# tc08ss.net
KiCad netlist of a schematic drawn in EAGLE
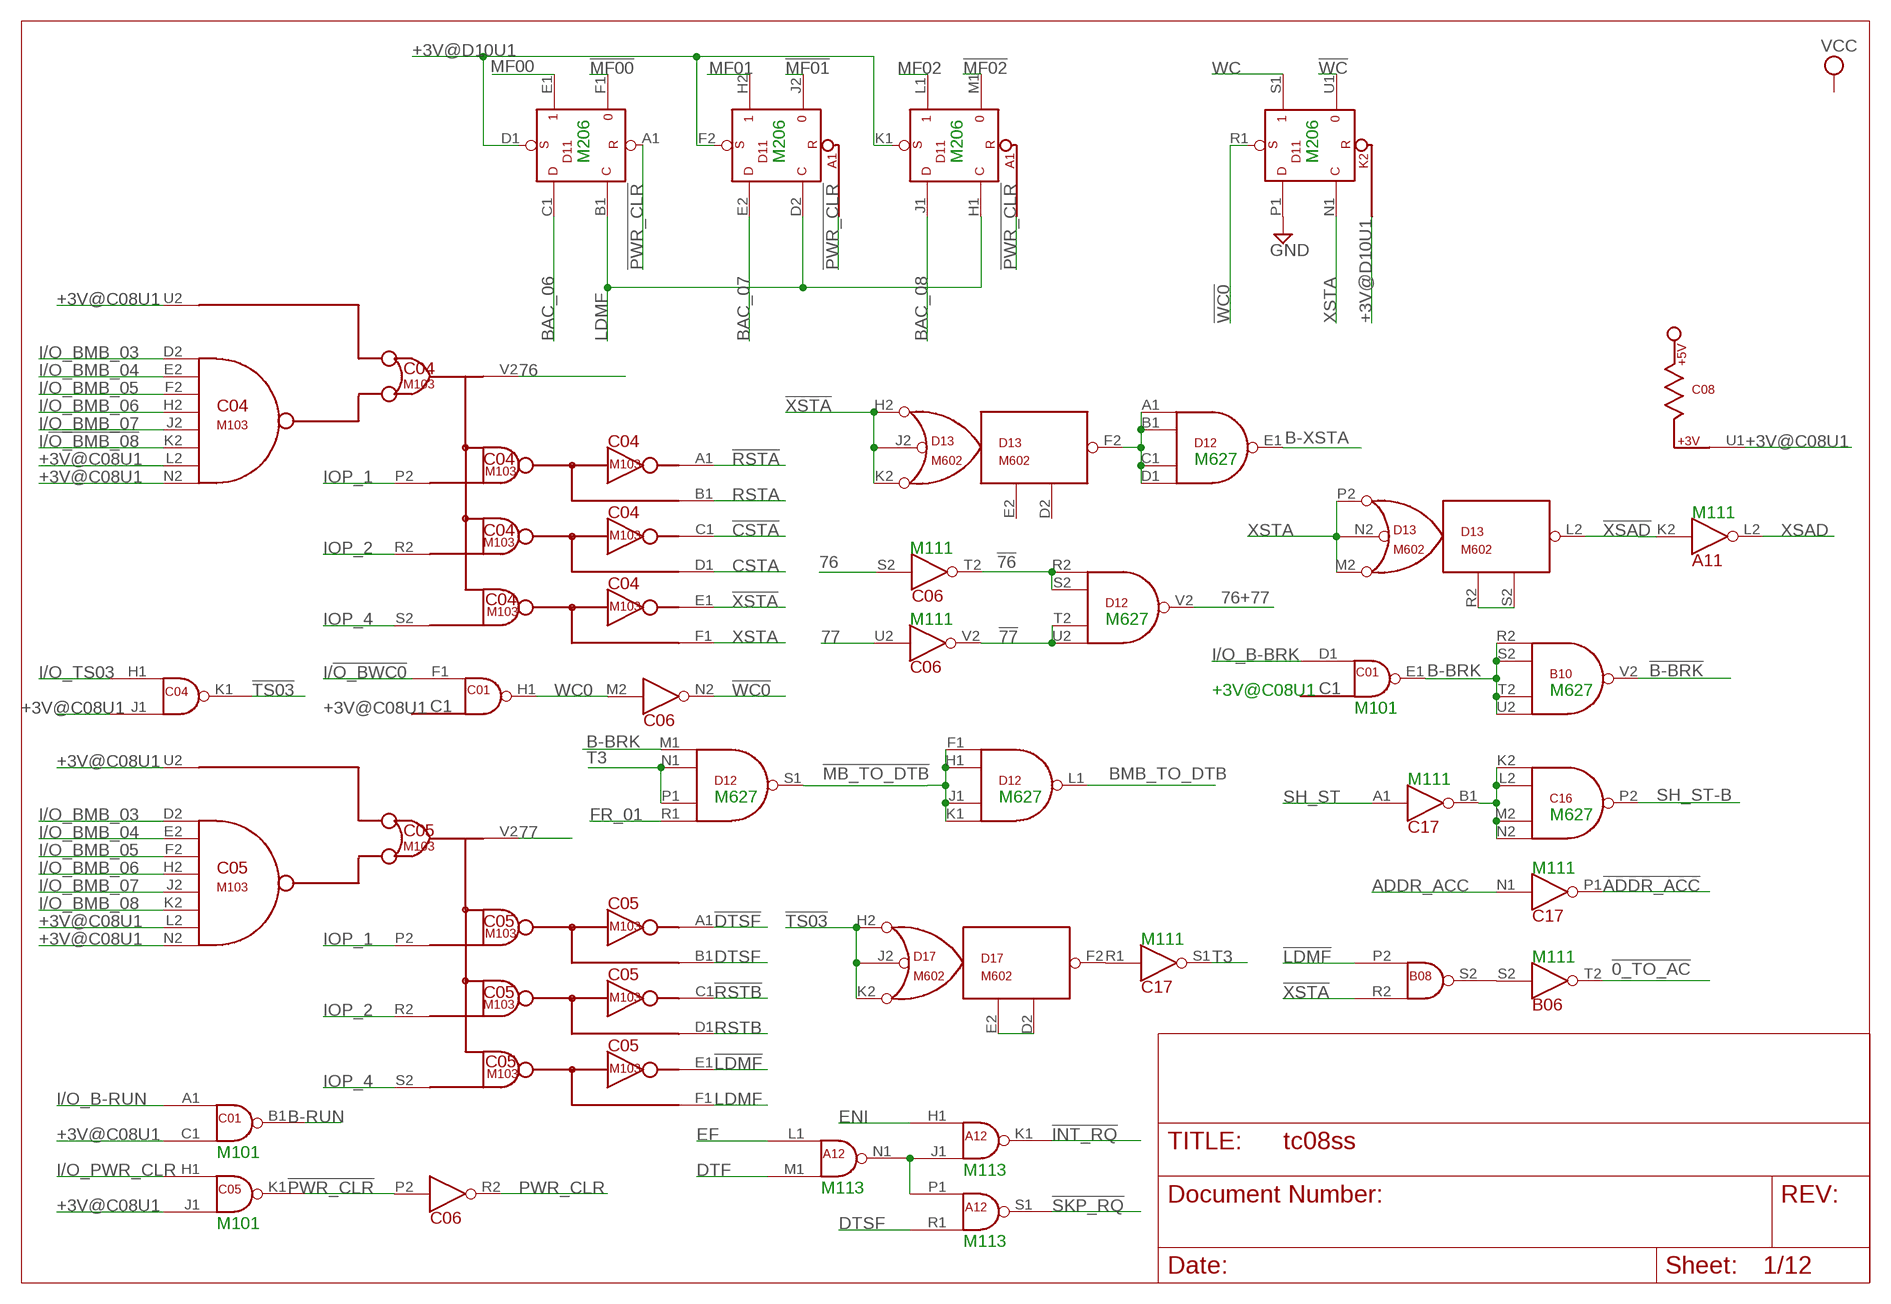
[diagram p0: schematic, sheet 1]
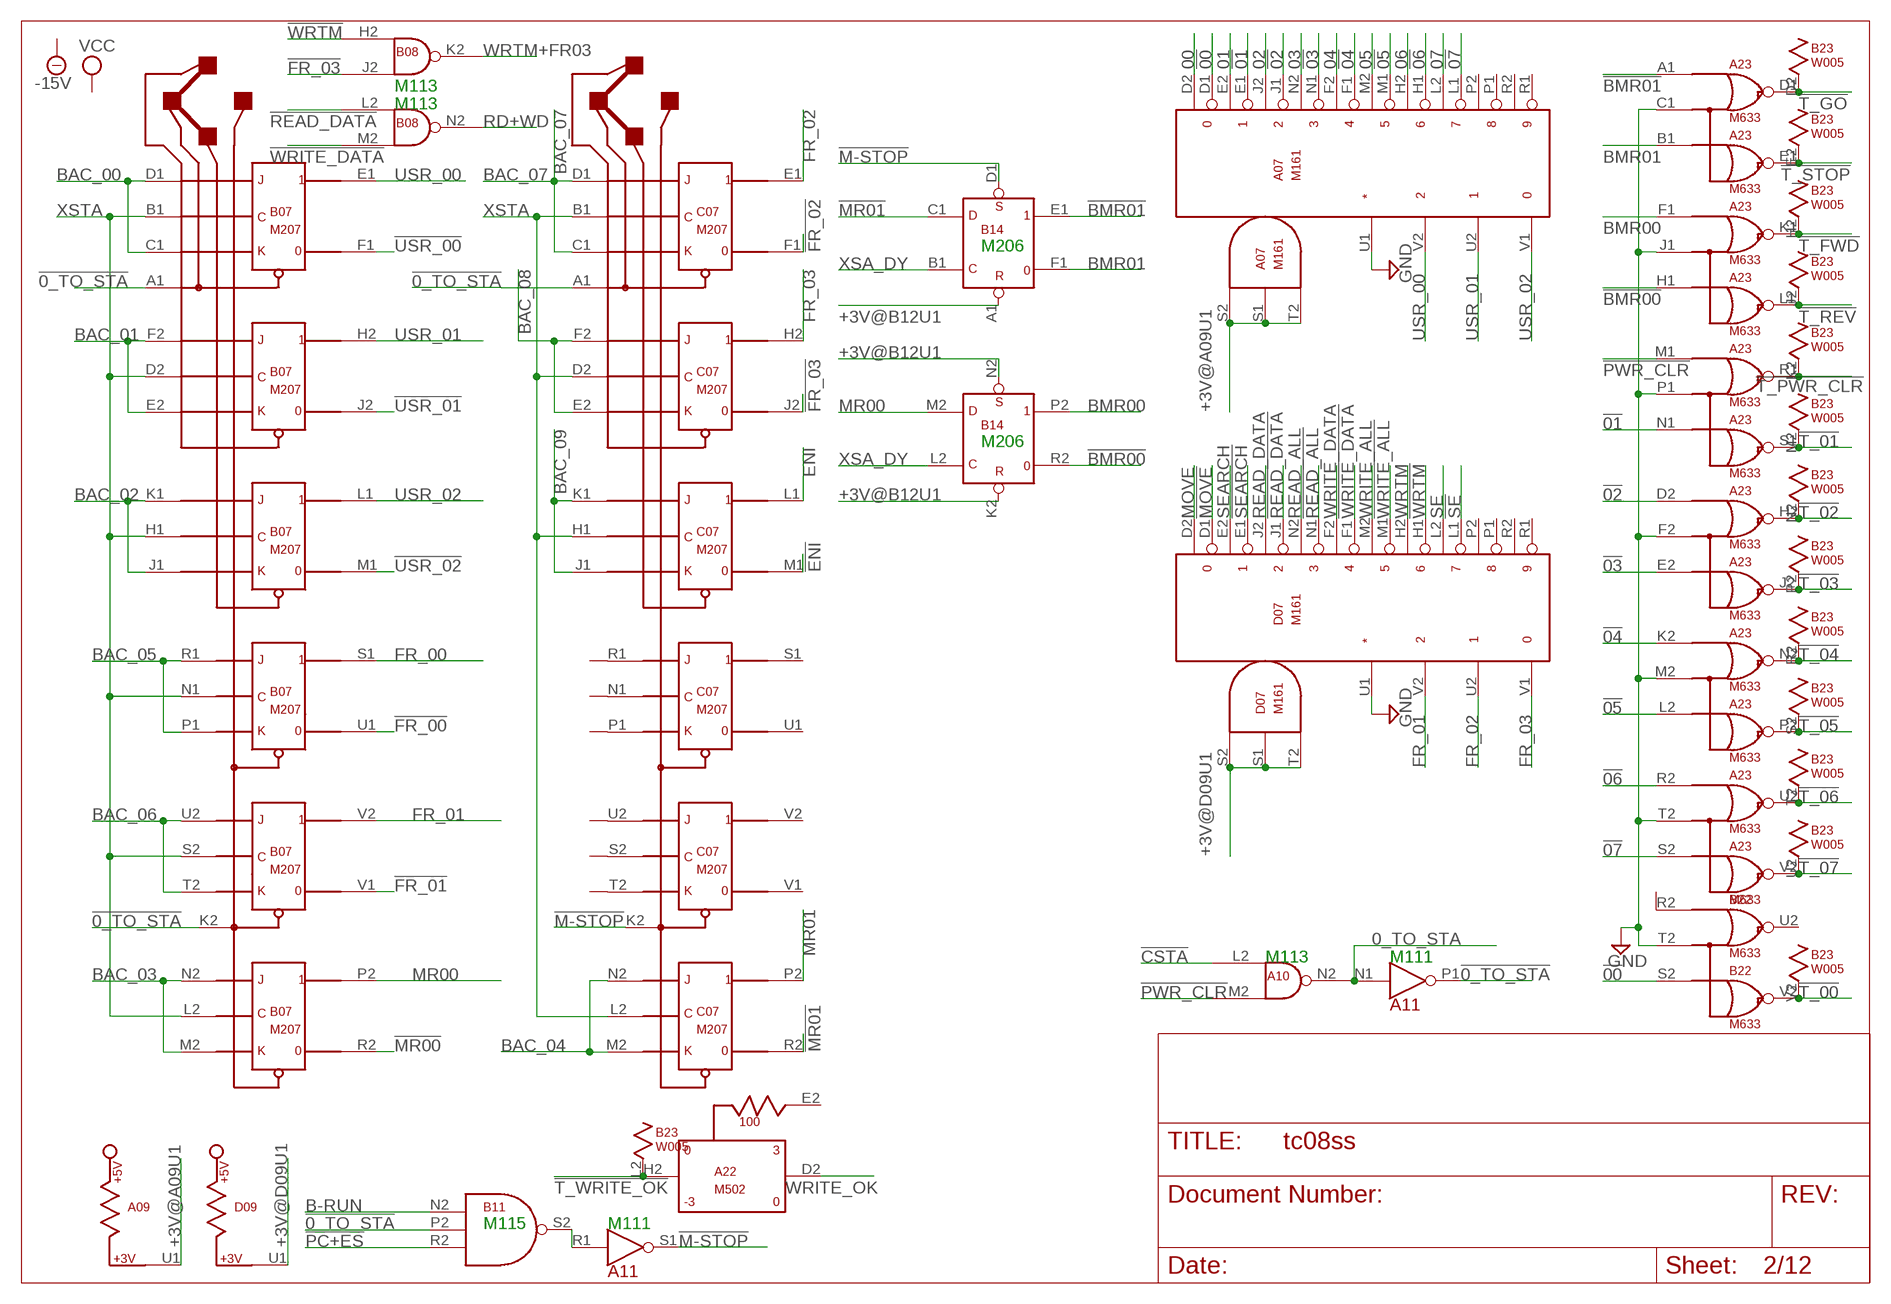
[diagram p1: schematic, sheet 2]
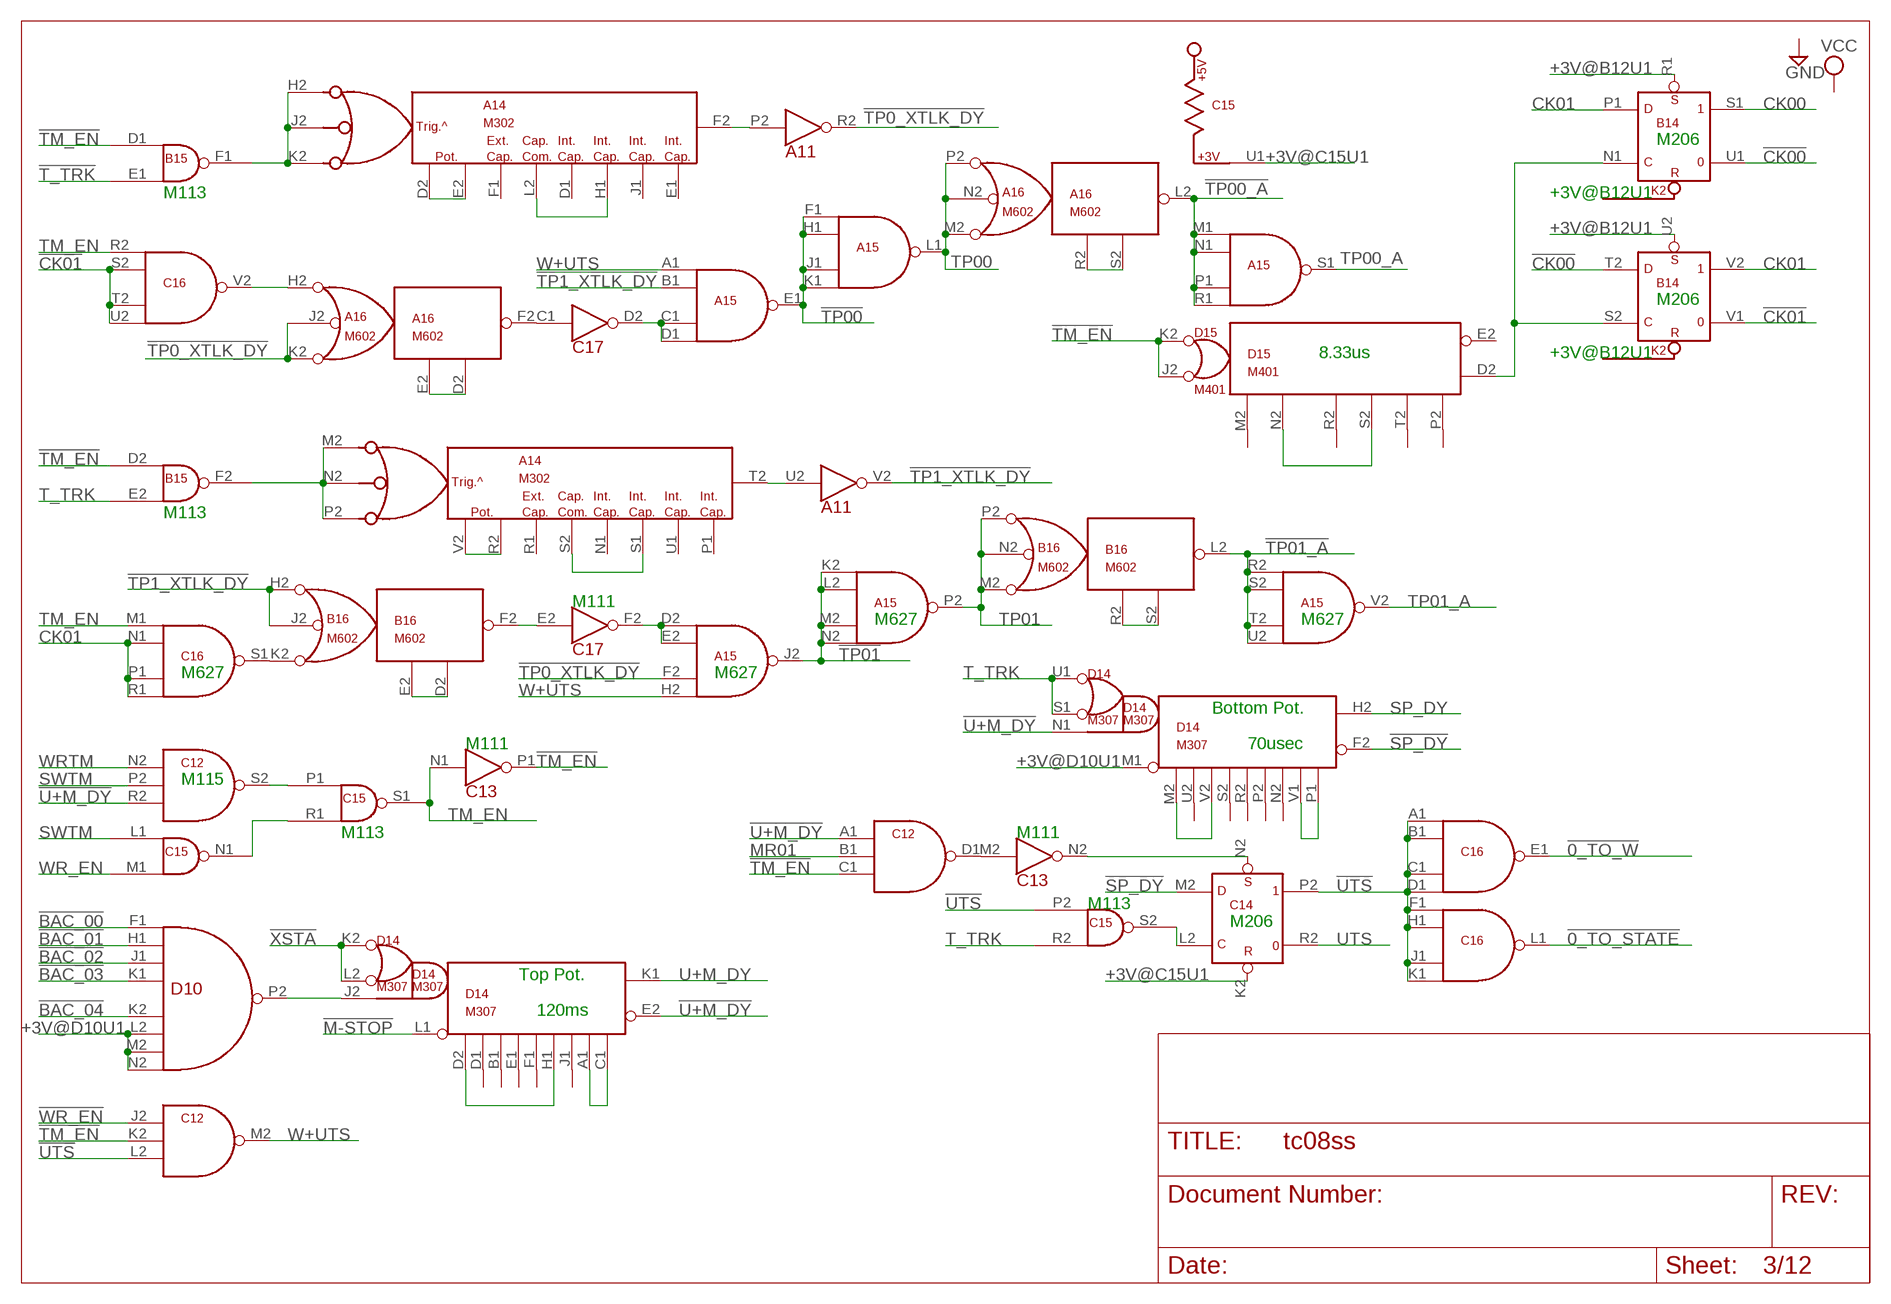
[diagram p2: schematic, sheet 3]
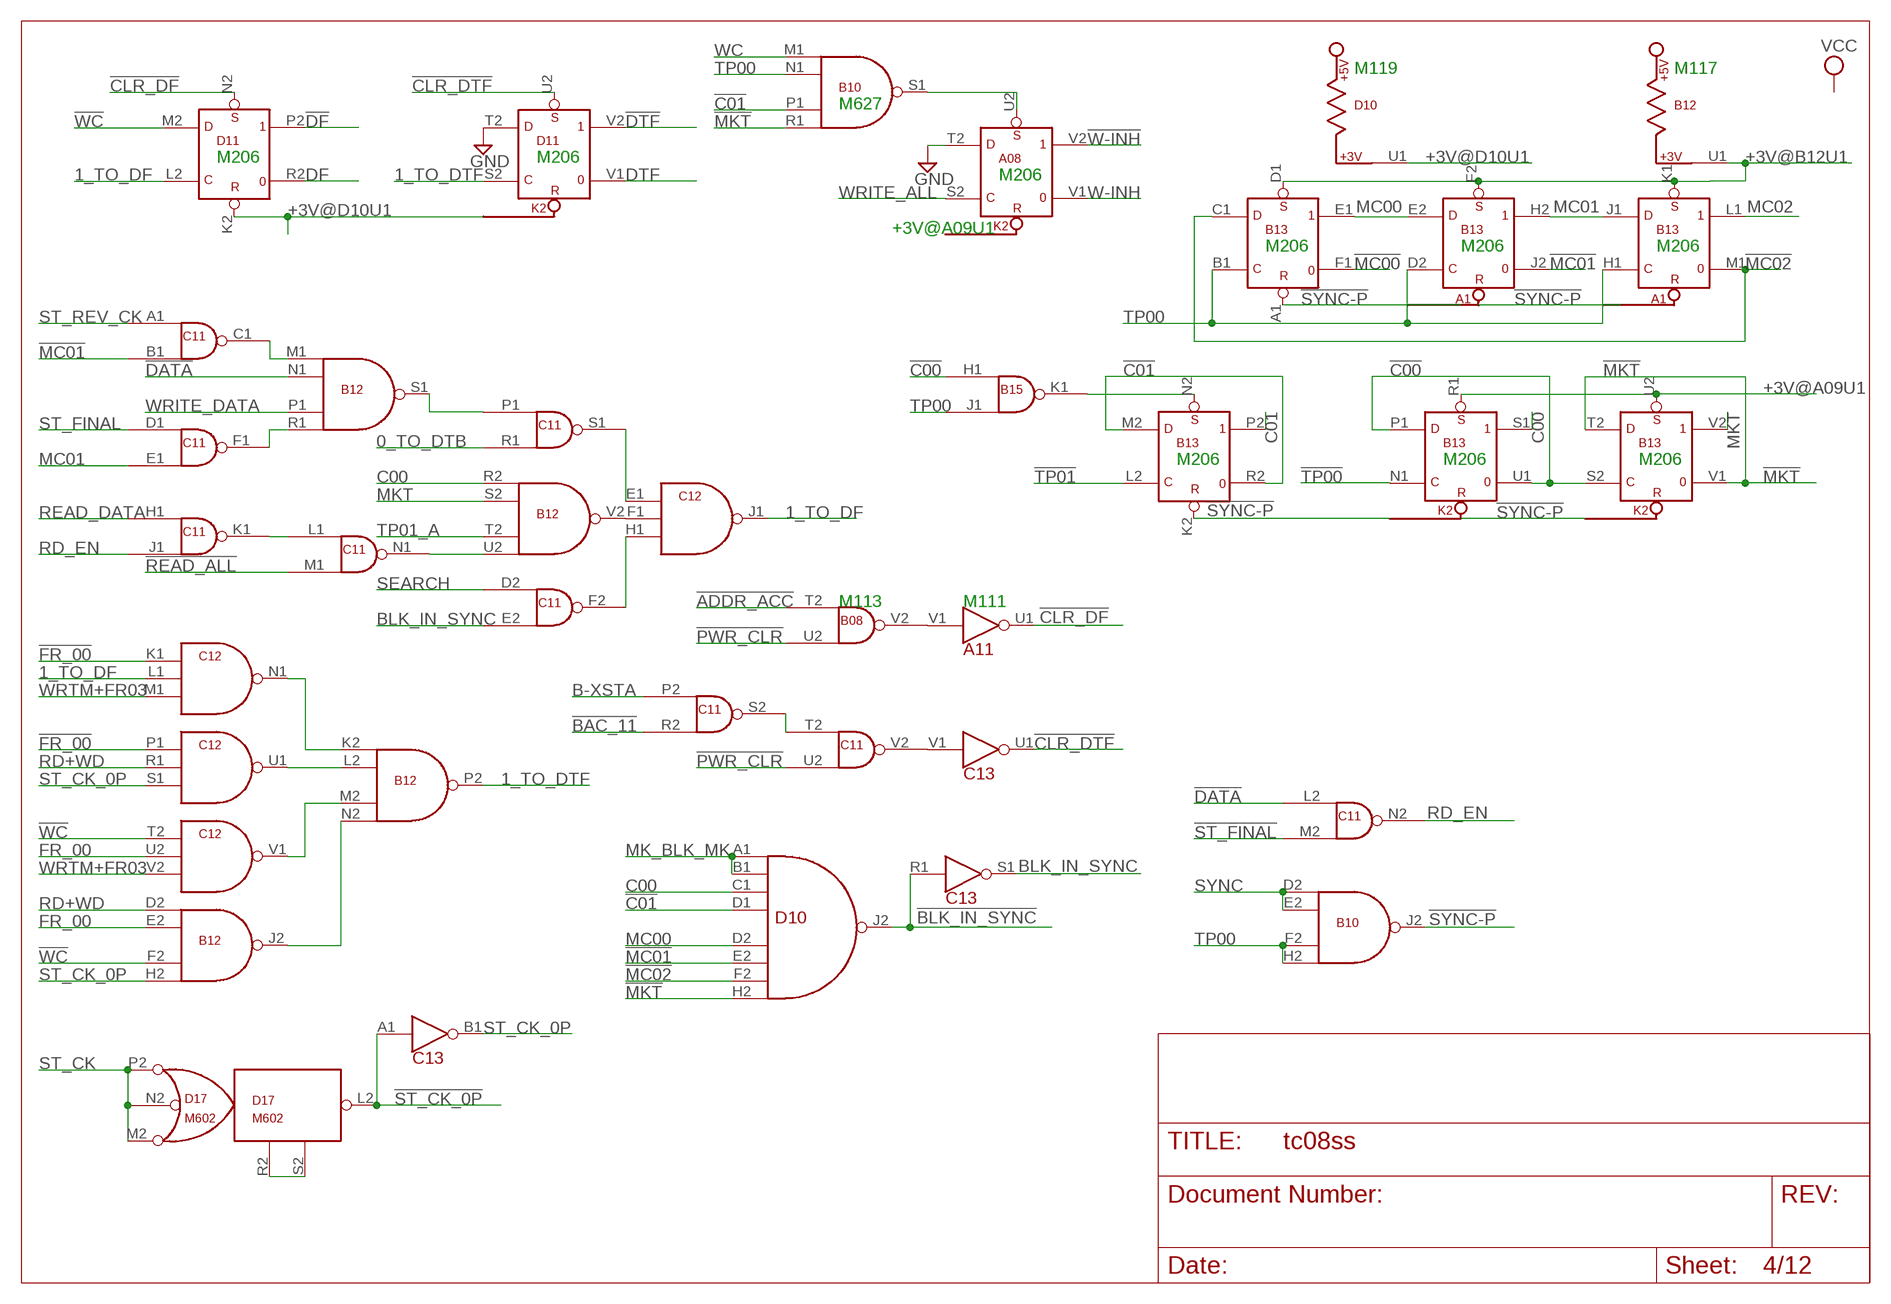
[diagram p3: schematic, sheet 4]
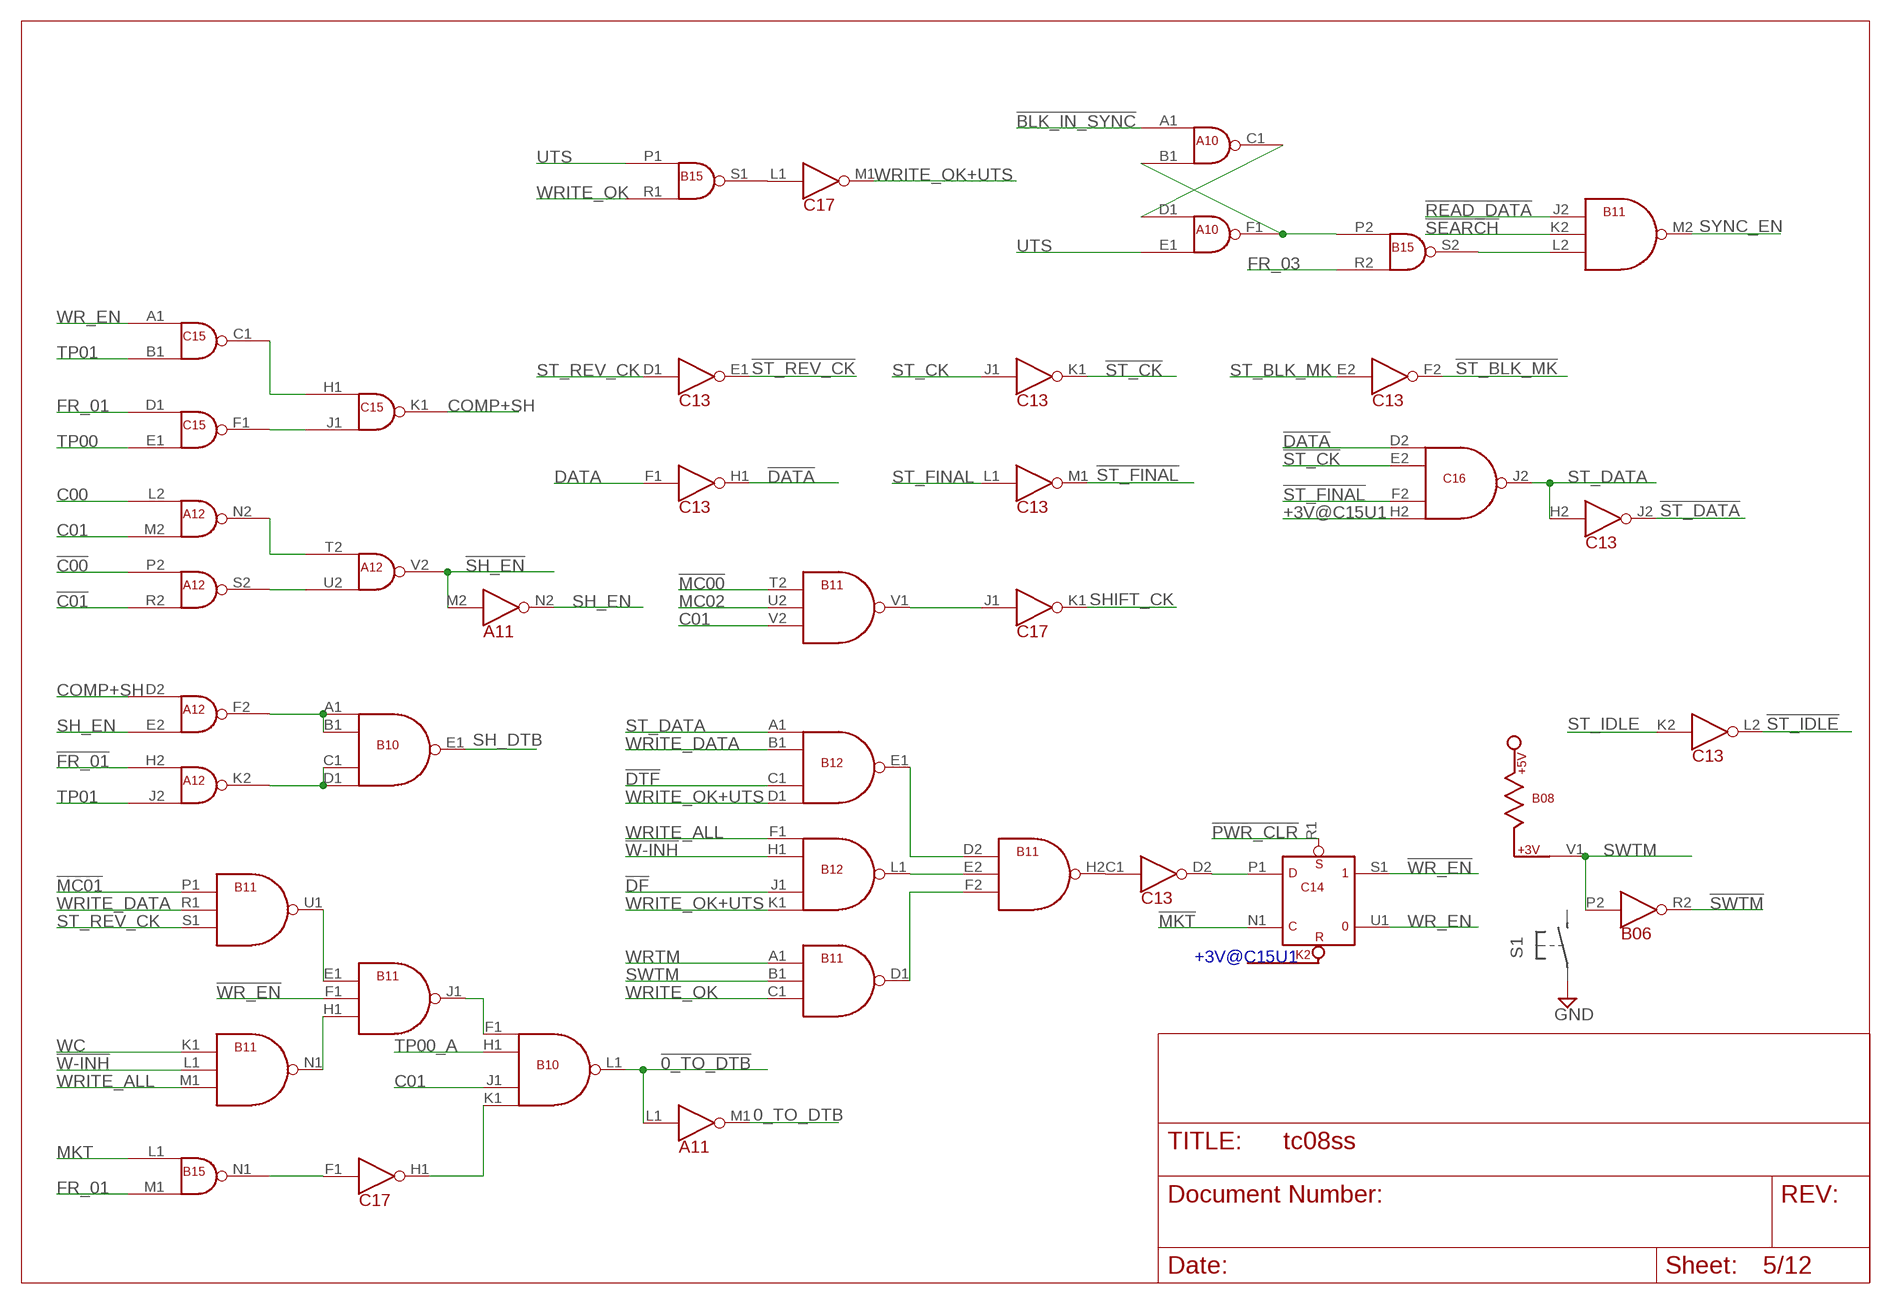
[diagram p4: schematic, sheet 5]
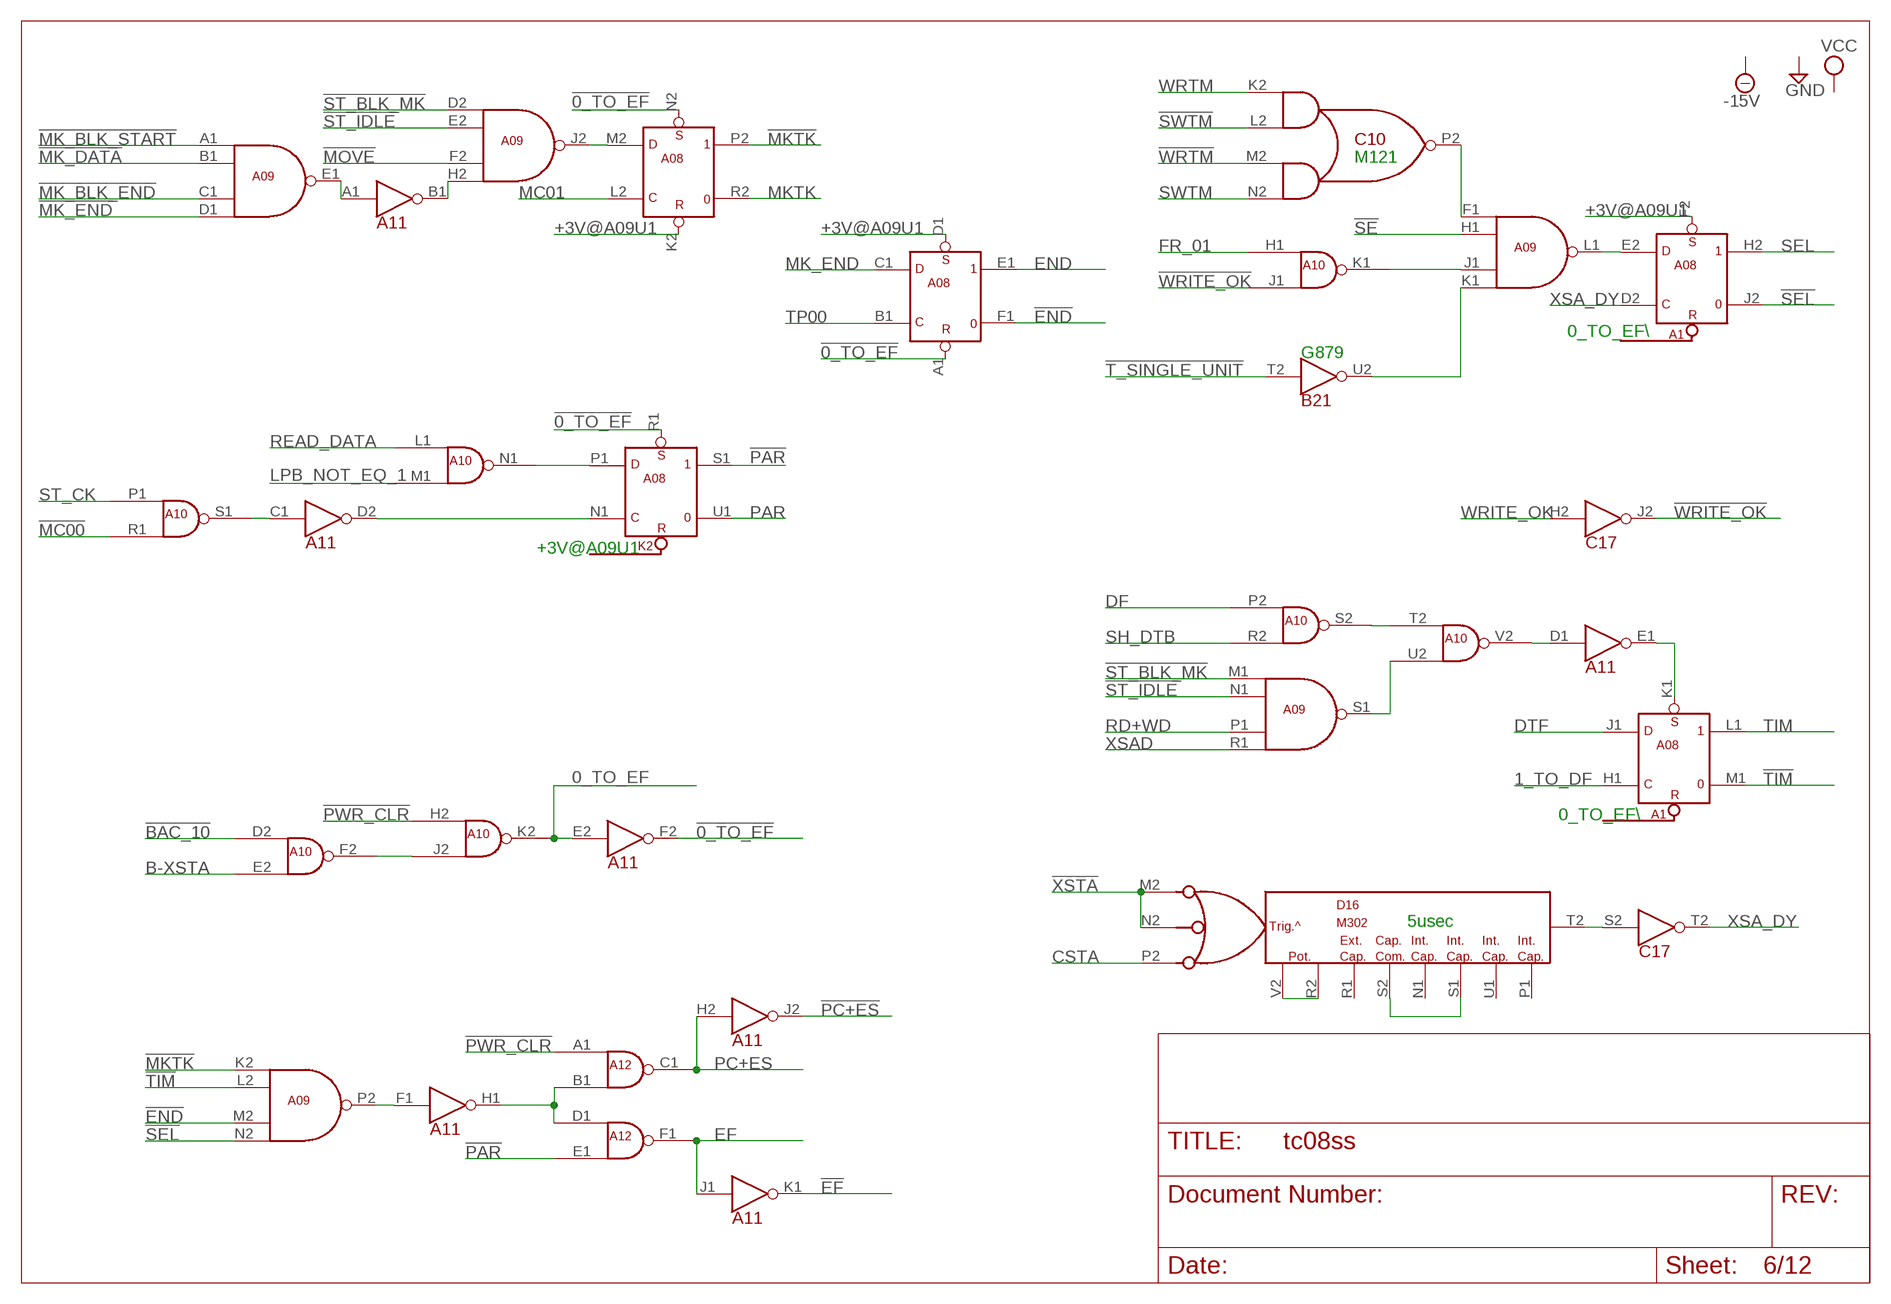
[diagram p5: schematic, sheet 6]
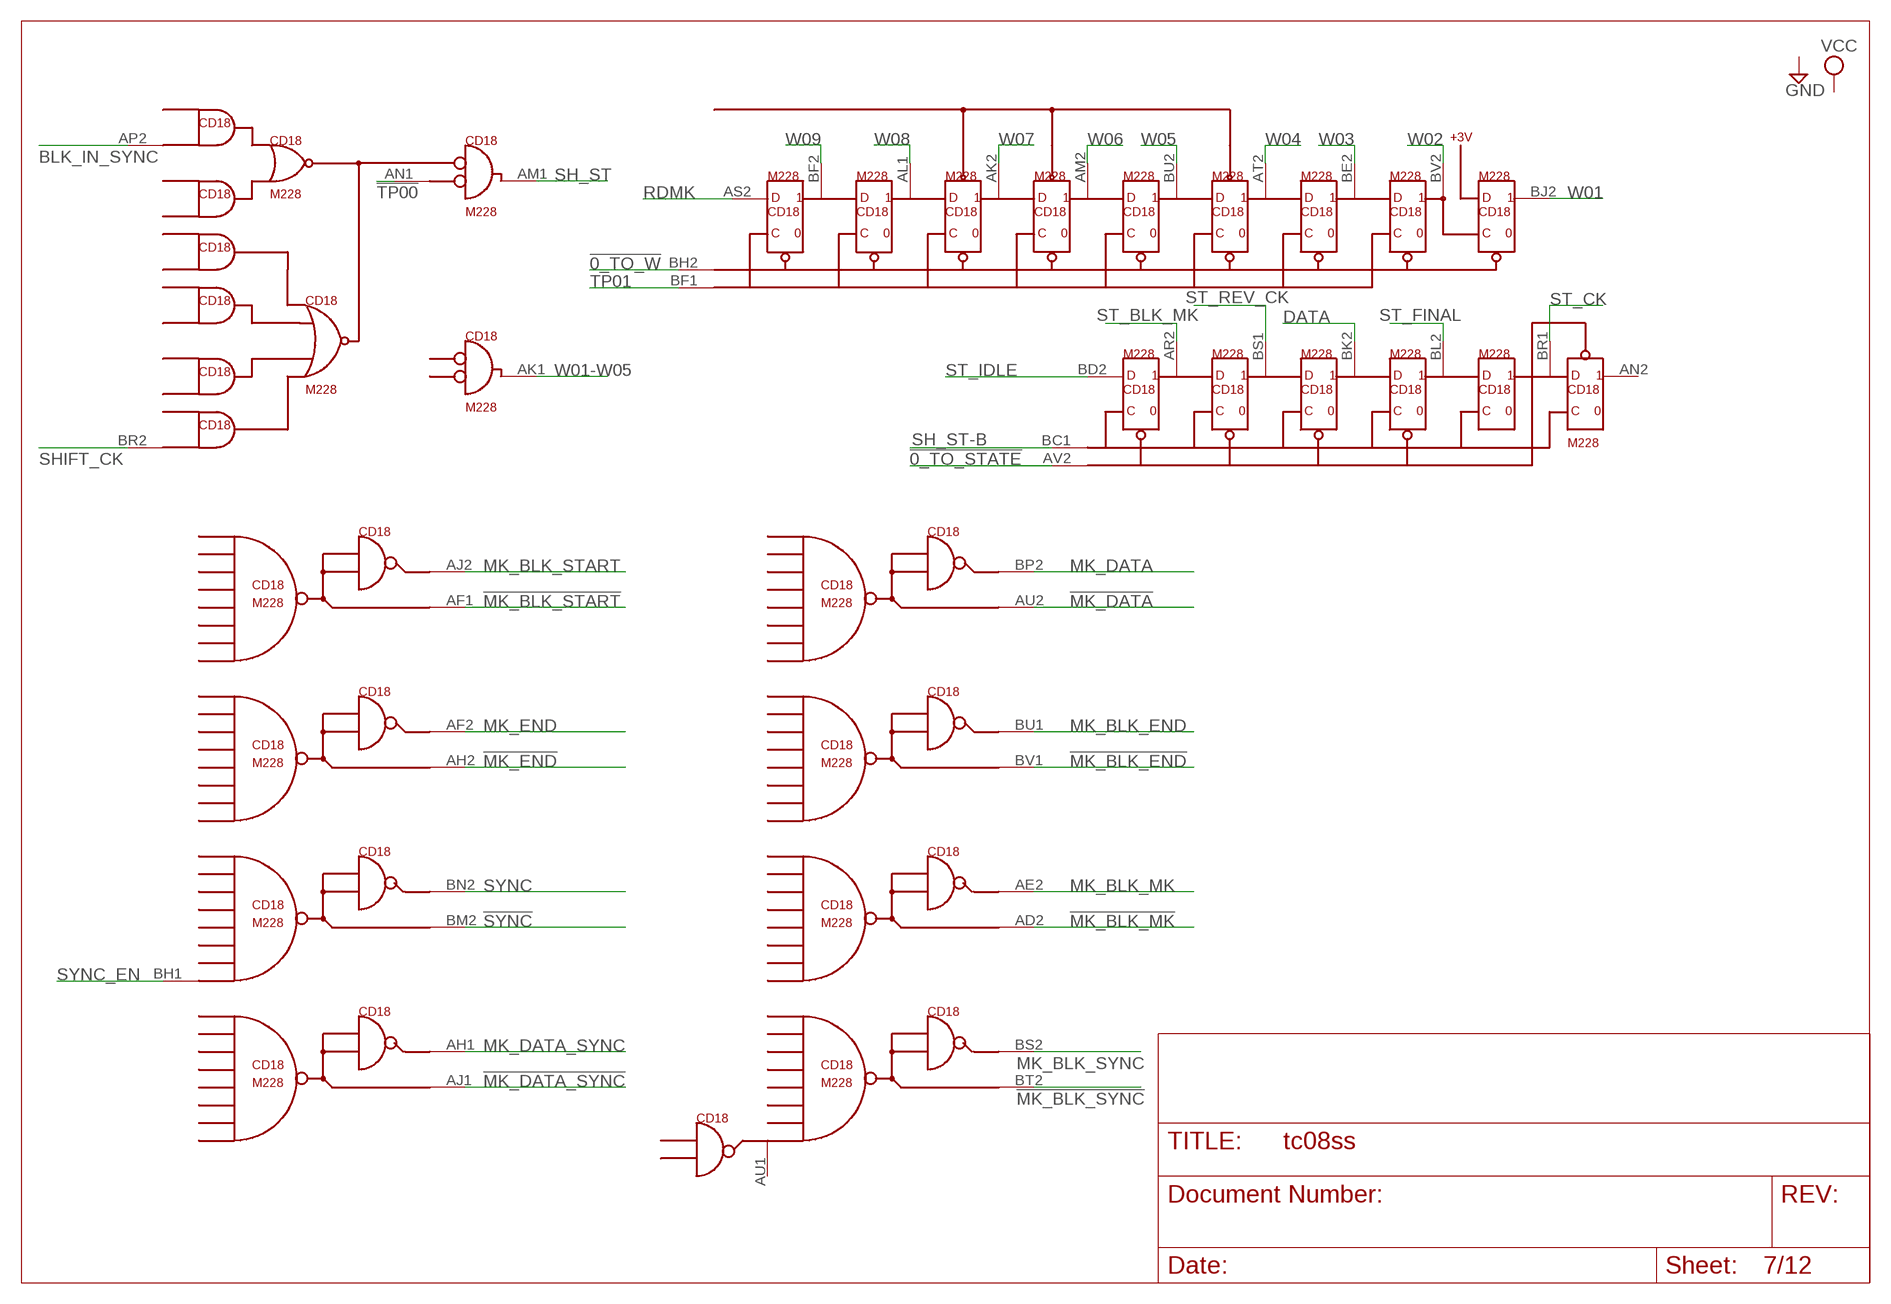
[diagram p6: schematic, sheet 7]
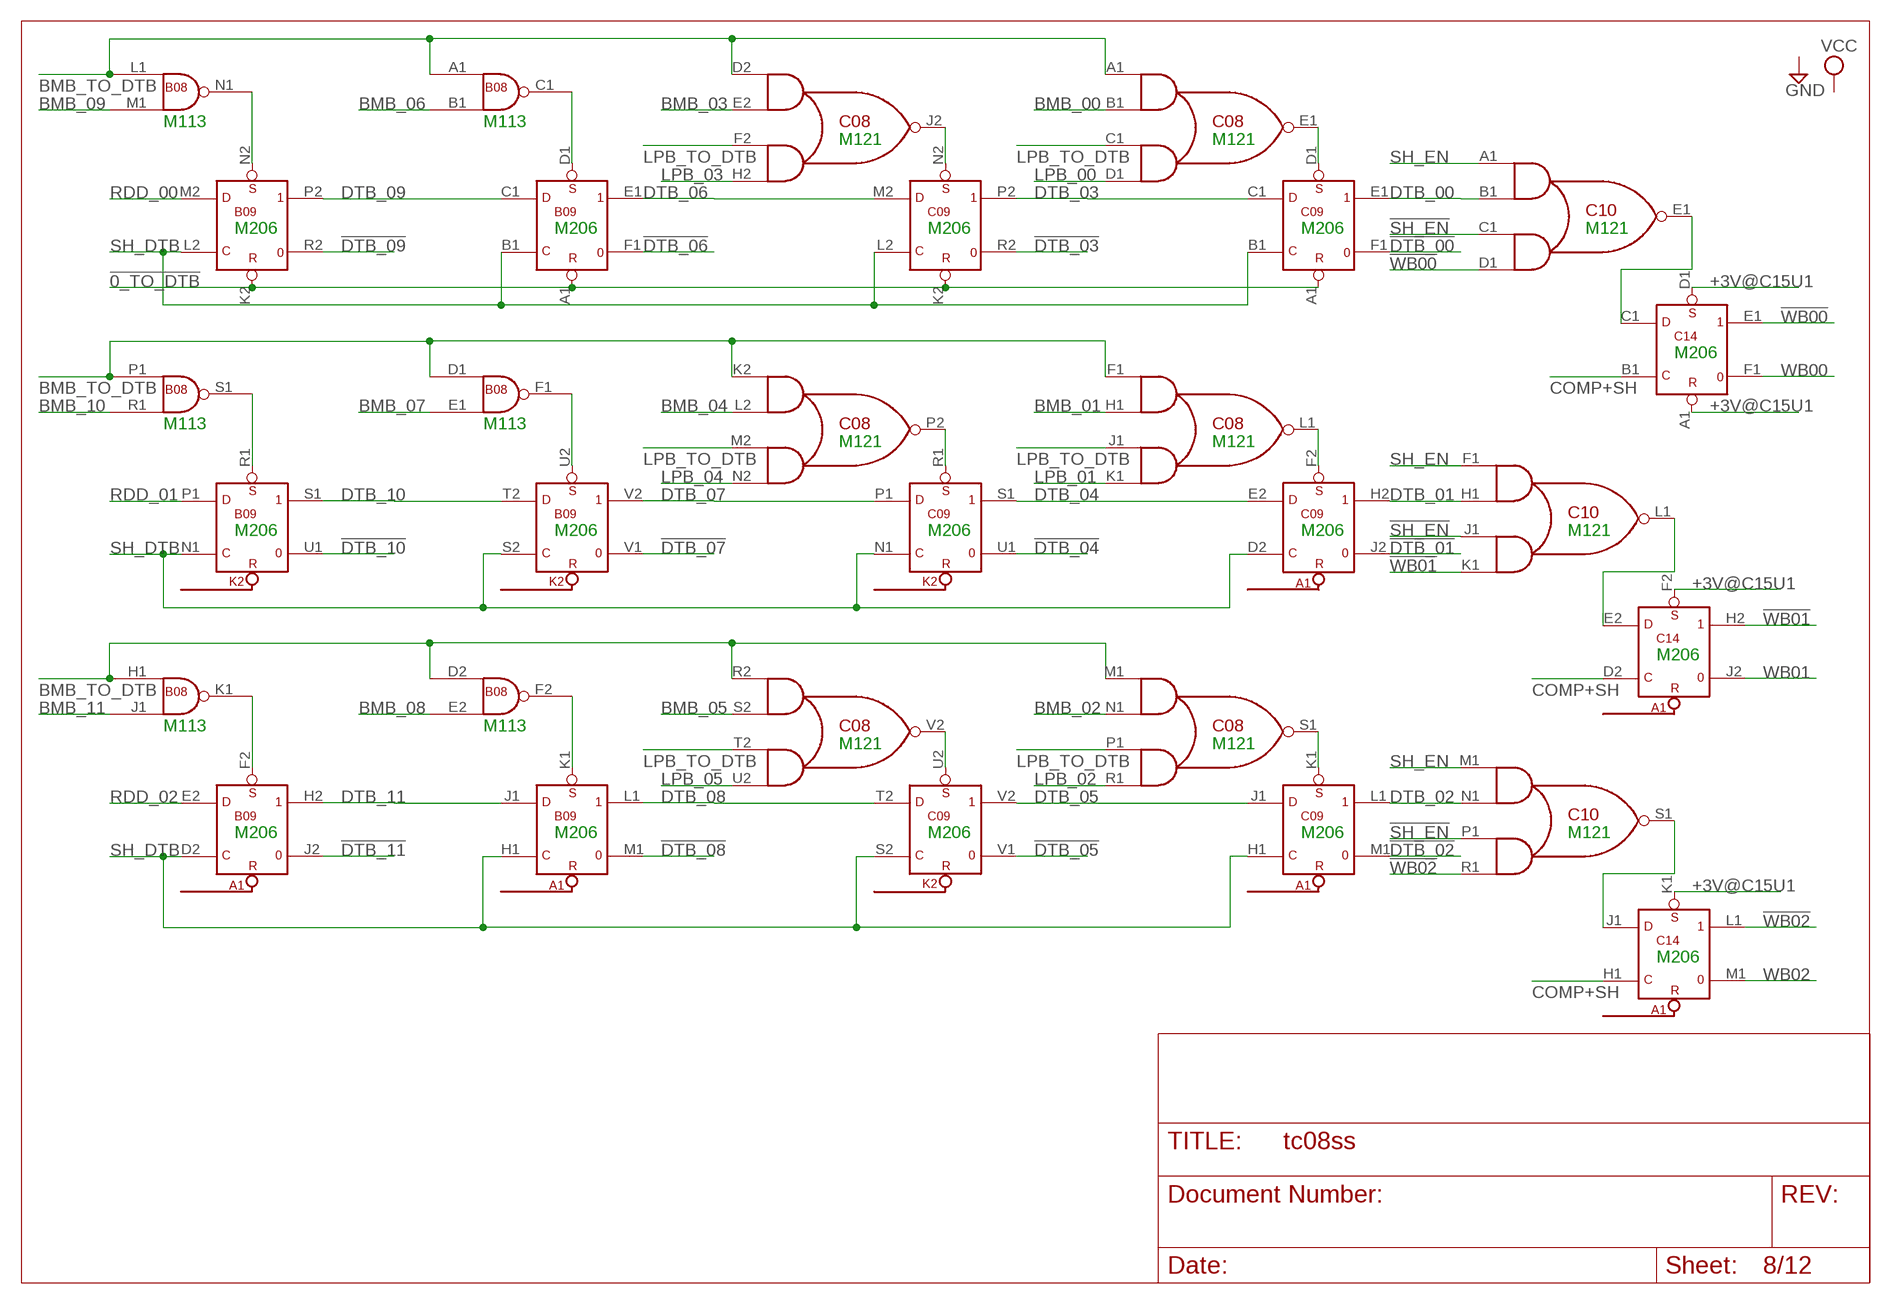
[diagram p7: schematic, sheet 8]
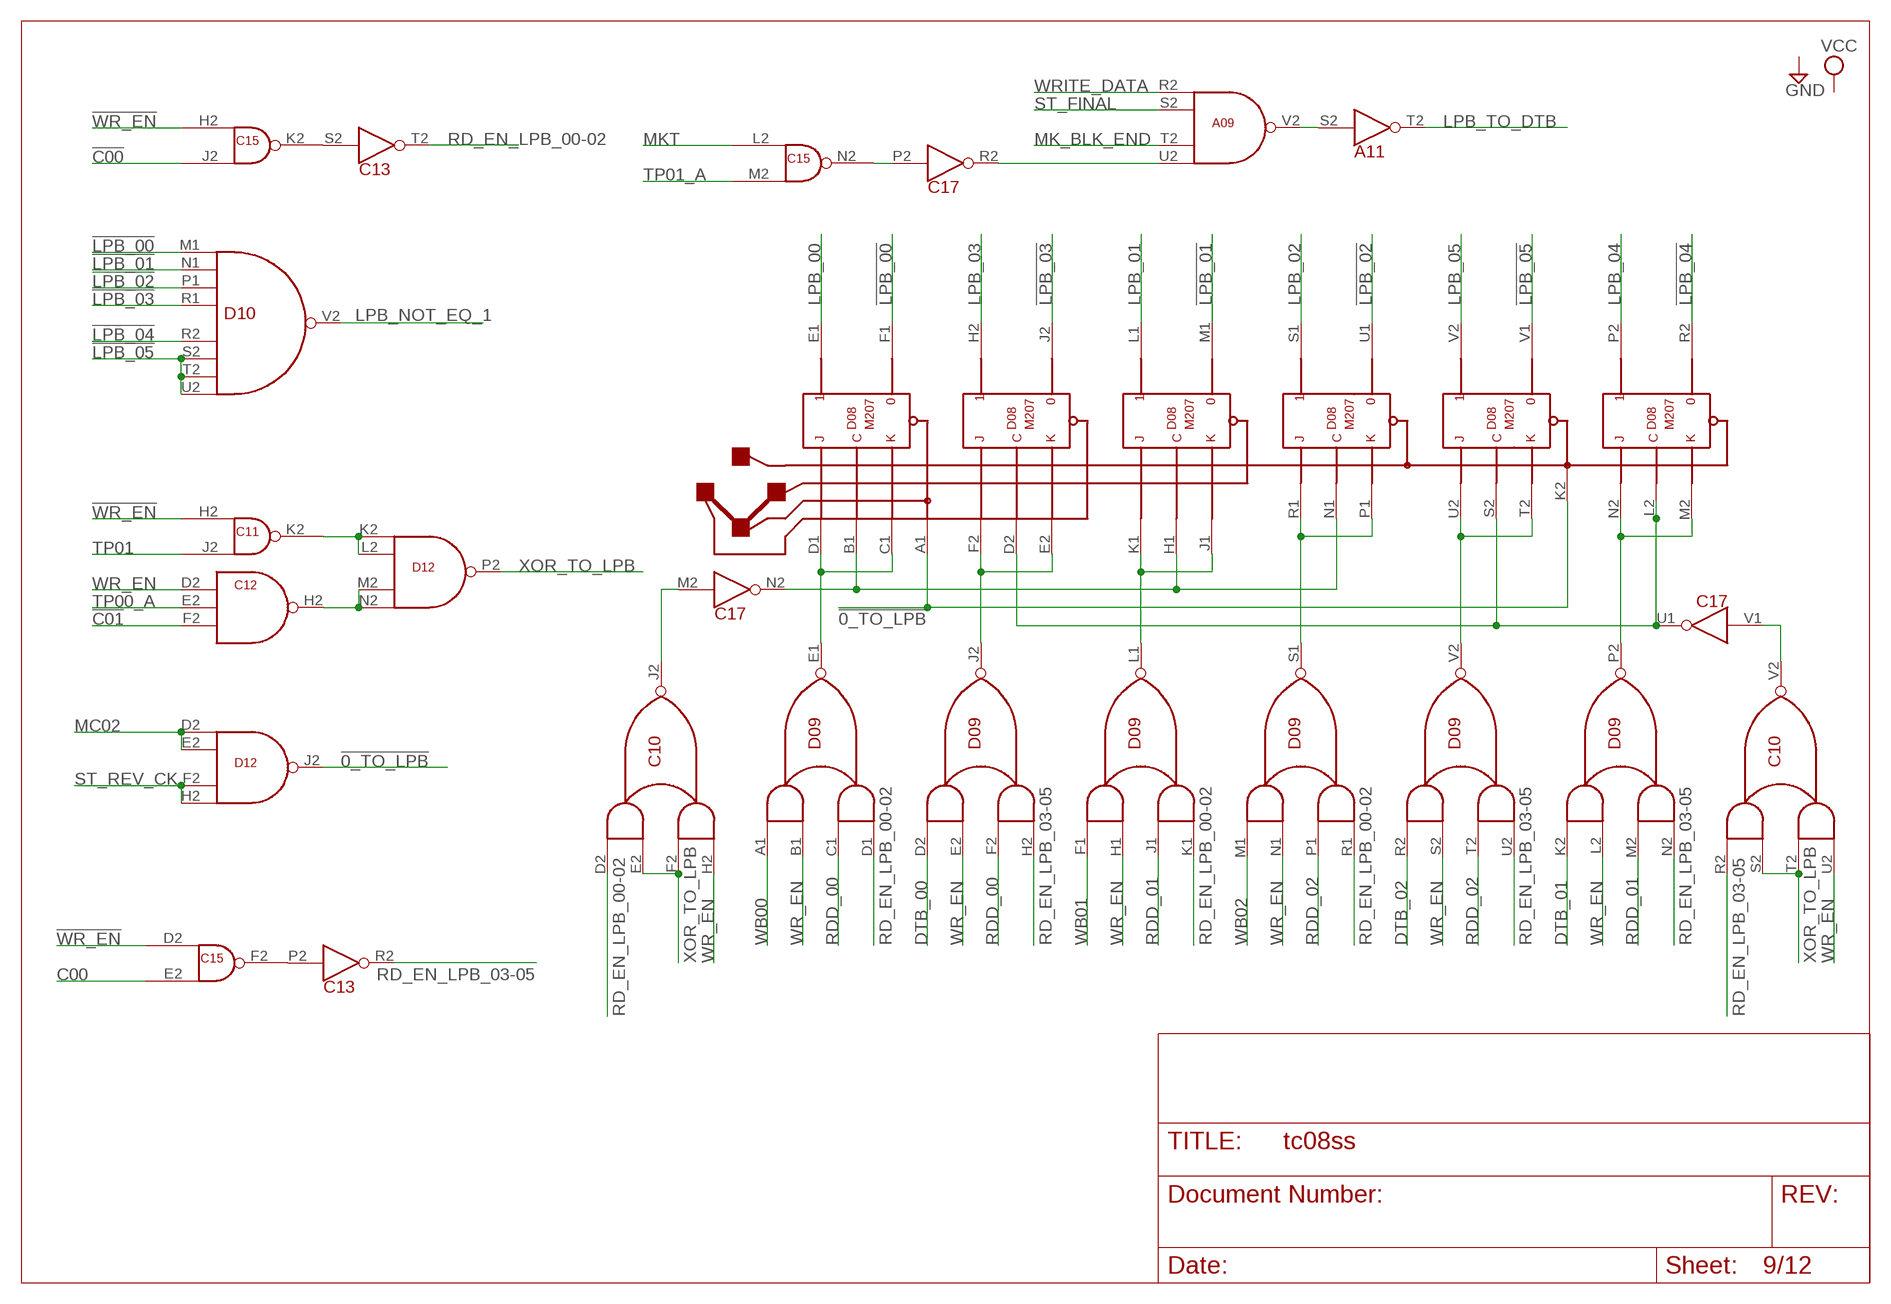
[diagram p8: schematic, sheet 9]
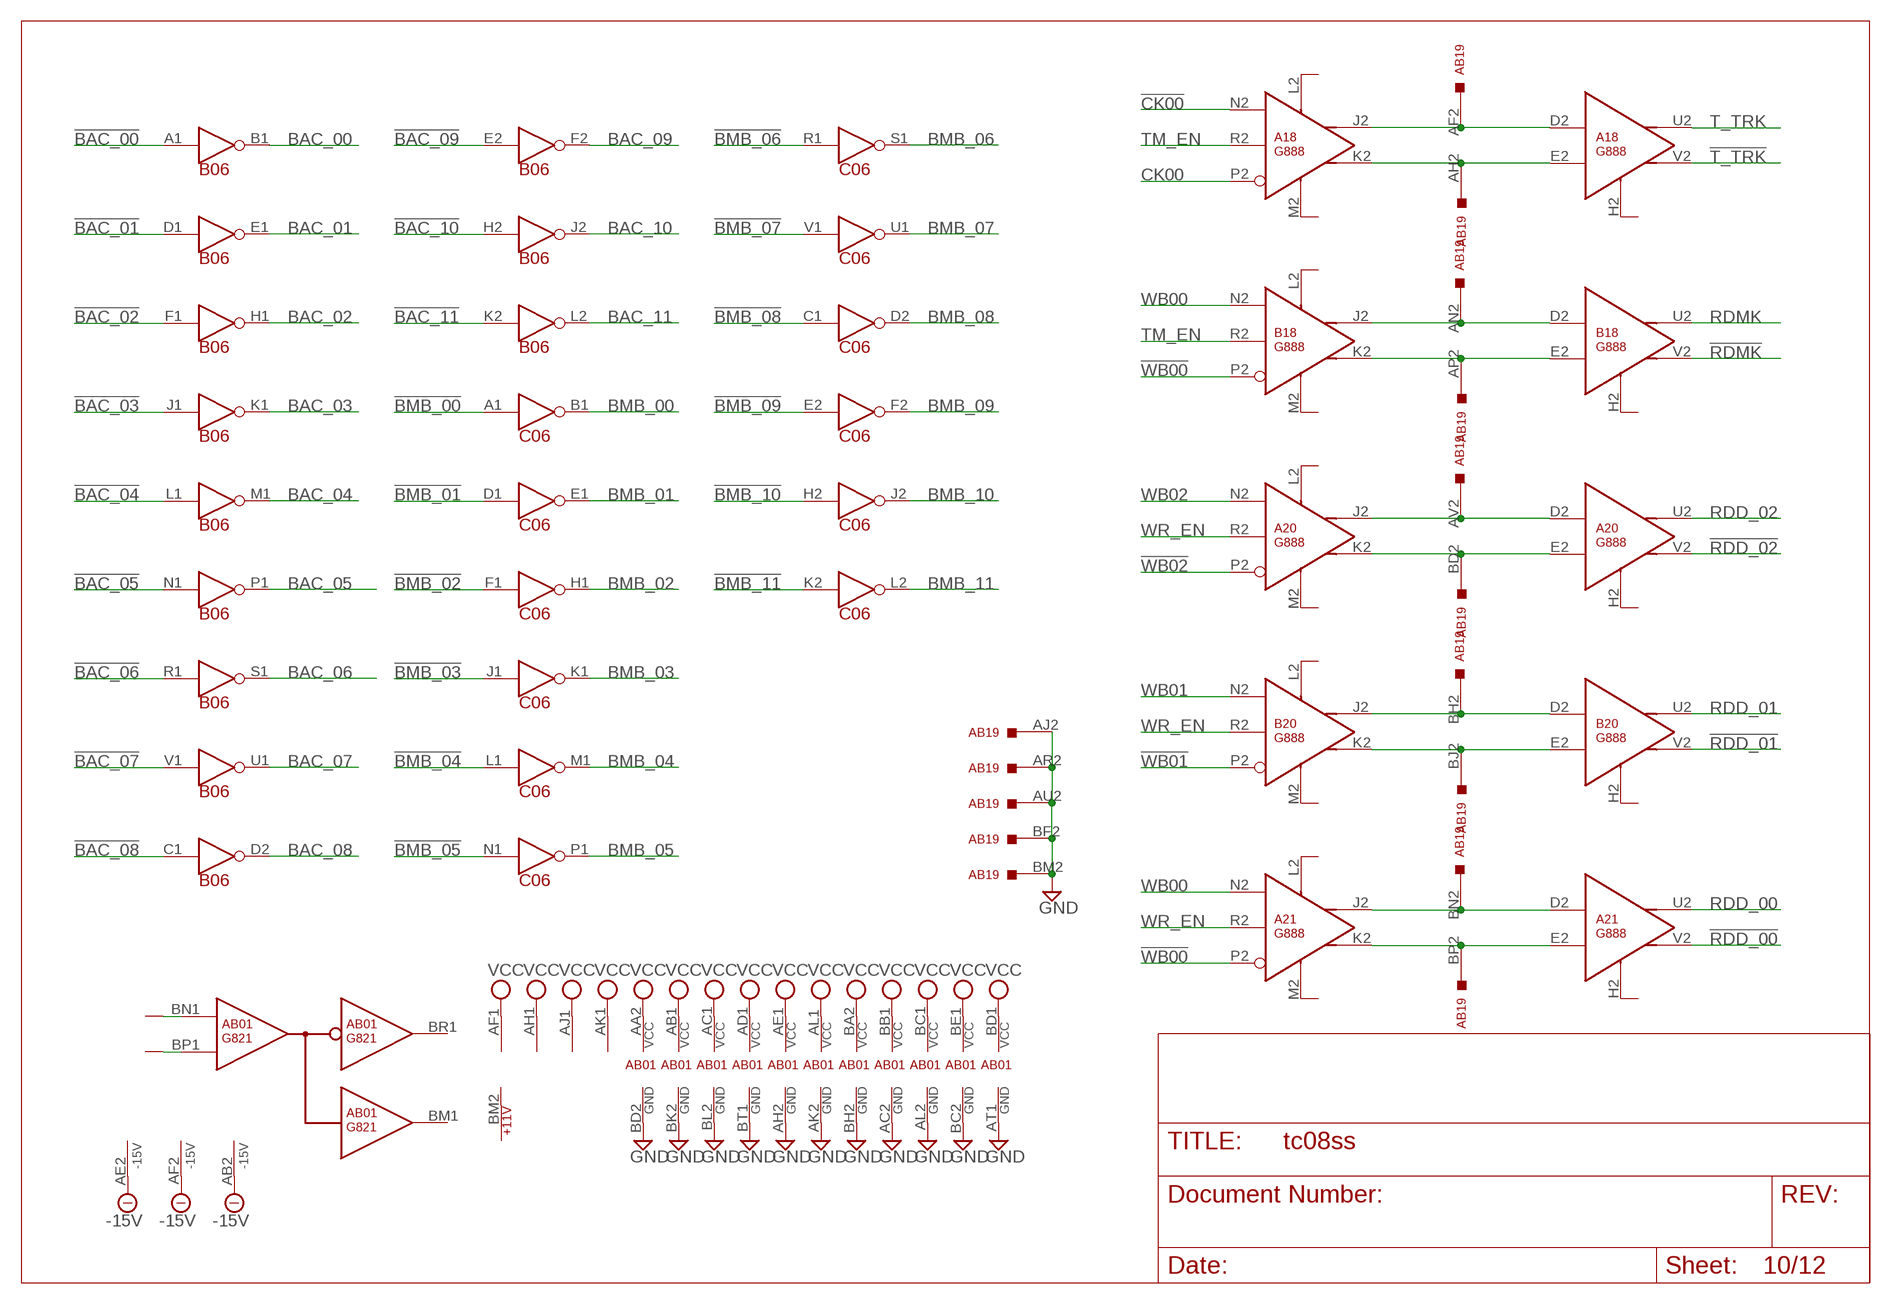
[diagram p9: schematic, sheet 10]
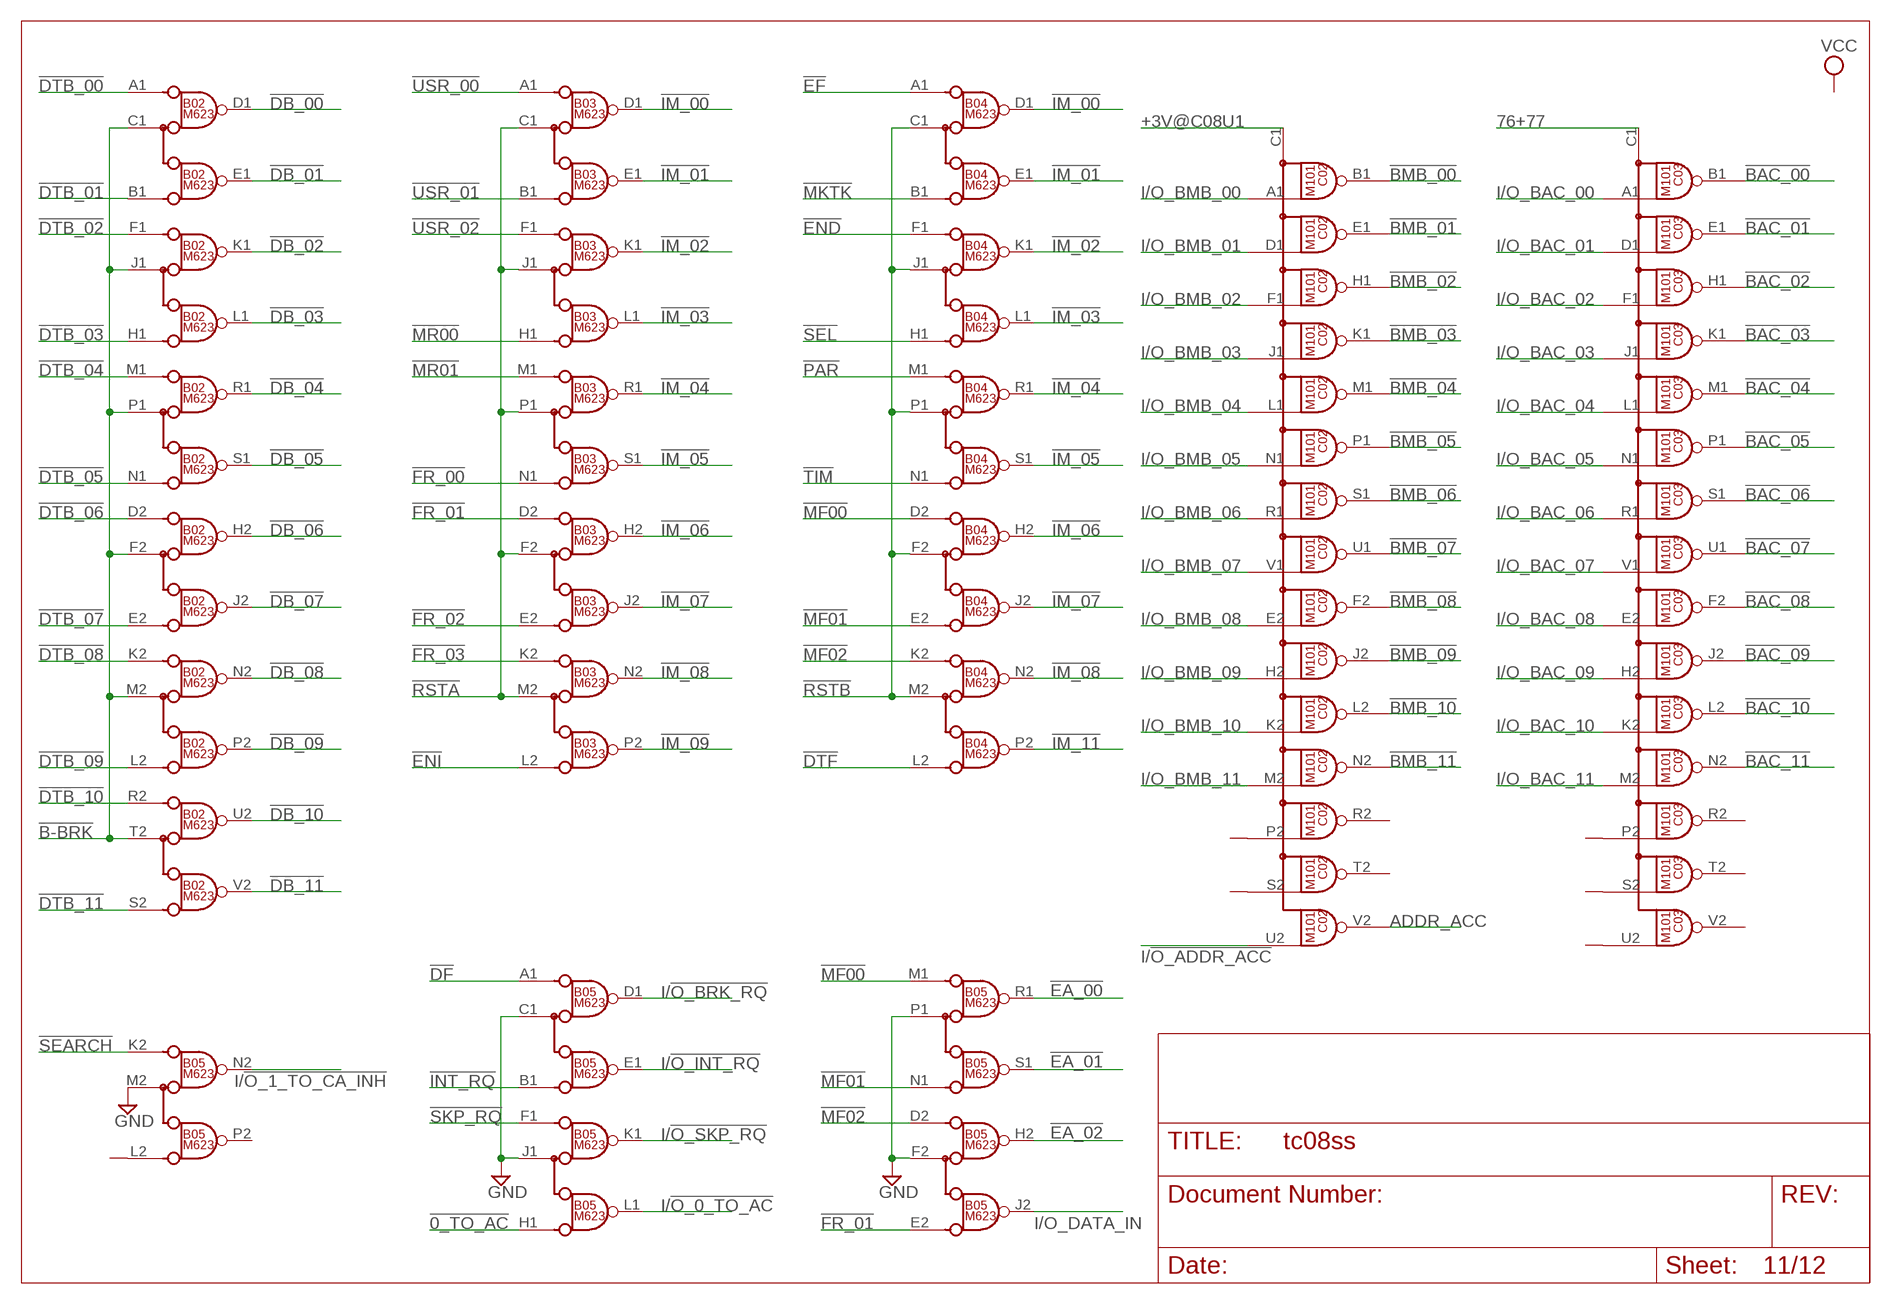
[diagram p10: schematic, sheet 11]
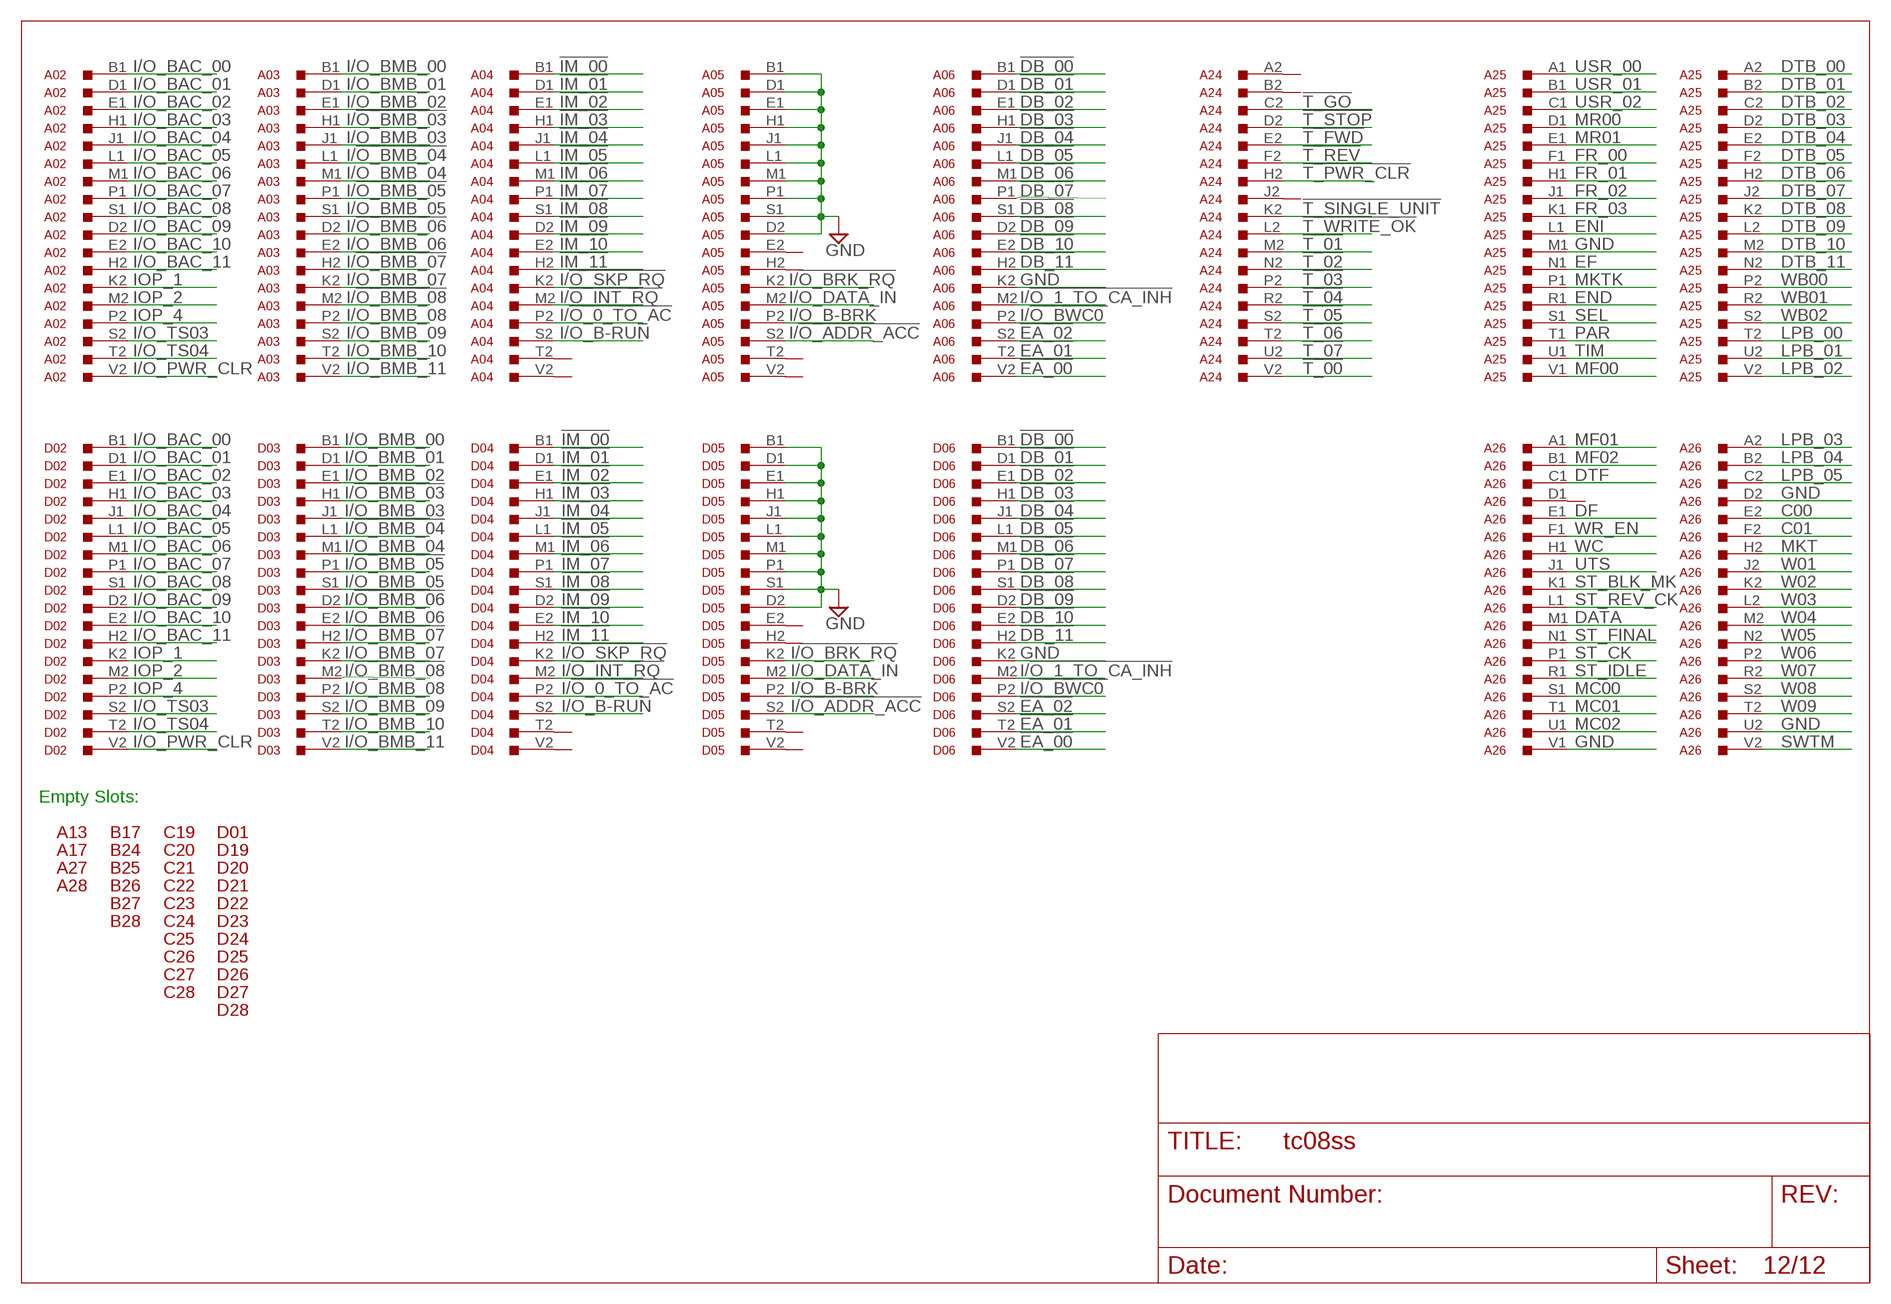
[diagram p11: schematic, sheet 12]

(export (version "E")
  (design (tool "Eeschema 10.0.6"))
  (components
    (comp (ref "B08")
      (value "B08")
      (footprint "eagle-import:H807")
      (libsource (lib "eagle-import") (part "M113"))
    )
    (comp (ref "B09")
      (value "M206X")
      (footprint "eagle-import:H807")
      (libsource (lib "eagle-import") (part "M206X"))
    )
    (comp (ref "C08")
      (value "C08")
      (footprint "eagle-import:H807")
      (libsource (lib "eagle-import") (part "M121"))
    )
    (comp (ref "C09")
      (value "M206X")
      (footprint "eagle-import:H807")
      (libsource (lib "eagle-import") (part "M206X"))
    )
    (comp (ref "C10")
      (value "M121")
      (footprint "eagle-import:H807")
      (libsource (lib "eagle-import") (part "M121"))
    )
    (comp (ref "C14")
      (value "M206X")
      (footprint "eagle-import:H807")
      (libsource (lib "eagle-import") (part "M206X"))
    )
    (comp (ref "A07")
      (value "A07")
      (footprint "eagle-import:H807")
      (libsource (lib "eagle-import") (part "M161"))
    )
    (comp (ref "A09")
      (value "M117")
      (footprint "eagle-import:H807")
      (libsource (lib "eagle-import") (part "M117"))
    )
    (comp (ref "A10")
      (value "M113")
      (footprint "eagle-import:H807")
      (libsource (lib "eagle-import") (part "M113"))
    )
    (comp (ref "A11")
      (value "A11")
      (footprint "eagle-import:H807")
      (libsource (lib "eagle-import") (part "M111"))
    )
    (comp (ref "A22")
      (value "M502")
      (footprint "eagle-import:H807")
      (libsource (lib "eagle-import") (part "M502"))
    )
    (comp (ref "A23")
      (value "M633")
      (footprint "eagle-import:H807")
      (libsource (lib "eagle-import") (part "M633"))
    )
    (comp (ref "B07")
      (value "B07")
      (footprint "eagle-import:H807")
      (libsource (lib "eagle-import") (part "M207"))
    )
    (comp (ref "B11")
      (value "M115")
      (footprint "eagle-import:H807")
      (libsource (lib "eagle-import") (part "M115"))
    )
    (comp (ref "B14")
      (value "M206X")
      (footprint "eagle-import:H807")
      (libsource (lib "eagle-import") (part "M206X"))
    )
    (comp (ref "B22")
      (value "M633")
      (footprint "eagle-import:H807")
      (libsource (lib "eagle-import") (part "M633"))
    )
    (comp (ref "B23")
      (value "W005")
      (footprint "eagle-import:H807")
      (libsource (lib "eagle-import") (part "W005"))
    )
    (comp (ref "C07")
      (value "B07")
      (footprint "eagle-import:H807")
      (libsource (lib "eagle-import") (part "M207"))
    )
    (comp (ref "D07")
      (value "D07")
      (footprint "eagle-import:H807")
      (libsource (lib "eagle-import") (part "M161"))
    )
    (comp (ref "D09")
      (value "M121")
      (footprint "eagle-import:H807")
      (libsource (lib "eagle-import") (part "M121"))
    )
    (comp (ref "A14")
      (value "M302")
      (footprint "eagle-import:H807")
      (libsource (lib "eagle-import") (part "M302"))
    )
    (comp (ref "A15")
      (value "M627")
      (footprint "eagle-import:H807")
      (libsource (lib "eagle-import") (part "M627"))
    )
    (comp (ref "A16")
      (value "M602")
      (footprint "eagle-import:H807")
      (libsource (lib "eagle-import") (part "M602"))
    )
    (comp (ref "B15")
      (value "M113")
      (footprint "eagle-import:H807")
      (libsource (lib "eagle-import") (part "M113"))
    )
    (comp (ref "B16")
      (value "M602")
      (footprint "eagle-import:H807")
      (libsource (lib "eagle-import") (part "M602"))
    )
    (comp (ref "C12")
      (value "M115")
      (footprint "eagle-import:H807")
      (libsource (lib "eagle-import") (part "M115"))
    )
    (comp (ref "C13")
      (value "M111")
      (footprint "eagle-import:H807")
      (libsource (lib "eagle-import") (part "M111"))
    )
    (comp (ref "C15")
      (value "M113")
      (footprint "eagle-import:H807")
      (libsource (lib "eagle-import") (part "M113"))
    )
    (comp (ref "C16")
      (value "C16")
      (footprint "eagle-import:H807")
      (libsource (lib "eagle-import") (part "M627"))
    )
    (comp (ref "C17")
      (value "C17")
      (footprint "eagle-import:H807")
      (libsource (lib "eagle-import") (part "M111"))
    )
    (comp (ref "D10")
      (value "M119")
      (footprint "eagle-import:H807")
      (libsource (lib "eagle-import") (part "M119"))
    )
    (comp (ref "D14")
      (value "M307")
      (footprint "eagle-import:H807")
      (libsource (lib "eagle-import") (part "M307"))
    )
    (comp (ref "D15")
      (value "M401")
      (footprint "eagle-import:H807")
      (libsource (lib "eagle-import") (part "M401"))
    )
    (comp (ref "A12")
      (value "A12")
      (footprint "eagle-import:H807")
      (libsource (lib "eagle-import") (part "M113"))
    )
    (comp (ref "B06")
      (value "B06")
      (footprint "eagle-import:H807")
      (libsource (lib "eagle-import") (part "M111"))
    )
    (comp (ref "B10")
      (value "B10")
      (footprint "eagle-import:H807")
      (libsource (lib "eagle-import") (part "M627"))
    )
    (comp (ref "C01")
      (value "C01")
      (footprint "eagle-import:H807")
      (libsource (lib "eagle-import") (part "M101"))
    )
    (comp (ref "C04")
      (value "C04")
      (footprint "eagle-import:H807")
      (libsource (lib "eagle-import") (part "M103"))
    )
    (comp (ref "C05")
      (value "C05")
      (footprint "eagle-import:H807")
      (libsource (lib "eagle-import") (part "M103"))
    )
    (comp (ref "C06")
      (value "C06")
      (footprint "eagle-import:H807")
      (libsource (lib "eagle-import") (part "M111"))
    )
    (comp (ref "D11")
      (value "M206X")
      (footprint "eagle-import:H807")
      (libsource (lib "eagle-import") (part "M206X"))
    )
    (comp (ref "D12")
      (value "D12")
      (footprint "eagle-import:H807")
      (libsource (lib "eagle-import") (part "M627"))
    )
    (comp (ref "D13")
      (value "D13")
      (footprint "eagle-import:H807")
      (libsource (lib "eagle-import") (part "M602"))
    )
    (comp (ref "D17")
      (value "D17")
      (footprint "eagle-import:H807")
      (libsource (lib "eagle-import") (part "M602"))
    )
    (comp (ref "CD18")
      (value "M228")
      (footprint "eagle-import:H807-2")
      (libsource (lib "eagle-import") (part "M228"))
    )
    (comp (ref "B12")
      (value "M117")
      (footprint "eagle-import:H807")
      (libsource (lib "eagle-import") (part "M117"))
    )
    (comp (ref "A18")
      (value "G888")
      (footprint "eagle-import:H807")
      (libsource (lib "eagle-import") (part "G888"))
    )
    (comp (ref "A20")
      (value "G888")
      (footprint "eagle-import:H807")
      (libsource (lib "eagle-import") (part "G888"))
    )
    (comp (ref "A21")
      (value "G888")
      (footprint "eagle-import:H807")
      (libsource (lib "eagle-import") (part "G888"))
    )
    (comp (ref "AB01")
      (value "G821")
      (footprint "eagle-import:H807-2")
      (libsource (lib "eagle-import") (part "G821"))
    )
    (comp (ref "AB19")
      (value "W032")
      (footprint "eagle-import:H807-2")
      (libsource (lib "eagle-import") (part "W032"))
    )
    (comp (ref "B18")
      (value "G888")
      (footprint "eagle-import:H807")
      (libsource (lib "eagle-import") (part "G888"))
    )
    (comp (ref "B20")
      (value "G888")
      (footprint "eagle-import:H807")
      (libsource (lib "eagle-import") (part "G888"))
    )
    (comp (ref "A02")
      (value "M903")
      (footprint "eagle-import:H807")
      (libsource (lib "eagle-import") (part "M903"))
    )
    (comp (ref "A03")
      (value "M903")
      (footprint "eagle-import:H807")
      (libsource (lib "eagle-import") (part "M903"))
    )
    (comp (ref "A04")
      (value "M903")
      (footprint "eagle-import:H807")
      (libsource (lib "eagle-import") (part "M903"))
    )
    (comp (ref "A05")
      (value "M903")
      (footprint "eagle-import:H807")
      (libsource (lib "eagle-import") (part "M903"))
    )
    (comp (ref "A06")
      (value "M903")
      (footprint "eagle-import:H807")
      (libsource (lib "eagle-import") (part "M903"))
    )
    (comp (ref "A13")
      (value "H807")
      (footprint "eagle-import:H807")
      (libsource (lib "eagle-import") (part "H807"))
    )
    (comp (ref "A17")
      (value "H807")
      (footprint "eagle-import:H807")
      (libsource (lib "eagle-import") (part "H807"))
    )
    (comp (ref "A24")
      (value "W023")
      (footprint "eagle-import:H807")
      (libsource (lib "eagle-import") (part "W023"))
    )
    (comp (ref "A25")
      (value "M916")
      (footprint "eagle-import:H807")
      (libsource (lib "eagle-import") (part "M916"))
    )
    (comp (ref "A26")
      (value "M916")
      (footprint "eagle-import:H807")
      (libsource (lib "eagle-import") (part "M916"))
    )
    (comp (ref "A27")
      (value "H807")
      (footprint "eagle-import:H807")
      (libsource (lib "eagle-import") (part "H807"))
    )
    (comp (ref "A28")
      (value "H807")
      (footprint "eagle-import:H807")
      (libsource (lib "eagle-import") (part "H807"))
    )
    (comp (ref "B17")
      (value "H807")
      (footprint "eagle-import:H807")
      (libsource (lib "eagle-import") (part "H807"))
    )
    (comp (ref "B24")
      (value "H807")
      (footprint "eagle-import:H807")
      (libsource (lib "eagle-import") (part "H807"))
    )
    (comp (ref "B25")
      (value "H807")
      (footprint "eagle-import:H807")
      (libsource (lib "eagle-import") (part "H807"))
    )
    (comp (ref "B26")
      (value "H807")
      (footprint "eagle-import:H807")
      (libsource (lib "eagle-import") (part "H807"))
    )
    (comp (ref "B27")
      (value "H807")
      (footprint "eagle-import:H807")
      (libsource (lib "eagle-import") (part "H807"))
    )
    (comp (ref "B28")
      (value "H807")
      (footprint "eagle-import:H807")
      (libsource (lib "eagle-import") (part "H807"))
    )
    (comp (ref "C19")
      (value "H807")
      (footprint "eagle-import:H807")
      (libsource (lib "eagle-import") (part "H807"))
    )
    (comp (ref "C20")
      (value "H807")
      (footprint "eagle-import:H807")
      (libsource (lib "eagle-import") (part "H807"))
    )
    (comp (ref "C21")
      (value "H807")
      (footprint "eagle-import:H807")
      (libsource (lib "eagle-import") (part "H807"))
    )
    (comp (ref "C22")
      (value "H807")
      (footprint "eagle-import:H807")
      (libsource (lib "eagle-import") (part "H807"))
    )
    (comp (ref "C23")
      (value "H807")
      (footprint "eagle-import:H807")
      (libsource (lib "eagle-import") (part "H807"))
    )
    (comp (ref "C24")
      (value "H807")
      (footprint "eagle-import:H807")
      (libsource (lib "eagle-import") (part "H807"))
    )
    (comp (ref "C25")
      (value "H807")
      (footprint "eagle-import:H807")
      (libsource (lib "eagle-import") (part "H807"))
    )
    (comp (ref "C26")
      (value "H807")
      (footprint "eagle-import:H807")
      (libsource (lib "eagle-import") (part "H807"))
    )
    (comp (ref "C27")
      (value "H807")
      (footprint "eagle-import:H807")
      (libsource (lib "eagle-import") (part "H807"))
    )
    (comp (ref "C28")
      (value "H807")
      (footprint "eagle-import:H807")
      (libsource (lib "eagle-import") (part "H807"))
    )
    (comp (ref "D01")
      (value "H807")
      (footprint "eagle-import:H807")
      (libsource (lib "eagle-import") (part "H807"))
    )
    (comp (ref "D02")
      (value "M903")
      (footprint "eagle-import:H807")
      (libsource (lib "eagle-import") (part "M903"))
    )
    (comp (ref "D03")
      (value "M903")
      (footprint "eagle-import:H807")
      (libsource (lib "eagle-import") (part "M903"))
    )
    (comp (ref "D04")
      (value "M903")
      (footprint "eagle-import:H807")
      (libsource (lib "eagle-import") (part "M903"))
    )
    (comp (ref "D05")
      (value "M903")
      (footprint "eagle-import:H807")
      (libsource (lib "eagle-import") (part "M903"))
    )
    (comp (ref "D06")
      (value "M903")
      (footprint "eagle-import:H807")
      (libsource (lib "eagle-import") (part "M903"))
    )
    (comp (ref "D19")
      (value "H807")
      (footprint "eagle-import:H807")
      (libsource (lib "eagle-import") (part "H807"))
    )
    (comp (ref "D20")
      (value "H807")
      (footprint "eagle-import:H807")
      (libsource (lib "eagle-import") (part "H807"))
    )
    (comp (ref "D21")
      (value "H807")
      (footprint "eagle-import:H807")
      (libsource (lib "eagle-import") (part "H807"))
    )
    (comp (ref "D22")
      (value "H807")
      (footprint "eagle-import:H807")
      (libsource (lib "eagle-import") (part "H807"))
    )
    (comp (ref "D23")
      (value "H807")
      (footprint "eagle-import:H807")
      (libsource (lib "eagle-import") (part "H807"))
    )
    (comp (ref "D24")
      (value "H807")
      (footprint "eagle-import:H807")
      (libsource (lib "eagle-import") (part "H807"))
    )
    (comp (ref "D25")
      (value "H807")
      (footprint "eagle-import:H807")
      (libsource (lib "eagle-import") (part "H807"))
    )
    (comp (ref "D26")
      (value "H807")
      (footprint "eagle-import:H807")
      (libsource (lib "eagle-import") (part "H807"))
    )
    (comp (ref "D27")
      (value "H807")
      (footprint "eagle-import:H807")
      (libsource (lib "eagle-import") (part "H807"))
    )
    (comp (ref "D28")
      (value "H807")
      (footprint "eagle-import:H807")
      (libsource (lib "eagle-import") (part "H807"))
    )
    (comp (ref "B02")
      (value "M623")
      (footprint "eagle-import:H807")
      (libsource (lib "eagle-import") (part "M623"))
    )
    (comp (ref "B03")
      (value "M623")
      (footprint "eagle-import:H807")
      (libsource (lib "eagle-import") (part "M623"))
    )
    (comp (ref "B04")
      (value "M623")
      (footprint "eagle-import:H807")
      (libsource (lib "eagle-import") (part "M623"))
    )
    (comp (ref "B05")
      (value "M623")
      (footprint "eagle-import:H807")
      (libsource (lib "eagle-import") (part "M623"))
    )
    (comp (ref "C02")
      (value "M101-ARRAY")
      (footprint "eagle-import:H807")
      (libsource (lib "eagle-import") (part "M101-ARRAY"))
    )
    (comp (ref "C03")
      (value "M101-ARRAY")
      (footprint "eagle-import:H807")
      (libsource (lib "eagle-import") (part "M101-ARRAY"))
    )
    (comp (ref "C11")
      (value "M113")
      (footprint "eagle-import:H807")
      (libsource (lib "eagle-import") (part "M113"))
    )
    (comp (ref "D08")
      (value "M207")
      (footprint "eagle-import:H807")
      (libsource (lib "eagle-import") (part "M207"))
    )
    (comp (ref "A08")
      (value "M206X")
      (footprint "eagle-import:H807")
      (libsource (lib "eagle-import") (part "M206X"))
    )
    (comp (ref "B21")
      (value "G879")
      (footprint "eagle-import:H807")
      (libsource (lib "eagle-import") (part "G879"))
    )
    (comp (ref "D16")
      (value "M302")
      (footprint "eagle-import:H807")
      (libsource (lib "eagle-import") (part "M302"))
    )
    (comp (ref "B13")
      (value "M206X")
      (footprint "eagle-import:H807")
      (libsource (lib "eagle-import") (part "M206X"))
    )
  )
  (nets
    (net (code "1") (name "+3V@A09U1") (class "Default")
      (node (ref "A07") (pin "S1") (pinfunction "EN2_S1") (pintype "input"))
      (node (ref "A07") (pin "S2") (pinfunction "EN1_S2") (pintype "input"))
      (node (ref "A07") (pin "T2") (pinfunction "EN3_T2") (pintype "input"))
      (node (ref "A08") (pin "D1") (pinfunction "S_D1") (pintype "input"))
      (node (ref "A08") (pin "F2") (pinfunction "S_F2") (pintype "input"))
      (node (ref "A08") (pin "K2") (pinfunction "R_K2") (pintype "input"))
      (node (ref "A09") (pin "U1") (pinfunction "P$1_U1") (pintype "output"))
      (node (ref "B13") (pin "R1") (pinfunction "S_R1") (pintype "input"))
      (node (ref "B13") (pin "U2") (pinfunction "S_U2") (pintype "input"))
    )
    (net (code "2") (name "+3V@B12U1") (class "Default")
      (node (ref "B12") (pin "U1") (pinfunction "P$1_U1") (pintype "output"))
      (node (ref "B13") (pin "D1") (pinfunction "S_D1") (pintype "input"))
      (node (ref "B13") (pin "F2") (pinfunction "S_F2") (pintype "input"))
      (node (ref "B13") (pin "K1") (pinfunction "S_K1") (pintype "input"))
      (node (ref "B14") (pin "A1") (pinfunction "R_A1") (pintype "input"))
      (node (ref "B14") (pin "K2") (pinfunction "R_K2") (pintype "input"))
      (node (ref "B14") (pin "N2") (pinfunction "S_N2") (pintype "input"))
      (node (ref "B14") (pin "R1") (pinfunction "S_R1") (pintype "input"))
      (node (ref "B14") (pin "U2") (pinfunction "S_U2") (pintype "input"))
    )
    (net (code "3") (name "+3V@C08U1") (class "Default")
      (node (ref "C01") (pin "C1") (pinfunction "IN2_C1") (pintype "input"))
      (node (ref "C02") (pin "C1") (pinfunction "ENABLE_C1") (pintype "input"))
      (node (ref "C04") (pin "J1") (pinfunction "IN2_J1") (pintype "input"))
      (node (ref "C04") (pin "L2") (pinfunction "L2_L2") (pintype "input"))
      (node (ref "C04") (pin "N2") (pinfunction "N2_N2") (pintype "input"))
      (node (ref "C04") (pin "U2") (pinfunction "U2_U2") (pintype "input"))
      (node (ref "C05") (pin "J1") (pinfunction "IN2_J1") (pintype "input"))
      (node (ref "C05") (pin "L2") (pinfunction "L2_L2") (pintype "input"))
      (node (ref "C05") (pin "N2") (pinfunction "N2_N2") (pintype "input"))
      (node (ref "C05") (pin "U2") (pinfunction "U2_U2") (pintype "input"))
      (node (ref "C08") (pin "U1") (pinfunction "P$1_U1") (pintype "output"))
    )
    (net (code "4") (name "+3V@C15U1") (class "Default")
      (node (ref "C14") (pin "A1") (pinfunction "R_A1") (pintype "input"))
      (node (ref "C14") (pin "D1") (pinfunction "S_D1") (pintype "input"))
      (node (ref "C14") (pin "F2") (pinfunction "S_F2") (pintype "input"))
      (node (ref "C14") (pin "K1") (pinfunction "S_K1") (pintype "input"))
      (node (ref "C14") (pin "K2") (pinfunction "R_K2") (pintype "input"))
      (node (ref "C15") (pin "U1") (pinfunction "P$1_U1") (pintype "output"))
      (node (ref "C16") (pin "H2") (pinfunction "IN4_H2") (pintype "input"))
    )
    (net (code "5") (name "+3V@D09U1") (class "Default")
      (node (ref "D07") (pin "S1") (pinfunction "EN2_S1") (pintype "input"))
      (node (ref "D07") (pin "S2") (pinfunction "EN1_S2") (pintype "input"))
      (node (ref "D07") (pin "T2") (pinfunction "EN3_T2") (pintype "input"))
      (node (ref "D09") (pin "U1") (pinfunction "P$1_U1") (pintype "output"))
    )
    (net (code "6") (name "+3V@D10U1") (class "Default")
      (node (ref "D10") (pin "L2") (pinfunction "IN6_L2") (pintype "input"))
      (node (ref "D10") (pin "M2") (pinfunction "IN7_M2") (pintype "input"))
      (node (ref "D10") (pin "N2") (pinfunction "IN8_N2") (pintype "input"))
      (node (ref "D10") (pin "U1") (pinfunction "P$1_U1") (pintype "output"))
      (node (ref "D11") (pin "D1") (pinfunction "S_D1") (pintype "input"))
      (node (ref "D11") (pin "F2") (pinfunction "S_F2") (pintype "input"))
      (node (ref "D11") (pin "K1") (pinfunction "S_K1") (pintype "input"))
      (node (ref "D11") (pin "K2") (pinfunction "R_K2") (pintype "input"))
      (node (ref "D14") (pin "M1") (pinfunction "M1_M1") (pintype "input"))
    )
    (net (code "7") (name "+11V") (class "Default")
      (node (ref "AB01") (pin "BM2") (pinfunction "+11V_BM2") (pintype "power_in"))
    )
    (net (code "8") (name "-15V") (class "Default")
      (node (ref "AB01") (pin "AB2") (pinfunction "-15V_AB2") (pintype "power_in"))
      (node (ref "AB01") (pin "AE2") (pinfunction "-15V_AE2") (pintype "power_in"))
      (node (ref "AB01") (pin "AF2") (pinfunction "-15V_AF2") (pintype "power_in"))
    )
    (net (code "9") (name "00") (class "Default")
      (node (ref "A07") (pin "D2") (pinfunction "O0_D2") (pintype "output"))
    )
    (net (code "10") (name "0_TO_DTB") (class "Default")
      (node (ref "A11") (pin "M1") (pinfunction "OUT_M1") (pintype "output"))
      (node (ref "C11") (pin "R1") (pinfunction "IN2_R1") (pintype "input"))
    )
    (net (code "11") (name "0_TO_EF") (class "Default")
      (node (ref "A10") (pin "K2") (pinfunction "OUT_K2") (pintype "output"))
      (node (ref "A11") (pin "E2") (pinfunction "IN_E2") (pintype "input"))
    )
    (net (code "12") (name "0_TO_STA") (class "Default")
      (node (ref "A10") (pin "N2") (pinfunction "OUT_N2") (pintype "output"))
      (node (ref "A11") (pin "N1") (pinfunction "IN_N1") (pintype "input"))
    )
    (net (code "13") (name "01") (class "Default")
      (node (ref "A07") (pin "E2") (pinfunction "O1_E2") (pintype "output"))
    )
    (net (code "14") (name "1_TO_DF") (class "Default")
      (node (ref "A08") (pin "H1") (pinfunction "C_H1") (pintype "input"))
      (node (ref "C12") (pin "J1") (pinfunction "OUT_J1") (pintype "output"))
      (node (ref "C12") (pin "L1") (pinfunction "IN2_L1") (pintype "input"))
      (node (ref "D11") (pin "L2") (pinfunction "C_L2") (pintype "input"))
    )
    (net (code "15") (name "1_TO_DTF") (class "Default")
      (node (ref "B12") (pin "P2") (pinfunction "OUT_P2") (pintype "output"))
      (node (ref "D11") (pin "S2") (pinfunction "C_S2") (pintype "input"))
    )
    (net (code "16") (name "02") (class "Default")
      (node (ref "A07") (pin "J2") (pinfunction "O2_J2") (pintype "output"))
    )
    (net (code "17") (name "03") (class "Default")
      (node (ref "A07") (pin "N2") (pinfunction "O3_N2") (pintype "output"))
    )
    (net (code "18") (name "04") (class "Default")
      (node (ref "A07") (pin "F2") (pinfunction "O4_F2") (pintype "output"))
    )
    (net (code "19") (name "05") (class "Default")
      (node (ref "A07") (pin "M2") (pinfunction "O5_M2") (pintype "output"))
    )
    (net (code "20") (name "06") (class "Default")
      (node (ref "A07") (pin "H2") (pinfunction "O6_H2") (pintype "output"))
    )
    (net (code "21") (name "07") (class "Default")
      (node (ref "A07") (pin "L2") (pinfunction "O7_L2") (pintype "output"))
    )
    (net (code "22") (name "76") (class "Default")
      (node (ref "C04") (pin "V2") (pinfunction "V2_V2") (pintype "output"))
      (node (ref "C06") (pin "S2") (pinfunction "IN_S2") (pintype "input"))
    )
    (net (code "23") (name "76+77") (class "Default")
      (node (ref "C03") (pin "C1") (pinfunction "ENABLE_C1") (pintype "input"))
      (node (ref "D12") (pin "V2") (pinfunction "OUT_V2") (pintype "output"))
    )
    (net (code "24") (name "77") (class "Default")
      (node (ref "C05") (pin "V2") (pinfunction "V2_V2") (pintype "output"))
      (node (ref "C06") (pin "U2") (pinfunction "IN_U2") (pintype "input"))
    )
    (net (code "25") (name "ADDR_ACC") (class "Default")
      (node (ref "C02") (pin "V2") (pinfunction "O15_V2") (pintype "output"))
      (node (ref "C17") (pin "N1") (pinfunction "IN_N1") (pintype "input"))
    )
    (net (code "26") (name "B-BRK") (class "Default")
      (node (ref "B10") (pin "R2") (pinfunction "IN1_R2") (pintype "input"))
      (node (ref "B10") (pin "S2") (pinfunction "IN2_S2") (pintype "input"))
      (node (ref "B10") (pin "T2") (pinfunction "IN3_T2") (pintype "input"))
      (node (ref "B10") (pin "U2") (pinfunction "IN4_U2") (pintype "input"))
      (node (ref "C01") (pin "E1") (pinfunction "OUT_E1") (pintype "output"))
      (node (ref "D12") (pin "M1") (pinfunction "IN1_M1") (pintype "input"))
    )
    (net (code "27") (name "B-RUN") (class "Default")
      (node (ref "B11") (pin "N2") (pinfunction "IN1_N2") (pintype "input"))
      (node (ref "C01") (pin "B1") (pinfunction "OUT_B1") (pintype "output"))
    )
    (net (code "28") (name "B-XSTA") (class "Default")
      (node (ref "A10") (pin "E2") (pinfunction "IN2_E2") (pintype "input"))
      (node (ref "C11") (pin "P2") (pinfunction "IN1_P2") (pintype "input"))
      (node (ref "D12") (pin "E1") (pinfunction "OUT_E1") (pintype "output"))
    )
    (net (code "29") (name "BAC_00") (class "Default")
      (node (ref "B06") (pin "B1") (pinfunction "OUT_B1") (pintype "output"))
      (node (ref "B07") (pin "C1") (pinfunction "C1_C1") (pintype "input"))
      (node (ref "B07") (pin "D1") (pinfunction "D1_D1") (pintype "input"))
    )
    (net (code "30") (name "BAC_01") (class "Default")
      (node (ref "B06") (pin "E1") (pinfunction "OUT_E1") (pintype "output"))
      (node (ref "B07") (pin "E2") (pinfunction "E2_E2") (pintype "input"))
      (node (ref "B07") (pin "F2") (pinfunction "F2_F2") (pintype "input"))
    )
    (net (code "31") (name "BAC_02") (class "Default")
      (node (ref "B06") (pin "H1") (pinfunction "OUT_H1") (pintype "output"))
      (node (ref "B07") (pin "J1") (pinfunction "J1_J1") (pintype "input"))
      (node (ref "B07") (pin "K1") (pinfunction "K1_K1") (pintype "input"))
    )
    (net (code "32") (name "BAC_03") (class "Default")
      (node (ref "B06") (pin "K1") (pinfunction "OUT_K1") (pintype "output"))
      (node (ref "B07") (pin "M2") (pinfunction "M2_M2") (pintype "input"))
      (node (ref "B07") (pin "N2") (pinfunction "N2_N2") (pintype "input"))
    )
    (net (code "33") (name "BAC_04") (class "Default")
      (node (ref "B06") (pin "M1") (pinfunction "OUT_M1") (pintype "output"))
      (node (ref "C07") (pin "M2") (pinfunction "M2_M2") (pintype "input"))
      (node (ref "C07") (pin "N2") (pinfunction "N2_N2") (pintype "input"))
    )
    (net (code "34") (name "BAC_05") (class "Default")
      (node (ref "B06") (pin "P1") (pinfunction "OUT_P1") (pintype "output"))
      (node (ref "B07") (pin "P1") (pinfunction "P1_P1") (pintype "input"))
      (node (ref "B07") (pin "R1") (pinfunction "R1_R1") (pintype "input"))
    )
    (net (code "35") (name "BAC_06") (class "Default")
      (node (ref "B06") (pin "S1") (pinfunction "OUT_S1") (pintype "output"))
      (node (ref "B07") (pin "T2") (pinfunction "T2_T2") (pintype "input"))
      (node (ref "B07") (pin "U2") (pinfunction "U2_U2") (pintype "input"))
      (node (ref "D11") (pin "C1") (pinfunction "D_C1") (pintype "input"))
    )
    (net (code "36") (name "BAC_07") (class "Default")
      (node (ref "B06") (pin "U1") (pinfunction "OUT_U1") (pintype "output"))
      (node (ref "C07") (pin "C1") (pinfunction "C1_C1") (pintype "input"))
      (node (ref "C07") (pin "D1") (pinfunction "D1_D1") (pintype "input"))
      (node (ref "D11") (pin "E2") (pinfunction "D_E2") (pintype "input"))
    )
    (net (code "37") (name "BAC_08") (class "Default")
      (node (ref "B06") (pin "D2") (pinfunction "OUT_D2") (pintype "output"))
      (node (ref "C07") (pin "E2") (pinfunction "E2_E2") (pintype "input"))
      (node (ref "C07") (pin "F2") (pinfunction "F2_F2") (pintype "input"))
      (node (ref "D11") (pin "J1") (pinfunction "D_J1") (pintype "input"))
    )
    (net (code "38") (name "BAC_09") (class "Default")
      (node (ref "B06") (pin "F2") (pinfunction "OUT_F2") (pintype "output"))
      (node (ref "C07") (pin "J1") (pinfunction "J1_J1") (pintype "input"))
      (node (ref "C07") (pin "K1") (pinfunction "K1_K1") (pintype "input"))
    )
    (net (code "39") (name "BAC_10") (class "Default")
      (node (ref "B06") (pin "J2") (pinfunction "OUT_J2") (pintype "output"))
    )
    (net (code "40") (name "BAC_11") (class "Default")
      (node (ref "B06") (pin "L2") (pinfunction "OUT_L2") (pintype "output"))
    )
    (net (code "41") (name "BLK_IN_SYNC") (class "Default")
      (node (ref "C11") (pin "E2") (pinfunction "IN2_E2") (pintype "input"))
      (node (ref "C13") (pin "S1") (pinfunction "OUT_S1") (pintype "output"))
      (node (ref "CD18") (pin "AP2") (pinfunction "AP2_AP2") (pintype "input"))
    )
    (net (code "42") (name "BMB_00") (class "Default")
      (node (ref "C06") (pin "B1") (pinfunction "OUT_B1") (pintype "output"))
      (node (ref "C08") (pin "B1") (pinfunction "IN1B_B1") (pintype "input"))
    )
    (net (code "43") (name "BMB_01") (class "Default")
      (node (ref "C06") (pin "E1") (pinfunction "OUT_E1") (pintype "output"))
      (node (ref "C08") (pin "H1") (pinfunction "IN1B_H1") (pintype "input"))
    )
    (net (code "44") (name "BMB_02") (class "Default")
      (node (ref "C06") (pin "H1") (pinfunction "OUT_H1") (pintype "output"))
      (node (ref "C08") (pin "N1") (pinfunction "IN1B_N1") (pintype "input"))
    )
    (net (code "45") (name "BMB_03") (class "Default")
      (node (ref "C06") (pin "K1") (pinfunction "OUT_K1") (pintype "output"))
      (node (ref "C08") (pin "E2") (pinfunction "IN1B_E2") (pintype "input"))
    )
    (net (code "46") (name "BMB_04") (class "Default")
      (node (ref "C06") (pin "M1") (pinfunction "OUT_M1") (pintype "output"))
      (node (ref "C08") (pin "L2") (pinfunction "IN1B_L2") (pintype "input"))
    )
    (net (code "47") (name "BMB_05") (class "Default")
      (node (ref "C06") (pin "P1") (pinfunction "OUT_P1") (pintype "output"))
      (node (ref "C08") (pin "S2") (pinfunction "IN1B_S2") (pintype "input"))
    )
    (net (code "48") (name "BMB_06") (class "Default")
      (node (ref "B08") (pin "B1") (pinfunction "IN2_B1") (pintype "input"))
      (node (ref "C06") (pin "S1") (pinfunction "OUT_S1") (pintype "output"))
    )
    (net (code "49") (name "BMB_07") (class "Default")
      (node (ref "B08") (pin "E1") (pinfunction "IN2_E1") (pintype "input"))
      (node (ref "C06") (pin "U1") (pinfunction "OUT_U1") (pintype "output"))
    )
    (net (code "50") (name "BMB_08") (class "Default")
      (node (ref "B08") (pin "E2") (pinfunction "IN2_E2") (pintype "input"))
      (node (ref "C06") (pin "D2") (pinfunction "OUT_D2") (pintype "output"))
    )
    (net (code "51") (name "BMB_09") (class "Default")
      (node (ref "B08") (pin "M1") (pinfunction "IN2_M1") (pintype "input"))
      (node (ref "C06") (pin "F2") (pinfunction "OUT_F2") (pintype "output"))
    )
    (net (code "52") (name "BMB_10") (class "Default")
      (node (ref "B08") (pin "R1") (pinfunction "IN2_R1") (pintype "input"))
      (node (ref "C06") (pin "J2") (pinfunction "OUT_J2") (pintype "output"))
    )
    (net (code "53") (name "BMB_11") (class "Default")
      (node (ref "B08") (pin "J1") (pinfunction "IN2_J1") (pintype "input"))
      (node (ref "C06") (pin "L2") (pinfunction "OUT_L2") (pintype "output"))
    )
    (net (code "54") (name "BMB_TO_DTB") (class "Default")
      (node (ref "B08") (pin "A1") (pinfunction "IN1_A1") (pintype "input"))
      (node (ref "B08") (pin "D1") (pinfunction "IN1_D1") (pintype "input"))
      (node (ref "B08") (pin "D2") (pinfunction "IN1_D2") (pintype "input"))
      (node (ref "B08") (pin "H1") (pinfunction "IN1_H1") (pintype "input"))
      (node (ref "B08") (pin "L1") (pinfunction "IN1_L1") (pintype "input"))
      (node (ref "B08") (pin "P1") (pinfunction "IN1_P1") (pintype "input"))
      (node (ref "C08") (pin "A1") (pinfunction "IN1A_A1") (pintype "input"))
      (node (ref "C08") (pin "D2") (pinfunction "IN1A_D2") (pintype "input"))
      (node (ref "C08") (pin "F1") (pinfunction "IN1A_F1") (pintype "input"))
      (node (ref "C08") (pin "K2") (pinfunction "IN1A_K2") (pintype "input"))
      (node (ref "C08") (pin "M1") (pinfunction "IN1A_M1") (pintype "input"))
      (node (ref "C08") (pin "R2") (pinfunction "IN1A_R2") (pintype "input"))
      (node (ref "D12") (pin "L1") (pinfunction "OUT_L1") (pintype "output"))
    )
    (net (code "55") (name "BMR00") (class "Default")
      (node (ref "A23") (pin "F1") (pinfunction "A_F1") (pintype "input"))
      (node (ref "B14") (pin "P2") (pinfunction "1_P2") (pintype "output"))
    )
    (net (code "56") (name "BMR01") (class "Default")
      (node (ref "A23") (pin "B1") (pinfunction "B_B1") (pintype "input"))
      (node (ref "B14") (pin "F1") (pinfunction "0_F1") (pintype "output"))
    )
    (net (code "57") (name "C00") (class "Default")
      (node (ref "A12") (pin "L2") (pinfunction "IN1_L2") (pintype "input"))
      (node (ref "A26") (pin "E2") (pinfunction "P$2_E2") (pintype "bidirectional"))
      (node (ref "B12") (pin "R2") (pinfunction "IN1_R2") (pintype "input"))
      (node (ref "B13") (pin "S1") (pinfunction "1_S1") (pintype "output"))
      (node (ref "C15") (pin "E2") (pinfunction "IN2_E2") (pintype "input"))
      (node (ref "D10") (pin "C1") (pinfunction "IN3_C1") (pintype "input"))
    )
    (net (code "58") (name "C01") (class "Default")
      (node (ref "A12") (pin "M2") (pinfunction "IN2_M2") (pintype "input"))
      (node (ref "A26") (pin "F2") (pinfunction "P$2_F2") (pintype "bidirectional"))
      (node (ref "B10") (pin "J1") (pinfunction "IN3_J1") (pintype "input"))
      (node (ref "B11") (pin "V2") (pinfunction "IN3_V2") (pintype "input"))
      (node (ref "B13") (pin "P2") (pinfunction "1_P2") (pintype "output"))
    )
    (net (code "59") (name "CK00") (class "Default")
      (node (ref "A18") (pin "P2") (pinfunction "P2_P2") (pintype "input"))
      (node (ref "B14") (pin "S1") (pinfunction "1_S1") (pintype "output"))
    )
    (net (code "60") (name "CK01") (class "Default")
      (node (ref "B14") (pin "P1") (pinfunction "D_P1") (pintype "input"))
      (node (ref "B14") (pin "V2") (pinfunction "1_V2") (pintype "output"))
      (node (ref "C16") (pin "N1") (pinfunction "IN2_N1") (pintype "input"))
      (node (ref "C16") (pin "P1") (pinfunction "IN3_P1") (pintype "input"))
      (node (ref "C16") (pin "R1") (pinfunction "IN4_R1") (pintype "input"))
    )
    (net (code "61") (name "COMP+SH") (class "Default")
      (node (ref "A12") (pin "D2") (pinfunction "IN1_D2") (pintype "input"))
      (node (ref "C14") (pin "B1") (pinfunction "C_B1") (pintype "input"))
      (node (ref "C14") (pin "D2") (pinfunction "C_D2") (pintype "input"))
      (node (ref "C14") (pin "H1") (pinfunction "C_H1") (pintype "input"))
      (node (ref "C15") (pin "K1") (pinfunction "OUT_K1") (pintype "output"))
    )
    (net (code "62") (name "CSTA") (class "Default")
      (node (ref "C04") (pin "D1") (pinfunction "D1_D1") (pintype "output"))
      (node (ref "D16") (pin "P2") (pinfunction "K2_P2") (pintype "input"))
    )
    (net (code "63") (name "DATA") (class "Default")
      (node (ref "A26") (pin "M1") (pinfunction "P$2_M1") (pintype "bidirectional"))
      (node (ref "C13") (pin "F1") (pinfunction "IN_F1") (pintype "input"))
      (node (ref "CD18") (pin "BK2") (pinfunction "BK2_BK2") (pintype "output"))
    )
    (net (code "64") (name "DF") (class "Default")
      (node (ref "A10") (pin "P2") (pinfunction "IN1_P2") (pintype "input"))
      (node (ref "A26") (pin "E1") (pinfunction "P$2_E1") (pintype "bidirectional"))
      (node (ref "D11") (pin "R2") (pinfunction "0_R2") (pintype "output"))
    )
    (net (code "65") (name "DTB_00") (class "Default")
      (node (ref "A25") (pin "A2") (pinfunction "P$2_A2") (pintype "bidirectional"))
      (node (ref "C09") (pin "E1") (pinfunction "1_E1") (pintype "output"))
      (node (ref "C10") (pin "B1") (pinfunction "IN1B_B1") (pintype "input"))
      (node (ref "D09") (pin "D2") (pinfunction "IN1A_D2") (pintype "input"))
    )
    (net (code "66") (name "DTB_01") (class "Default")
      (node (ref "A25") (pin "B2") (pinfunction "P$2_B2") (pintype "bidirectional"))
      (node (ref "C09") (pin "H2") (pinfunction "1_H2") (pintype "output"))
      (node (ref "C10") (pin "H1") (pinfunction "IN1B_H1") (pintype "input"))
      (node (ref "D09") (pin "K2") (pinfunction "IN1A_K2") (pintype "input"))
    )
    (net (code "67") (name "DTB_02") (class "Default")
      (node (ref "A25") (pin "C2") (pinfunction "P$2_C2") (pintype "bidirectional"))
      (node (ref "C09") (pin "L1") (pinfunction "1_L1") (pintype "output"))
      (node (ref "C10") (pin "N1") (pinfunction "IN1B_N1") (pintype "input"))
      (node (ref "D09") (pin "R2") (pinfunction "IN1A_R2") (pintype "input"))
    )
    (net (code "68") (name "DTB_03") (class "Default")
      (node (ref "A25") (pin "D2") (pinfunction "P$2_D2") (pintype "bidirectional"))
      (node (ref "C09") (pin "C1") (pinfunction "D_C1") (pintype "input"))
      (node (ref "C09") (pin "P2") (pinfunction "1_P2") (pintype "output"))
    )
    (net (code "69") (name "DTB_04") (class "Default")
      (node (ref "A25") (pin "E2") (pinfunction "P$2_E2") (pintype "bidirectional"))
      (node (ref "C09") (pin "E2") (pinfunction "D_E2") (pintype "input"))
      (node (ref "C09") (pin "S1") (pinfunction "1_S1") (pintype "output"))
    )
    (net (code "70") (name "DTB_05") (class "Default")
      (node (ref "A25") (pin "F2") (pinfunction "P$2_F2") (pintype "bidirectional"))
      (node (ref "C09") (pin "J1") (pinfunction "D_J1") (pintype "input"))
      (node (ref "C09") (pin "V2") (pinfunction "1_V2") (pintype "output"))
    )
    (net (code "71") (name "DTB_06") (class "Default")
      (node (ref "A25") (pin "H2") (pinfunction "P$2_H2") (pintype "bidirectional"))
      (node (ref "B09") (pin "E1") (pinfunction "1_E1") (pintype "output"))
      (node (ref "C09") (pin "M2") (pinfunction "D_M2") (pintype "input"))
    )
    (net (code "72") (name "DTB_07") (class "Default")
      (node (ref "A25") (pin "J2") (pinfunction "P$2_J2") (pintype "bidirectional"))
      (node (ref "B09") (pin "V2") (pinfunction "1_V2") (pintype "output"))
      (node (ref "C09") (pin "P1") (pinfunction "D_P1") (pintype "input"))
    )
    (net (code "73") (name "DTB_08") (class "Default")
      (node (ref "A25") (pin "K2") (pinfunction "P$2_K2") (pintype "bidirectional"))
      (node (ref "B09") (pin "L1") (pinfunction "1_L1") (pintype "output"))
      (node (ref "C09") (pin "T2") (pinfunction "D_T2") (pintype "input"))
    )
    (net (code "74") (name "DTB_09") (class "Default")
      (node (ref "A25") (pin "L2") (pinfunction "P$2_L2") (pintype "bidirectional"))
      (node (ref "B09") (pin "C1") (pinfunction "D_C1") (pintype "input"))
      (node (ref "B09") (pin "P2") (pinfunction "1_P2") (pintype "output"))
    )
    (net (code "75") (name "DTB_10") (class "Default")
      (node (ref "A25") (pin "M2") (pinfunction "P$2_M2") (pintype "bidirectional"))
      (node (ref "B09") (pin "S1") (pinfunction "1_S1") (pintype "output"))
      (node (ref "B09") (pin "T2") (pinfunction "D_T2") (pintype "input"))
    )
    (net (code "76") (name "DTB_11") (class "Default")
      (node (ref "A25") (pin "N2") (pinfunction "P$2_N2") (pintype "bidirectional"))
      (node (ref "B09") (pin "H2") (pinfunction "1_H2") (pintype "output"))
      (node (ref "B09") (pin "J1") (pinfunction "D_J1") (pintype "input"))
    )
    (net (code "77") (name "DTF") (class "Default")
      (node (ref "A08") (pin "J1") (pinfunction "D_J1") (pintype "input"))
      (node (ref "A12") (pin "M1") (pinfunction "IN2_M1") (pintype "input"))
      (node (ref "A26") (pin "C1") (pinfunction "P$2_C1") (pintype "bidirectional"))
      (node (ref "D11") (pin "V1") (pinfunction "0_V1") (pintype "output"))
    )
    (net (code "78") (name "DTSF") (class "Default")
      (node (ref "A12") (pin "R1") (pinfunction "IN2_R1") (pintype "input"))
      (node (ref "C05") (pin "B1") (pinfunction "B1_B1") (pintype "output"))
    )
    (net (code "79") (name "EF") (class "Default")
      (node (ref "A11") (pin "J1") (pinfunction "IN_J1") (pintype "input"))
      (node (ref "A12") (pin "F1") (pinfunction "OUT_F1") (pintype "output"))
      (node (ref "A12") (pin "L1") (pinfunction "IN1_L1") (pintype "input"))
      (node (ref "A25") (pin "N1") (pinfunction "P$2_N1") (pintype "bidirectional"))
    )
    (net (code "80") (name "END") (class "Default")
      (node (ref "A08") (pin "E1") (pinfunction "1_E1") (pintype "output"))
      (node (ref "A25") (pin "R1") (pinfunction "P$2_R1") (pintype "bidirectional"))
    )
    (net (code "81") (name "ENI") (class "Default")
      (node (ref "A12") (pin "H1") (pinfunction "IN1_H1") (pintype "input"))
      (node (ref "A25") (pin "L1") (pinfunction "P$2_L1") (pintype "bidirectional"))
      (node (ref "C07") (pin "L1") (pinfunction "L1_L1") (pintype "output"))
    )
    (net (code "82") (name "FR_00") (class "Default")
      (node (ref "A25") (pin "F1") (pinfunction "P$2_F1") (pintype "bidirectional"))
      (node (ref "B07") (pin "S1") (pinfunction "S1_S1") (pintype "output"))
      (node (ref "B12") (pin "E2") (pinfunction "IN2_E2") (pintype "input"))
      (node (ref "C12") (pin "U2") (pinfunction "IN2_U2") (pintype "input"))
    )
    (net (code "83") (name "FR_01") (class "Default")
      (node (ref "A10") (pin "H1") (pinfunction "IN1_H1") (pintype "input"))
      (node (ref "A25") (pin "H1") (pinfunction "P$2_H1") (pintype "bidirectional"))
      (node (ref "B07") (pin "V2") (pinfunction "V2_V2") (pintype "output"))
      (node (ref "B15") (pin "M1") (pinfunction "IN2_M1") (pintype "input"))
      (node (ref "C15") (pin "D1") (pinfunction "IN1_D1") (pintype "input"))
      (node (ref "D07") (pin "V2") (pinfunction "IN2_V2") (pintype "input"))
      (node (ref "D12") (pin "R1") (pinfunction "IN4_R1") (pintype "input"))
    )
    (net (code "84") (name "FR_02") (class "Default")
      (node (ref "A25") (pin "J1") (pinfunction "P$2_J1") (pintype "bidirectional"))
      (node (ref "C07") (pin "E1") (pinfunction "E1_E1") (pintype "output"))
      (node (ref "D07") (pin "U2") (pinfunction "IN1_U2") (pintype "input"))
    )
    (net (code "85") (name "FR_03") (class "Default")
      (node (ref "A25") (pin "K1") (pinfunction "P$2_K1") (pintype "bidirectional"))
      (node (ref "B15") (pin "R2") (pinfunction "IN2_R2") (pintype "input"))
      (node (ref "C07") (pin "H2") (pinfunction "H2_H2") (pintype "output"))
      (node (ref "D07") (pin "V1") (pinfunction "IN0_V1") (pintype "input"))
    )
    (net (code "86") (name "GND") (class "Default")
      (node (ref "A05") (pin "B1") (pinfunction "P$2_B1") (pintype "bidirectional"))
      (node (ref "A05") (pin "D1") (pinfunction "P$2_D1") (pintype "bidirectional"))
      (node (ref "A05") (pin "D2") (pinfunction "P$2_D2") (pintype "bidirectional"))
      (node (ref "A05") (pin "E1") (pinfunction "P$2_E1") (pintype "bidirectional"))
      (node (ref "A05") (pin "H1") (pinfunction "P$2_H1") (pintype "bidirectional"))
      (node (ref "A05") (pin "J1") (pinfunction "P$2_J1") (pintype "bidirectional"))
      (node (ref "A05") (pin "L1") (pinfunction "P$2_L1") (pintype "bidirectional"))
      (node (ref "A05") (pin "M1") (pinfunction "P$2_M1") (pintype "bidirectional"))
      (node (ref "A05") (pin "P1") (pinfunction "P$2_P1") (pintype "bidirectional"))
      (node (ref "A05") (pin "S1") (pinfunction "P$2_S1") (pintype "bidirectional"))
      (node (ref "A06") (pin "K2") (pinfunction "P$2_K2") (pintype "bidirectional"))
      (node (ref "A07") (pin "U1") (pinfunction "IN*_U1") (pintype "input"))
      (node (ref "A08") (pin "T2") (pinfunction "D_T2") (pintype "input"))
      (node (ref "A23") (pin "C1") (pinfunction "C_C1") (pintype "input"))
      (node (ref "A23") (pin "F2") (pinfunction "C_F2") (pintype "input"))
      (node (ref "A23") (pin "J1") (pinfunction "C_J1") (pintype "input"))
      (node (ref "A23") (pin "M2") (pinfunction "C_M2") (pintype "input"))
      (node (ref "A23") (pin "P1") (pinfunction "C_P1") (pintype "input"))
      (node (ref "A23") (pin "T2") (pinfunction "C_T2") (pintype "input"))
      (node (ref "A25") (pin "M1") (pinfunction "P$2_M1") (pintype "bidirectional"))
      (node (ref "A26") (pin "D2") (pinfunction "P$2_D2") (pintype "bidirectional"))
      (node (ref "A26") (pin "U2") (pinfunction "P$2_U2") (pintype "bidirectional"))
      (node (ref "A26") (pin "V1") (pinfunction "P$2_V1") (pintype "bidirectional"))
      (node (ref "AB01") (pin "AC2") (pinfunction "GND_AC2") (pintype "power_in"))
      (node (ref "AB01") (pin "AH2") (pinfunction "GND_AH2") (pintype "power_in"))
      (node (ref "AB01") (pin "AK2") (pinfunction "GND_AK2") (pintype "power_in"))
      (node (ref "AB01") (pin "AL2") (pinfunction "GND_AL2") (pintype "power_in"))
      (node (ref "AB01") (pin "AT1") (pinfunction "GND_AT1") (pintype "power_in"))
      (node (ref "AB01") (pin "BC2") (pinfunction "GND_BC2") (pintype "power_in"))
      (node (ref "AB01") (pin "BD2") (pinfunction "GND_BD2") (pintype "power_in"))
      (node (ref "AB01") (pin "BH2") (pinfunction "GND_BH2") (pintype "power_in"))
      (node (ref "AB01") (pin "BK2") (pinfunction "GND_BK2") (pintype "power_in"))
      (node (ref "AB01") (pin "BL2") (pinfunction "GND_BL2") (pintype "power_in"))
      (node (ref "AB01") (pin "BT1") (pinfunction "GND_BT1") (pintype "power_in"))
      (node (ref "AB19") (pin "AJ2") (pinfunction "P$2_AJ2") (pintype "bidirectional"))
      (node (ref "AB19") (pin "AR2") (pinfunction "P$2_AR2") (pintype "bidirectional"))
      (node (ref "AB19") (pin "AU2") (pinfunction "P$2_AU2") (pintype "bidirectional"))
      (node (ref "AB19") (pin "BF2") (pinfunction "P$2_BF2") (pintype "bidirectional"))
      (node (ref "AB19") (pin "BM2") (pinfunction "P$2_BM2") (pintype "bidirectional"))
      (node (ref "B05") (pin "C1") (pinfunction "C_C1") (pintype "input"))
      (node (ref "B05") (pin "F2") (pinfunction "C_F2") (pintype "input"))
      (node (ref "B05") (pin "J1") (pinfunction "C_J1") (pintype "input"))
      (node (ref "B05") (pin "M2") (pinfunction "C_M2") (pintype "input"))
      (node (ref "B05") (pin "P1") (pinfunction "C_P1") (pintype "input"))
      (node (ref "B22") (pin "T2") (pinfunction "C_T2") (pintype "input"))
      (node (ref "D05") (pin "B1") (pinfunction "P$2_B1") (pintype "bidirectional"))
      (node (ref "D05") (pin "D1") (pinfunction "P$2_D1") (pintype "bidirectional"))
      (node (ref "D05") (pin "D2") (pinfunction "P$2_D2") (pintype "bidirectional"))
      (node (ref "D05") (pin "E1") (pinfunction "P$2_E1") (pintype "bidirectional"))
      (node (ref "D05") (pin "H1") (pinfunction "P$2_H1") (pintype "bidirectional"))
      (node (ref "D05") (pin "J1") (pinfunction "P$2_J1") (pintype "bidirectional"))
      (node (ref "D05") (pin "L1") (pinfunction "P$2_L1") (pintype "bidirectional"))
      (node (ref "D05") (pin "M1") (pinfunction "P$2_M1") (pintype "bidirectional"))
      (node (ref "D05") (pin "P1") (pinfunction "P$2_P1") (pintype "bidirectional"))
      (node (ref "D05") (pin "S1") (pinfunction "P$2_S1") (pintype "bidirectional"))
      (node (ref "D06") (pin "K2") (pinfunction "P$2_K2") (pintype "bidirectional"))
      (node (ref "D07") (pin "U1") (pinfunction "IN*_U1") (pintype "input"))
      (node (ref "D11") (pin "P1") (pinfunction "D_P1") (pintype "input"))
      (node (ref "D11") (pin "T2") (pinfunction "D_T2") (pintype "input"))
    )
    (net (code "87") (name "IOP_1") (class "Default")
      (node (ref "A02") (pin "K2") (pinfunction "P$2_K2") (pintype "bidirectional"))
      (node (ref "C04") (pin "P2") (pinfunction "P2_P2") (pintype "input"))
      (node (ref "C05") (pin "P2") (pinfunction "P2_P2") (pintype "input"))
      (node (ref "D02") (pin "K2") (pinfunction "P$2_K2") (pintype "bidirectional"))
    )
    (net (code "88") (name "IOP_2") (class "Default")
      (node (ref "A02") (pin "M2") (pinfunction "P$2_M2") (pintype "bidirectional"))
      (node (ref "C04") (pin "R2") (pinfunction "R2_R2") (pintype "input"))
      (node (ref "C05") (pin "R2") (pinfunction "R2_R2") (pintype "input"))
      (node (ref "D02") (pin "M2") (pinfunction "P$2_M2") (pintype "bidirectional"))
    )
    (net (code "89") (name "IOP_4") (class "Default")
      (node (ref "A02") (pin "P2") (pinfunction "P$2_P2") (pintype "bidirectional"))
      (node (ref "C04") (pin "S2") (pinfunction "S2_S2") (pintype "input"))
      (node (ref "C05") (pin "S2") (pinfunction "S2_S2") (pintype "input"))
      (node (ref "D02") (pin "P2") (pinfunction "P$2_P2") (pintype "bidirectional"))
    )
    (net (code "90") (name "I{slash}O_B-BRK") (class "Default")
      (node (ref "A05") (pin "P2") (pinfunction "P$2_P2") (pintype "bidirectional"))
      (node (ref "C01") (pin "D1") (pinfunction "IN_D1") (pintype "input"))
      (node (ref "D05") (pin "P2") (pinfunction "P$2_P2") (pintype "bidirectional"))
    )
    (net (code "91") (name "I{slash}O_B-RUN") (class "Default")
      (node (ref "A04") (pin "S2") (pinfunction "P$2_S2") (pintype "bidirectional"))
      (node (ref "C01") (pin "A1") (pinfunction "IN1_A1") (pintype "input"))
      (node (ref "D04") (pin "S2") (pinfunction "P$2_S2") (pintype "bidirectional"))
    )
    (net (code "92") (name "I{slash}O_BAC_00") (class "Default")
      (node (ref "A02") (pin "B1") (pinfunction "P$2_B1") (pintype "bidirectional"))
      (node (ref "C03") (pin "A1") (pinfunction "IN1_A1") (pintype "input"))
      (node (ref "D02") (pin "B1") (pinfunction "P$2_B1") (pintype "bidirectional"))
    )
    (net (code "93") (name "I{slash}O_BAC_01") (class "Default")
      (node (ref "A02") (pin "D1") (pinfunction "P$2_D1") (pintype "bidirectional"))
      (node (ref "C03") (pin "D1") (pinfunction "IN2_D1") (pintype "input"))
      (node (ref "D02") (pin "D1") (pinfunction "P$2_D1") (pintype "bidirectional"))
    )
    (net (code "94") (name "I{slash}O_BAC_02") (class "Default")
      (node (ref "A02") (pin "E1") (pinfunction "P$2_E1") (pintype "bidirectional"))
      (node (ref "C03") (pin "F1") (pinfunction "IN3_F1") (pintype "input"))
      (node (ref "D02") (pin "E1") (pinfunction "P$2_E1") (pintype "bidirectional"))
    )
    (net (code "95") (name "I{slash}O_BAC_03") (class "Default")
      (node (ref "A02") (pin "H1") (pinfunction "P$2_H1") (pintype "bidirectional"))
      (node (ref "C03") (pin "J1") (pinfunction "IN4_J1") (pintype "input"))
      (node (ref "D02") (pin "H1") (pinfunction "P$2_H1") (pintype "bidirectional"))
    )
    (net (code "96") (name "I{slash}O_BAC_04") (class "Default")
      (node (ref "A02") (pin "J1") (pinfunction "P$2_J1") (pintype "bidirectional"))
      (node (ref "C03") (pin "L1") (pinfunction "IN5_L1") (pintype "input"))
      (node (ref "D02") (pin "J1") (pinfunction "P$2_J1") (pintype "bidirectional"))
    )
    (net (code "97") (name "I{slash}O_BAC_05") (class "Default")
      (node (ref "A02") (pin "L1") (pinfunction "P$2_L1") (pintype "bidirectional"))
      (node (ref "C03") (pin "N1") (pinfunction "IN6_N1") (pintype "input"))
      (node (ref "D02") (pin "L1") (pinfunction "P$2_L1") (pintype "bidirectional"))
    )
    (net (code "98") (name "I{slash}O_BAC_06") (class "Default")
      (node (ref "A02") (pin "M1") (pinfunction "P$2_M1") (pintype "bidirectional"))
      (node (ref "C03") (pin "R1") (pinfunction "IN7_R1") (pintype "input"))
      (node (ref "D02") (pin "M1") (pinfunction "P$2_M1") (pintype "bidirectional"))
    )
    (net (code "99") (name "I{slash}O_BAC_07") (class "Default")
      (node (ref "A02") (pin "P1") (pinfunction "P$2_P1") (pintype "bidirectional"))
      (node (ref "C03") (pin "V1") (pinfunction "IN8_V1") (pintype "input"))
      (node (ref "D02") (pin "P1") (pinfunction "P$2_P1") (pintype "bidirectional"))
    )
    (net (code "100") (name "I{slash}O_BAC_08") (class "Default")
      (node (ref "A02") (pin "S1") (pinfunction "P$2_S1") (pintype "bidirectional"))
      (node (ref "C03") (pin "E2") (pinfunction "IN9_E2") (pintype "input"))
      (node (ref "D02") (pin "S1") (pinfunction "P$2_S1") (pintype "bidirectional"))
    )
    (net (code "101") (name "I{slash}O_BAC_09") (class "Default")
      (node (ref "A02") (pin "D2") (pinfunction "P$2_D2") (pintype "bidirectional"))
      (node (ref "C03") (pin "H2") (pinfunction "IN10_H2") (pintype "input"))
      (node (ref "D02") (pin "D2") (pinfunction "P$2_D2") (pintype "bidirectional"))
    )
    (net (code "102") (name "I{slash}O_BAC_10") (class "Default")
      (node (ref "A02") (pin "E2") (pinfunction "P$2_E2") (pintype "bidirectional"))
      (node (ref "C03") (pin "K2") (pinfunction "IN11_K2") (pintype "input"))
      (node (ref "D02") (pin "E2") (pinfunction "P$2_E2") (pintype "bidirectional"))
    )
    (net (code "103") (name "I{slash}O_BAC_11") (class "Default")
      (node (ref "A02") (pin "H2") (pinfunction "P$2_H2") (pintype "bidirectional"))
      (node (ref "C03") (pin "M2") (pinfunction "IN12_M2") (pintype "input"))
      (node (ref "D02") (pin "H2") (pinfunction "P$2_H2") (pintype "bidirectional"))
    )
    (net (code "104") (name "I{slash}O_BMB_00") (class "Default")
      (node (ref "A03") (pin "B1") (pinfunction "P$2_B1") (pintype "bidirectional"))
      (node (ref "C02") (pin "A1") (pinfunction "IN1_A1") (pintype "input"))
      (node (ref "D03") (pin "B1") (pinfunction "P$2_B1") (pintype "bidirectional"))
    )
    (net (code "105") (name "I{slash}O_BMB_01") (class "Default")
      (node (ref "A03") (pin "D1") (pinfunction "P$2_D1") (pintype "bidirectional"))
      (node (ref "C02") (pin "D1") (pinfunction "IN2_D1") (pintype "input"))
      (node (ref "D03") (pin "D1") (pinfunction "P$2_D1") (pintype "bidirectional"))
    )
    (net (code "106") (name "I{slash}O_BMB_02") (class "Default")
      (node (ref "A03") (pin "E1") (pinfunction "P$2_E1") (pintype "bidirectional"))
      (node (ref "C02") (pin "F1") (pinfunction "IN3_F1") (pintype "input"))
      (node (ref "D03") (pin "E1") (pinfunction "P$2_E1") (pintype "bidirectional"))
    )
    (net (code "107") (name "I{slash}O_BMB_03") (class "Default")
      (node (ref "A03") (pin "J1") (pinfunction "P$2_J1") (pintype "bidirectional"))
      (node (ref "C02") (pin "J1") (pinfunction "IN4_J1") (pintype "input"))
      (node (ref "C04") (pin "D2") (pinfunction "D2_D2") (pintype "input"))
      (node (ref "C05") (pin "D2") (pinfunction "D2_D2") (pintype "input"))
      (node (ref "D03") (pin "J1") (pinfunction "P$2_J1") (pintype "bidirectional"))
    )
    (net (code "108") (name "I{slash}O_BMB_04") (class "Default")
      (node (ref "A03") (pin "M1") (pinfunction "P$2_M1") (pintype "bidirectional"))
      (node (ref "C02") (pin "L1") (pinfunction "IN5_L1") (pintype "input"))
      (node (ref "C04") (pin "E2") (pinfunction "E2_E2") (pintype "input"))
      (node (ref "C05") (pin "E2") (pinfunction "E2_E2") (pintype "input"))
      (node (ref "D03") (pin "M1") (pinfunction "P$2_M1") (pintype "bidirectional"))
    )
    (net (code "109") (name "I{slash}O_BMB_05") (class "Default")
      (node (ref "A03") (pin "S1") (pinfunction "P$2_S1") (pintype "bidirectional"))
      (node (ref "C02") (pin "N1") (pinfunction "IN6_N1") (pintype "input"))
      (node (ref "C04") (pin "F2") (pinfunction "F2_F2") (pintype "input"))
      (node (ref "C05") (pin "F2") (pinfunction "F2_F2") (pintype "input"))
      (node (ref "D03") (pin "S1") (pinfunction "P$2_S1") (pintype "bidirectional"))
    )
    (net (code "110") (name "I{slash}O_BMB_06") (class "Default")
      (node (ref "A03") (pin "E2") (pinfunction "P$2_E2") (pintype "bidirectional"))
      (node (ref "C02") (pin "R1") (pinfunction "IN7_R1") (pintype "input"))
      (node (ref "C04") (pin "H2") (pinfunction "H2_H2") (pintype "input"))
      (node (ref "C05") (pin "H2") (pinfunction "H2_H2") (pintype "input"))
      (node (ref "D03") (pin "E2") (pinfunction "P$2_E2") (pintype "bidirectional"))
    )
    (net (code "111") (name "I{slash}O_BMB_07") (class "Default")
      (node (ref "A03") (pin "K2") (pinfunction "P$2_K2") (pintype "bidirectional"))
      (node (ref "C02") (pin "V1") (pinfunction "IN8_V1") (pintype "input"))
      (node (ref "C04") (pin "J2") (pinfunction "J2_J2") (pintype "input"))
      (node (ref "C05") (pin "J2") (pinfunction "J2_J2") (pintype "input"))
      (node (ref "D03") (pin "K2") (pinfunction "P$2_K2") (pintype "bidirectional"))
    )
    (net (code "112") (name "I{slash}O_BMB_08") (class "Default")
      (node (ref "A03") (pin "P2") (pinfunction "P$2_P2") (pintype "bidirectional"))
      (node (ref "C02") (pin "E2") (pinfunction "IN9_E2") (pintype "input"))
      (node (ref "C05") (pin "K2") (pinfunction "K2_K2") (pintype "input"))
      (node (ref "D03") (pin "P2") (pinfunction "P$2_P2") (pintype "bidirectional"))
    )
    (net (code "113") (name "I{slash}O_BMB_09") (class "Default")
      (node (ref "A03") (pin "S2") (pinfunction "P$2_S2") (pintype "bidirectional"))
      (node (ref "C02") (pin "H2") (pinfunction "IN10_H2") (pintype "input"))
      (node (ref "D03") (pin "S2") (pinfunction "P$2_S2") (pintype "bidirectional"))
    )
    (net (code "114") (name "I{slash}O_BMB_10") (class "Default")
      (node (ref "A03") (pin "T2") (pinfunction "P$2_T2") (pintype "bidirectional"))
      (node (ref "C02") (pin "K2") (pinfunction "IN11_K2") (pintype "input"))
      (node (ref "D03") (pin "T2") (pinfunction "P$2_T2") (pintype "bidirectional"))
    )
    (net (code "115") (name "I{slash}O_BMB_11") (class "Default")
      (node (ref "A03") (pin "V2") (pinfunction "P$2_V2") (pintype "bidirectional"))
      (node (ref "C02") (pin "M2") (pinfunction "IN12_M2") (pintype "input"))
      (node (ref "D03") (pin "V2") (pinfunction "P$2_V2") (pintype "bidirectional"))
    )
    (net (code "116") (name "I{slash}O_DATA_IN") (class "Default")
      (node (ref "A05") (pin "M2") (pinfunction "P$2_M2") (pintype "bidirectional"))
      (node (ref "B05") (pin "J2") (pinfunction "E_J2") (pintype "open_collector"))
      (node (ref "D05") (pin "M2") (pinfunction "P$2_M2") (pintype "bidirectional"))
    )
    (net (code "117") (name "I{slash}O_PWR_CLR") (class "Default")
      (node (ref "A02") (pin "V2") (pinfunction "P$2_V2") (pintype "bidirectional"))
      (node (ref "C05") (pin "H1") (pinfunction "IN1_H1") (pintype "input"))
      (node (ref "D02") (pin "V2") (pinfunction "P$2_V2") (pintype "bidirectional"))
    )
    (net (code "118") (name "I{slash}O_TS03") (class "Default")
      (node (ref "A02") (pin "S2") (pinfunction "P$2_S2") (pintype "bidirectional"))
      (node (ref "C04") (pin "H1") (pinfunction "IN1_H1") (pintype "input"))
      (node (ref "D02") (pin "S2") (pinfunction "P$2_S2") (pintype "bidirectional"))
    )
    (net (code "119") (name "I{slash}O_TS04") (class "Default")
      (node (ref "A02") (pin "T2") (pinfunction "P$2_T2") (pintype "bidirectional"))
      (node (ref "D02") (pin "T2") (pinfunction "P$2_T2") (pintype "bidirectional"))
    )
    (net (code "120") (name "I{slash}~{O_0_TO_AC}") (class "Default")
      (node (ref "A04") (pin "P2") (pinfunction "P$2_P2") (pintype "bidirectional"))
      (node (ref "B05") (pin "L1") (pinfunction "E_L1") (pintype "open_collector"))
      (node (ref "D04") (pin "P2") (pinfunction "P$2_P2") (pintype "bidirectional"))
    )
    (net (code "121") (name "I{slash}~{O_1_TO_CA_INH}") (class "Default")
      (node (ref "A06") (pin "M2") (pinfunction "P$2_M2") (pintype "bidirectional"))
      (node (ref "B05") (pin "N2") (pinfunction "D_N2") (pintype "open_collector"))
      (node (ref "D06") (pin "M2") (pinfunction "P$2_M2") (pintype "bidirectional"))
    )
    (net (code "122") (name "I{slash}~{O_ADDR_ACC}") (class "Default")
      (node (ref "A05") (pin "S2") (pinfunction "P$2_S2") (pintype "bidirectional"))
      (node (ref "C02") (pin "U2") (pinfunction "IN15_U2") (pintype "input"))
      (node (ref "D05") (pin "S2") (pinfunction "P$2_S2") (pintype "bidirectional"))
    )
    (net (code "123") (name "I{slash}~{O_BMB_03}") (class "Default")
      (node (ref "A03") (pin "H1") (pinfunction "P$2_H1") (pintype "bidirectional"))
      (node (ref "D03") (pin "H1") (pinfunction "P$2_H1") (pintype "bidirectional"))
    )
    (net (code "124") (name "I{slash}~{O_BMB_04}") (class "Default")
      (node (ref "A03") (pin "L1") (pinfunction "P$2_L1") (pintype "bidirectional"))
      (node (ref "D03") (pin "L1") (pinfunction "P$2_L1") (pintype "bidirectional"))
    )
    (net (code "125") (name "I{slash}~{O_BMB_05}") (class "Default")
      (node (ref "A03") (pin "P1") (pinfunction "P$2_P1") (pintype "bidirectional"))
      (node (ref "D03") (pin "P1") (pinfunction "P$2_P1") (pintype "bidirectional"))
    )
    (net (code "126") (name "I{slash}~{O_BMB_06}") (class "Default")
      (node (ref "A03") (pin "D2") (pinfunction "P$2_D2") (pintype "bidirectional"))
      (node (ref "D03") (pin "D2") (pinfunction "P$2_D2") (pintype "bidirectional"))
    )
    (net (code "127") (name "I{slash}~{O_BMB_07}") (class "Default")
      (node (ref "A03") (pin "H2") (pinfunction "P$2_H2") (pintype "bidirectional"))
      (node (ref "D03") (pin "H2") (pinfunction "P$2_H2") (pintype "bidirectional"))
    )
    (net (code "128") (name "I{slash}~{O_BMB_08}") (class "Default")
      (node (ref "A03") (pin "M2") (pinfunction "P$2_M2") (pintype "bidirectional"))
      (node (ref "C04") (pin "K2") (pinfunction "K2_K2") (pintype "input"))
      (node (ref "D03") (pin "M2") (pinfunction "P$2_M2") (pintype "bidirectional"))
    )
    (net (code "129") (name "I{slash}~{O_BRK_RQ}") (class "Default")
      (node (ref "A05") (pin "K2") (pinfunction "P$2_K2") (pintype "bidirectional"))
      (node (ref "B05") (pin "D1") (pinfunction "D_D1") (pintype "open_collector"))
      (node (ref "D05") (pin "K2") (pinfunction "P$2_K2") (pintype "bidirectional"))
    )
    (net (code "130") (name "I{slash}~{O_BWC0}") (class "Default")
      (node (ref "A06") (pin "P2") (pinfunction "P$2_P2") (pintype "bidirectional"))
      (node (ref "C01") (pin "F1") (pinfunction "IN_F1") (pintype "input"))
      (node (ref "D06") (pin "P2") (pinfunction "P$2_P2") (pintype "bidirectional"))
    )
    (net (code "131") (name "I{slash}~{O_INT_RQ}") (class "Default")
      (node (ref "A04") (pin "M2") (pinfunction "P$2_M2") (pintype "bidirectional"))
      (node (ref "B05") (pin "E1") (pinfunction "E_E1") (pintype "open_collector"))
      (node (ref "D04") (pin "M2") (pinfunction "P$2_M2") (pintype "bidirectional"))
    )
    (net (code "132") (name "I{slash}~{O_SKP_RQ}") (class "Default")
      (node (ref "A04") (pin "K2") (pinfunction "P$2_K2") (pintype "bidirectional"))
      (node (ref "B05") (pin "K1") (pinfunction "D_K1") (pintype "open_collector"))
      (node (ref "D04") (pin "K2") (pinfunction "P$2_K2") (pintype "bidirectional"))
    )
    (net (code "133") (name "LDMF") (class "Default")
      (node (ref "C05") (pin "F1") (pinfunction "F1_F1") (pintype "output"))
      (node (ref "D11") (pin "B1") (pinfunction "C_B1") (pintype "input"))
      (node (ref "D11") (pin "D2") (pinfunction "C_D2") (pintype "input"))
      (node (ref "D11") (pin "H1") (pinfunction "C_H1") (pintype "input"))
    )
    (net (code "134") (name "LPB_00") (class "Default")
      (node (ref "A25") (pin "T2") (pinfunction "P$2_T2") (pintype "bidirectional"))
      (node (ref "C08") (pin "D1") (pinfunction "IN2B_D1") (pintype "input"))
      (node (ref "D08") (pin "E1") (pinfunction "E1_E1") (pintype "output"))
    )
    (net (code "135") (name "LPB_01") (class "Default")
      (node (ref "A25") (pin "U2") (pinfunction "P$2_U2") (pintype "bidirectional"))
      (node (ref "C08") (pin "K1") (pinfunction "IN2B_K1") (pintype "input"))
      (node (ref "D08") (pin "L1") (pinfunction "L1_L1") (pintype "output"))
    )
    (net (code "136") (name "LPB_02") (class "Default")
      (node (ref "A25") (pin "V2") (pinfunction "P$2_V2") (pintype "bidirectional"))
      (node (ref "C08") (pin "R1") (pinfunction "IN2B_R1") (pintype "input"))
      (node (ref "D08") (pin "S1") (pinfunction "S1_S1") (pintype "output"))
    )
    (net (code "137") (name "LPB_03") (class "Default")
      (node (ref "A26") (pin "A2") (pinfunction "P$2_A2") (pintype "bidirectional"))
      (node (ref "C08") (pin "H2") (pinfunction "IN2B_H2") (pintype "input"))
      (node (ref "D08") (pin "H2") (pinfunction "H2_H2") (pintype "output"))
    )
    (net (code "138") (name "LPB_04") (class "Default")
      (node (ref "A26") (pin "B2") (pinfunction "P$2_B2") (pintype "bidirectional"))
      (node (ref "C08") (pin "N2") (pinfunction "IN2B_N2") (pintype "input"))
      (node (ref "D08") (pin "P2") (pinfunction "P2_P2") (pintype "output"))
    )
    (net (code "139") (name "LPB_05") (class "Default")
      (node (ref "A26") (pin "C2") (pinfunction "P$2_C2") (pintype "bidirectional"))
      (node (ref "C08") (pin "U2") (pinfunction "IN2B_U2") (pintype "input"))
      (node (ref "D08") (pin "V2") (pinfunction "V2_V2") (pintype "output"))
    )
    (net (code "140") (name "LPB_NOT_EQ_1") (class "Default")
      (node (ref "A10") (pin "M1") (pinfunction "IN2_M1") (pintype "input"))
      (node (ref "D10") (pin "V2") (pinfunction "OUT_V2") (pintype "output"))
    )
    (net (code "141") (name "LPB_TO_DTB") (class "Default")
      (node (ref "A11") (pin "T2") (pinfunction "OUT_T2") (pintype "output"))
      (node (ref "C08") (pin "C1") (pinfunction "IN2A_C1") (pintype "input"))
      (node (ref "C08") (pin "F2") (pinfunction "IN2A_F2") (pintype "input"))
      (node (ref "C08") (pin "J1") (pinfunction "IN2A_J1") (pintype "input"))
      (node (ref "C08") (pin "M2") (pinfunction "IN2A_M2") (pintype "input"))
      (node (ref "C08") (pin "P1") (pinfunction "IN2A_P1") (pintype "input"))
      (node (ref "C08") (pin "T2") (pinfunction "IN2A_T2") (pintype "input"))
    )
    (net (code "142") (name "MC00") (class "Default")
      (node (ref "A26") (pin "S1") (pinfunction "P$2_S1") (pintype "bidirectional"))
      (node (ref "B13") (pin "E1") (pinfunction "1_E1") (pintype "output"))
      (node (ref "B13") (pin "E2") (pinfunction "D_E2") (pintype "input"))
      (node (ref "D10") (pin "D2") (pinfunction "IN5_D2") (pintype "input"))
    )
    (net (code "143") (name "MC01") (class "Default")
      (node (ref "A08") (pin "L2") (pinfunction "C_L2") (pintype "input"))
      (node (ref "A26") (pin "T1") (pinfunction "P$2_T1") (pintype "bidirectional"))
      (node (ref "B13") (pin "H2") (pinfunction "1_H2") (pintype "output"))
      (node (ref "B13") (pin "J1") (pinfunction "D_J1") (pintype "input"))
      (node (ref "C11") (pin "E1") (pinfunction "IN2_E1") (pintype "input"))
    )
    (net (code "144") (name "MC02") (class "Default")
      (node (ref "A26") (pin "U1") (pinfunction "P$2_U1") (pintype "bidirectional"))
      (node (ref "B11") (pin "U2") (pinfunction "IN2_U2") (pintype "input"))
      (node (ref "B13") (pin "L1") (pinfunction "1_L1") (pintype "output"))
      (node (ref "D12") (pin "D2") (pinfunction "IN1_D2") (pintype "input"))
      (node (ref "D12") (pin "E2") (pinfunction "IN2_E2") (pintype "input"))
    )
    (net (code "145") (name "MF00") (class "Default")
      (node (ref "A25") (pin "V1") (pinfunction "P$2_V1") (pintype "bidirectional"))
      (node (ref "D11") (pin "E1") (pinfunction "1_E1") (pintype "output"))
    )
    (net (code "146") (name "MF01") (class "Default")
      (node (ref "A26") (pin "A1") (pinfunction "P$2_A1") (pintype "bidirectional"))
      (node (ref "D11") (pin "H2") (pinfunction "1_H2") (pintype "output"))
    )
    (net (code "147") (name "MF02") (class "Default")
      (node (ref "A26") (pin "B1") (pinfunction "P$2_B1") (pintype "bidirectional"))
      (node (ref "D11") (pin "L1") (pinfunction "1_L1") (pintype "output"))
    )
    (net (code "148") (name "MKT") (class "Default")
      (node (ref "A26") (pin "H2") (pinfunction "P$2_H2") (pintype "bidirectional"))
      (node (ref "B12") (pin "S2") (pinfunction "IN2_S2") (pintype "input"))
      (node (ref "B13") (pin "V2") (pinfunction "1_V2") (pintype "output"))
      (node (ref "B15") (pin "L1") (pinfunction "IN1_L1") (pintype "input"))
      (node (ref "C15") (pin "L2") (pinfunction "IN1_L2") (pintype "input"))
    )
    (net (code "149") (name "MKTK") (class "Default")
      (node (ref "A08") (pin "R2") (pinfunction "0_R2") (pintype "output"))
      (node (ref "A25") (pin "P1") (pinfunction "P$2_P1") (pintype "bidirectional"))
    )
    (net (code "150") (name "MK_BLK_END") (class "Default")
      (node (ref "A09") (pin "T2") (pinfunction "IN3_T2") (pintype "input"))
      (node (ref "CD18") (pin "BU1") (pinfunction "BU1_BU1") (pintype "output"))
    )
    (net (code "151") (name "MK_BLK_MK") (class "Default")
      (node (ref "CD18") (pin "AE2") (pinfunction "AE2_AE2") (pintype "output"))
      (node (ref "D10") (pin "A1") (pinfunction "IN1_A1") (pintype "input"))
      (node (ref "D10") (pin "B1") (pinfunction "IN2_B1") (pintype "input"))
    )
    (net (code "152") (name "MK_BLK_START") (class "Default")
      (node (ref "CD18") (pin "AJ2") (pinfunction "AJ2_AJ2") (pintype "output"))
    )
    (net (code "153") (name "MK_BLK_SYNC") (class "Default")
      (node (ref "CD18") (pin "BS2") (pinfunction "BS2_BS2") (pintype "output"))
    )
    (net (code "154") (name "MK_DATA") (class "Default")
      (node (ref "CD18") (pin "BP2") (pinfunction "BP2_BP2") (pintype "output"))
    )
    (net (code "155") (name "MK_DATA_SYNC") (class "Default")
      (node (ref "CD18") (pin "AH1") (pinfunction "AH1_AH1") (pintype "output"))
    )
    (net (code "156") (name "MK_END") (class "Default")
      (node (ref "A08") (pin "C1") (pinfunction "D_C1") (pintype "input"))
      (node (ref "CD18") (pin "AF2") (pinfunction "AF2_AF2") (pintype "output"))
    )
    (net (code "157") (name "MOVE") (class "Default")
      (node (ref "D07") (pin "D2") (pinfunction "O0_D2") (pintype "output"))
    )
    (net (code "158") (name "MR00") (class "Default")
      (node (ref "A25") (pin "D1") (pinfunction "P$2_D1") (pintype "bidirectional"))
      (node (ref "B07") (pin "P2") (pinfunction "P2_P2") (pintype "output"))
      (node (ref "B14") (pin "M2") (pinfunction "D_M2") (pintype "input"))
    )
    (net (code "159") (name "MR01") (class "Default")
      (node (ref "A25") (pin "E1") (pinfunction "P$2_E1") (pintype "bidirectional"))
      (node (ref "C07") (pin "P2") (pinfunction "P2_P2") (pintype "output"))
      (node (ref "C12") (pin "B1") (pinfunction "IN2_B1") (pintype "input"))
    )
    (net (code "160") (name "NC") (class "Default")
      (node (ref "A04") (pin "T2") (pinfunction "P$2_T2") (pintype "bidirectional"))
      (node (ref "A04") (pin "V2") (pinfunction "P$2_V2") (pintype "bidirectional"))
      (node (ref "A05") (pin "E2") (pinfunction "P$2_E2") (pintype "bidirectional"))
      (node (ref "A05") (pin "H2") (pinfunction "P$2_H2") (pintype "bidirectional"))
      (node (ref "A05") (pin "T2") (pinfunction "P$2_T2") (pintype "bidirectional"))
      (node (ref "A05") (pin "V2") (pinfunction "P$2_V2") (pintype "bidirectional"))
      (node (ref "A18") (pin "H2") (pinfunction "H2_H2") (pintype "input"))
      (node (ref "A18") (pin "L2") (pinfunction "L2_L2") (pintype "input"))
      (node (ref "A18") (pin "M2") (pinfunction "M2_M2") (pintype "input"))
      (node (ref "A20") (pin "H2") (pinfunction "H2_H2") (pintype "input"))
      (node (ref "A20") (pin "L2") (pinfunction "L2_L2") (pintype "input"))
      (node (ref "A20") (pin "M2") (pinfunction "M2_M2") (pintype "input"))
      (node (ref "A21") (pin "H2") (pinfunction "H2_H2") (pintype "input"))
      (node (ref "A21") (pin "L2") (pinfunction "L2_L2") (pintype "input"))
      (node (ref "A21") (pin "M2") (pinfunction "M2_M2") (pintype "input"))
      (node (ref "A24") (pin "A2") (pinfunction "P$2_A2") (pintype "bidirectional"))
      (node (ref "A24") (pin "B2") (pinfunction "P$2_B2") (pintype "bidirectional"))
      (node (ref "A24") (pin "J2") (pinfunction "P$2_J2") (pintype "bidirectional"))
      (node (ref "A26") (pin "D1") (pinfunction "P$2_D1") (pintype "bidirectional"))
      (node (ref "AB01") (pin "BN1") (pinfunction "BN1_BN1") (pintype "input"))
      (node (ref "AB01") (pin "BP1") (pinfunction "BP1_BP1") (pintype "input"))
      (node (ref "B05") (pin "L2") (pinfunction "B_L2") (pintype "input"))
      (node (ref "B18") (pin "H2") (pinfunction "H2_H2") (pintype "input"))
      (node (ref "B18") (pin "L2") (pinfunction "L2_L2") (pintype "input"))
      (node (ref "B18") (pin "M2") (pinfunction "M2_M2") (pintype "input"))
      (node (ref "B20") (pin "H2") (pinfunction "H2_H2") (pintype "input"))
      (node (ref "B20") (pin "L2") (pinfunction "L2_L2") (pintype "input"))
      (node (ref "B20") (pin "M2") (pinfunction "M2_M2") (pintype "input"))
      (node (ref "B22") (pin "R2") (pinfunction "A_R2") (pintype "input"))
      (node (ref "C02") (pin "P2") (pinfunction "IN13_P2") (pintype "input"))
      (node (ref "C02") (pin "S2") (pinfunction "IN14_S2") (pintype "input"))
      (node (ref "C03") (pin "P2") (pinfunction "IN13_P2") (pintype "input"))
      (node (ref "C03") (pin "S2") (pinfunction "IN14_S2") (pintype "input"))
      (node (ref "C03") (pin "U2") (pinfunction "IN15_U2") (pintype "input"))
      (node (ref "C07") (pin "N1") (pinfunction "N1_N1") (pintype "input"))
      (node (ref "C07") (pin "P1") (pinfunction "P1_P1") (pintype "input"))
      (node (ref "C07") (pin "R1") (pinfunction "R1_R1") (pintype "input"))
      (node (ref "C07") (pin "S2") (pinfunction "S2_S2") (pintype "input"))
      (node (ref "C07") (pin "T2") (pinfunction "T2_T2") (pintype "input"))
      (node (ref "C07") (pin "U2") (pinfunction "U2_U2") (pintype "input"))
      (node (ref "D04") (pin "T2") (pinfunction "P$2_T2") (pintype "bidirectional"))
      (node (ref "D04") (pin "V2") (pinfunction "P$2_V2") (pintype "bidirectional"))
      (node (ref "D05") (pin "E2") (pinfunction "P$2_E2") (pintype "bidirectional"))
      (node (ref "D05") (pin "H2") (pinfunction "P$2_H2") (pintype "bidirectional"))
      (node (ref "D05") (pin "T2") (pinfunction "P$2_T2") (pintype "bidirectional"))
      (node (ref "D05") (pin "V2") (pinfunction "P$2_V2") (pintype "bidirectional"))
      (node (ref "D14") (pin "B1") (pinfunction "V2_B1") (pintype "passive"))
      (node (ref "D14") (pin "D1") (pinfunction "U2_D1") (pintype "passive"))
      (node (ref "D14") (pin "E1") (pinfunction "S2_E1") (pintype "passive"))
      (node (ref "D14") (pin "F1") (pinfunction "R2_F1") (pintype "passive"))
      (node (ref "D14") (pin "J1") (pinfunction "N2_J1") (pintype "passive"))
      (node (ref "D14") (pin "N2") (pinfunction "N2_N2") (pintype "passive"))
      (node (ref "D14") (pin "P2") (pinfunction "P2_P2") (pintype "passive"))
      (node (ref "D14") (pin "R2") (pinfunction "R2_R2") (pintype "passive"))
      (node (ref "D14") (pin "S2") (pinfunction "S2_S2") (pintype "passive"))
      (node (ref "D14") (pin "U2") (pinfunction "U2_U2") (pintype "passive"))
      (node (ref "D15") (pin "M2") (pinfunction "M2_M2") (pintype "passive"))
      (node (ref "D15") (pin "P2") (pinfunction "P2_P2") (pintype "passive"))
      (node (ref "D15") (pin "R2") (pinfunction "R2_R2") (pintype "passive"))
      (node (ref "D15") (pin "T2") (pinfunction "T2_T2") (pintype "passive"))
    )
    (net (code "161") (name "Net-(A08B-D)") (class "Default")
      (node (ref "A08") (pin "E2") (pinfunction "D_E2") (pintype "input"))
      (node (ref "A09") (pin "L1") (pinfunction "OUT_L1") (pintype "output"))
    )
    (net (code "162") (name "Net-(A08C-S)") (class "Default")
      (node (ref "A08") (pin "K1") (pinfunction "S_K1") (pintype "input"))
      (node (ref "A11") (pin "E1") (pinfunction "OUT_E1") (pintype "output"))
    )
    (net (code "163") (name "Net-(A08F-D)") (class "Default")
      (node (ref "A08") (pin "M2") (pinfunction "D_M2") (pintype "input"))
      (node (ref "A09") (pin "J2") (pinfunction "OUT_J2") (pintype "output"))
    )
    (net (code "164") (name "Net-(A08G-C)") (class "Default")
      (node (ref "A08") (pin "N1") (pinfunction "C_N1") (pintype "input"))
      (node (ref "A11") (pin "D2") (pinfunction "OUT_D2") (pintype "output"))
    )
    (net (code "165") (name "Net-(A08G-D)") (class "Default")
      (node (ref "A08") (pin "P1") (pinfunction "D_P1") (pintype "input"))
      (node (ref "A10") (pin "N1") (pinfunction "OUT_N1") (pintype "output"))
    )
    (net (code "166") (name "Net-(A08H-S)") (class "Default")
      (node (ref "A08") (pin "U2") (pinfunction "S_U2") (pintype "input"))
      (node (ref "B10") (pin "S1") (pinfunction "OUT_S1") (pintype "output"))
    )
    (net (code "167") (name "Net-(A09A-OUT)") (class "Default")
      (node (ref "A09") (pin "E1") (pinfunction "OUT_E1") (pintype "output"))
      (node (ref "A11") (pin "A1") (pinfunction "IN_A1") (pintype "input"))
    )
    (net (code "168") (name "Net-(A09C-IN1)") (class "Default")
      (node (ref "A09") (pin "F1") (pinfunction "IN1_F1") (pintype "input"))
      (node (ref "C10") (pin "P2") (pinfunction "OUT_P2") (pintype "output"))
    )
    (net (code "169") (name "Net-(A09C-IN3)") (class "Default")
      (node (ref "A09") (pin "J1") (pinfunction "IN3_J1") (pintype "input"))
      (node (ref "A10") (pin "K1") (pinfunction "OUT_K1") (pintype "output"))
    )
    (net (code "170") (name "Net-(A09C-IN4)") (class "Default")
      (node (ref "A09") (pin "K1") (pinfunction "IN4_K1") (pintype "input"))
      (node (ref "B21") (pin "U2") (pinfunction "OUT_U2") (pintype "output"))
    )
    (net (code "171") (name "Net-(A09D-OUT)") (class "Default")
      (node (ref "A09") (pin "S1") (pinfunction "OUT_S1") (pintype "output"))
      (node (ref "A10") (pin "U2") (pinfunction "IN2_U2") (pintype "input"))
    )
    (net (code "172") (name "Net-(A09E-IN4)") (class "Default")
      (node (ref "A09") (pin "H2") (pinfunction "IN4_H2") (pintype "input"))
      (node (ref "A11") (pin "B1") (pinfunction "OUT_B1") (pintype "output"))
    )
    (net (code "173") (name "Net-(A09F-OUT)") (class "Default")
      (node (ref "A09") (pin "P2") (pinfunction "OUT_P2") (pintype "output"))
      (node (ref "A11") (pin "F1") (pinfunction "IN_F1") (pintype "input"))
    )
    (net (code "174") (name "Net-(A09G-IN4)") (class "Default")
      (node (ref "A09") (pin "U2") (pinfunction "IN4_U2") (pintype "input"))
      (node (ref "C17") (pin "R2") (pinfunction "OUT_R2") (pintype "output"))
    )
    (net (code "175") (name "Net-(A09G-OUT)") (class "Default")
      (node (ref "A09") (pin "V2") (pinfunction "OUT_V2") (pintype "output"))
      (node (ref "A11") (pin "S2") (pinfunction "IN_S2") (pintype "input"))
    )
    (net (code "176") (name "Net-(A10A-IN2)") (class "Default")
      (node (ref "A10") (pin "B1") (pinfunction "IN2_B1") (pintype "input"))
      (node (ref "A10") (pin "F1") (pinfunction "OUT_F1") (pintype "output"))
      (node (ref "B15") (pin "P2") (pinfunction "IN1_P2") (pintype "input"))
    )
    (net (code "177") (name "Net-(A10A-OUT)") (class "Default")
      (node (ref "A10") (pin "C1") (pinfunction "OUT_C1") (pintype "output"))
      (node (ref "A10") (pin "D1") (pinfunction "IN1_D1") (pintype "input"))
    )
    (net (code "178") (name "Net-(A10B-IN1)") (class "Default")
      (node (ref "A10") (pin "S2") (pinfunction "OUT_S2") (pintype "output"))
      (node (ref "A10") (pin "T2") (pinfunction "IN1_T2") (pintype "input"))
    )
    (net (code "179") (name "Net-(A10B-OUT)") (class "Default")
      (node (ref "A10") (pin "V2") (pinfunction "OUT_V2") (pintype "output"))
      (node (ref "A11") (pin "D1") (pinfunction "IN_D1") (pintype "input"))
    )
    (net (code "180") (name "Net-(A10H-OUT)") (class "Default")
      (node (ref "A10") (pin "F2") (pinfunction "OUT_F2") (pintype "output"))
      (node (ref "A10") (pin "J2") (pinfunction "IN2_J2") (pintype "input"))
    )
    (net (code "181") (name "Net-(A10M-OUT)") (class "Default")
      (node (ref "A10") (pin "S1") (pinfunction "OUT_S1") (pintype "output"))
      (node (ref "A11") (pin "C1") (pinfunction "IN_C1") (pintype "input"))
    )
    (net (code "182") (name "Net-(A11D-IN)") (class "Default")
      (node (ref "A11") (pin "R1") (pinfunction "IN_R1") (pintype "input"))
      (node (ref "B11") (pin "S2") (pinfunction "OUT_S2") (pintype "output"))
    )
    (net (code "183") (name "Net-(A11E-IN)") (class "Default")
      (node (ref "A11") (pin "P2") (pinfunction "IN_P2") (pintype "input"))
      (node (ref "A14") (pin "F2") (pinfunction "F2_F2") (pintype "output"))
    )
    (net (code "184") (name "Net-(A11F-IN)") (class "Default")
      (node (ref "A11") (pin "V1") (pinfunction "IN_V1") (pintype "input"))
      (node (ref "B08") (pin "V2") (pinfunction "OUT_V2") (pintype "output"))
    )
    (net (code "185") (name "Net-(A11H-IN)") (class "Default")
      (node (ref "A11") (pin "U2") (pinfunction "IN_U2") (pintype "input"))
      (node (ref "A14") (pin "T2") (pinfunction "F2_T2") (pintype "output"))
    )
    (net (code "186") (name "Net-(A11K-OUT)") (class "Default")
      (node (ref "A11") (pin "H1") (pinfunction "OUT_H1") (pintype "output"))
      (node (ref "A12") (pin "B1") (pinfunction "IN2_B1") (pintype "input"))
      (node (ref "A12") (pin "D1") (pinfunction "IN1_D1") (pintype "input"))
    )
    (net (code "187") (name "Net-(A12B-IN1)") (class "Default")
      (node (ref "A12") (pin "N2") (pinfunction "OUT_N2") (pintype "output"))
      (node (ref "A12") (pin "T2") (pinfunction "IN1_T2") (pintype "input"))
    )
    (net (code "188") (name "Net-(A12B-IN2)") (class "Default")
      (node (ref "A12") (pin "S2") (pinfunction "OUT_S2") (pintype "output"))
      (node (ref "A12") (pin "U2") (pinfunction "IN2_U2") (pintype "input"))
    )
    (net (code "189") (name "Net-(A12H-OUT)") (class "Default")
      (node (ref "A12") (pin "F2") (pinfunction "OUT_F2") (pintype "output"))
      (node (ref "B10") (pin "A1") (pinfunction "IN1_A1") (pintype "input"))
      (node (ref "B10") (pin "B1") (pinfunction "IN2_B1") (pintype "input"))
    )
    (net (code "190") (name "Net-(A12I-IN2)") (class "Default")
      (node (ref "A12") (pin "J1") (pinfunction "IN2_J1") (pintype "input"))
      (node (ref "A12") (pin "N1") (pinfunction "OUT_N1") (pintype "output"))
      (node (ref "A12") (pin "P1") (pinfunction "IN1_P1") (pintype "input"))
    )
    (net (code "191") (name "Net-(A12J-OUT)") (class "Default")
      (node (ref "A12") (pin "K2") (pinfunction "OUT_K2") (pintype "output"))
      (node (ref "B10") (pin "C1") (pinfunction "IN3_C1") (pintype "input"))
      (node (ref "B10") (pin "D1") (pinfunction "IN4_D1") (pintype "input"))
    )
    (net (code "192") (name "Net-(A14-PadD2)") (class "Default")
      (node (ref "A14") (pin "D2") (pinfunction "D2_D2") (pintype "passive"))
      (node (ref "A14") (pin "E2") (pinfunction "E2_E2") (pintype "passive"))
    )
    (net (code "193") (name "Net-(A14-PadH1)") (class "Default")
      (node (ref "A14") (pin "H1") (pinfunction "H1_H1") (pintype "passive"))
      (node (ref "A14") (pin "L2") (pinfunction "L2_L2") (pintype "passive"))
    )
    (net (code "194") (name "Net-(A14B-D2)") (class "Default")
      (node (ref "A14") (pin "R2") (pinfunction "E2_R2") (pintype "passive"))
      (node (ref "A14") (pin "V2") (pinfunction "D2_V2") (pintype "passive"))
    )
    (net (code "195") (name "Net-(A14B-H1)") (class "Default")
      (node (ref "A14") (pin "S1") (pinfunction "H1_S1") (pintype "passive"))
      (node (ref "A14") (pin "S2") (pinfunction "L2_S2") (pintype "passive"))
    )
    (net (code "196") (name "Net-(A14B-H2)") (class "Default")
      (node (ref "A14") (pin "M2") (pinfunction "H2_M2") (pintype "input"))
      (node (ref "A14") (pin "N2") (pinfunction "J2_N2") (pintype "input"))
      (node (ref "A14") (pin "P2") (pinfunction "K2_P2") (pintype "input"))
      (node (ref "B15") (pin "F2") (pinfunction "OUT_F2") (pintype "output"))
    )
    (net (code "197") (name "Net-(A15A-IN3)") (class "Default")
      (node (ref "A15") (pin "C1") (pinfunction "IN3_C1") (pintype "input"))
      (node (ref "A15") (pin "D1") (pinfunction "IN4_D1") (pintype "input"))
      (node (ref "C17") (pin "D2") (pinfunction "OUT_D2") (pintype "output"))
    )
    (net (code "198") (name "Net-(A15D-IN1)") (class "Default")
      (node (ref "A15") (pin "D2") (pinfunction "IN1_D2") (pintype "input"))
      (node (ref "A15") (pin "E2") (pinfunction "IN2_E2") (pintype "input"))
      (node (ref "C17") (pin "F2") (pinfunction "OUT_F2") (pintype "output"))
    )
    (net (code "199") (name "Net-(A16-PadD2)") (class "Default")
      (node (ref "A16") (pin "D2") (pinfunction "D2_D2") (pintype "passive"))
      (node (ref "A16") (pin "E2") (pinfunction "E2_E2") (pintype "passive"))
    )
    (net (code "200") (name "Net-(A16B-D2)") (class "Default")
      (node (ref "A16") (pin "R2") (pinfunction "E2_R2") (pintype "passive"))
      (node (ref "A16") (pin "S2") (pinfunction "D2_S2") (pintype "passive"))
    )
    (net (code "201") (name "Net-(AB19A-P$2)") (class "Default")
      (node (ref "A18") (pin "D2") (pinfunction "D2_D2") (pintype "input"))
      (node (ref "A18") (pin "J2") (pinfunction "J2_J2") (pintype "output"))
      (node (ref "AB19") (pin "AF2") (pinfunction "P$2_AF2") (pintype "bidirectional"))
    )
    (net (code "202") (name "Net-(AB19C-P$2)") (class "Default")
      (node (ref "AB19") (pin "BH2") (pinfunction "P$2_BH2") (pintype "bidirectional"))
      (node (ref "B20") (pin "D2") (pinfunction "D2_D2") (pintype "input"))
      (node (ref "B20") (pin "J2") (pinfunction "J2_J2") (pintype "output"))
    )
    (net (code "203") (name "Net-(AB19D-P$2)") (class "Default")
      (node (ref "AB19") (pin "BJ2") (pinfunction "P$2_BJ2") (pintype "bidirectional"))
      (node (ref "B20") (pin "E2") (pinfunction "E2_E2") (pintype "input"))
      (node (ref "B20") (pin "K2") (pinfunction "K2_K2") (pintype "output"))
    )
    (net (code "204") (name "Net-(AB19F-P$2)") (class "Default")
      (node (ref "A21") (pin "D2") (pinfunction "D2_D2") (pintype "input"))
      (node (ref "A21") (pin "J2") (pinfunction "J2_J2") (pintype "output"))
      (node (ref "AB19") (pin "BN2") (pinfunction "P$2_BN2") (pintype "bidirectional"))
    )
    (net (code "205") (name "Net-(AB19G-P$2)") (class "Default")
      (node (ref "A21") (pin "E2") (pinfunction "E2_E2") (pintype "input"))
      (node (ref "A21") (pin "K2") (pinfunction "K2_K2") (pintype "output"))
      (node (ref "AB19") (pin "BP2") (pinfunction "P$2_BP2") (pintype "bidirectional"))
    )
    (net (code "206") (name "Net-(AB19L-P$2)") (class "Default")
      (node (ref "A18") (pin "E2") (pinfunction "E2_E2") (pintype "input"))
      (node (ref "A18") (pin "K2") (pinfunction "K2_K2") (pintype "output"))
      (node (ref "AB19") (pin "AH2") (pinfunction "P$2_AH2") (pintype "bidirectional"))
    )
    (net (code "207") (name "Net-(AB19P-P$2)") (class "Default")
      (node (ref "AB19") (pin "AN2") (pinfunction "P$2_AN2") (pintype "bidirectional"))
      (node (ref "B18") (pin "D2") (pinfunction "D2_D2") (pintype "input"))
      (node (ref "B18") (pin "J2") (pinfunction "J2_J2") (pintype "output"))
    )
    (net (code "208") (name "Net-(AB19Q-P$2)") (class "Default")
      (node (ref "AB19") (pin "AP2") (pinfunction "P$2_AP2") (pintype "bidirectional"))
      (node (ref "B18") (pin "E2") (pinfunction "E2_E2") (pintype "input"))
      (node (ref "B18") (pin "K2") (pinfunction "K2_K2") (pintype "output"))
    )
    (net (code "209") (name "Net-(AB19T-P$2)") (class "Default")
      (node (ref "A20") (pin "D2") (pinfunction "D2_D2") (pintype "input"))
      (node (ref "A20") (pin "J2") (pinfunction "J2_J2") (pintype "output"))
      (node (ref "AB19") (pin "AV2") (pinfunction "P$2_AV2") (pintype "bidirectional"))
    )
    (net (code "210") (name "Net-(AB19U-P$2)") (class "Default")
      (node (ref "A20") (pin "E2") (pinfunction "E2_E2") (pintype "input"))
      (node (ref "A20") (pin "K2") (pinfunction "K2_K2") (pintype "output"))
      (node (ref "AB19") (pin "BD2") (pinfunction "P$2_BD2") (pintype "bidirectional"))
    )
    (net (code "211") (name "Net-(B06G-IN)") (class "Default")
      (node (ref "B06") (pin "S2") (pinfunction "IN_S2") (pintype "input"))
      (node (ref "B08") (pin "S2") (pinfunction "OUT_S2") (pintype "output"))
    )
    (net (code "212") (name "Net-(B08A-OUT)") (class "Default")
      (node (ref "B08") (pin "C1") (pinfunction "OUT_C1") (pintype "output"))
      (node (ref "B09") (pin "D1") (pinfunction "S_D1") (pintype "input"))
    )
    (net (code "213") (name "Net-(B08G-OUT)") (class "Default")
      (node (ref "B08") (pin "F1") (pinfunction "OUT_F1") (pintype "output"))
      (node (ref "B09") (pin "U2") (pinfunction "S_U2") (pintype "input"))
    )
    (net (code "214") (name "Net-(B08H-OUT)") (class "Default")
      (node (ref "B08") (pin "F2") (pinfunction "OUT_F2") (pintype "output"))
      (node (ref "B09") (pin "K1") (pinfunction "S_K1") (pintype "input"))
    )
    (net (code "215") (name "Net-(B08I-OUT)") (class "Default")
      (node (ref "B08") (pin "K1") (pinfunction "OUT_K1") (pintype "output"))
      (node (ref "B09") (pin "F2") (pinfunction "S_F2") (pintype "input"))
    )
    (net (code "216") (name "Net-(B08K-OUT)") (class "Default")
      (node (ref "B08") (pin "N1") (pinfunction "OUT_N1") (pintype "output"))
      (node (ref "B09") (pin "N2") (pinfunction "S_N2") (pintype "input"))
    )
    (net (code "217") (name "Net-(B08M-OUT)") (class "Default")
      (node (ref "B08") (pin "S1") (pinfunction "OUT_S1") (pintype "output"))
      (node (ref "B09") (pin "R1") (pinfunction "S_R1") (pintype "input"))
    )
    (net (code "218") (name "Net-(B10B-IN1)") (class "Default")
      (node (ref "B10") (pin "F1") (pinfunction "IN1_F1") (pintype "input"))
      (node (ref "B11") (pin "J1") (pinfunction "OUT_J1") (pintype "output"))
    )
    (net (code "219") (name "Net-(B10B-IN4)") (class "Default")
      (node (ref "B10") (pin "K1") (pinfunction "IN4_K1") (pintype "input"))
      (node (ref "C17") (pin "H1") (pinfunction "OUT_H1") (pintype "output"))
    )
    (net (code "220") (name "Net-(B11A-OUT)") (class "Default")
      (node (ref "B11") (pin "D1") (pinfunction "OUT_D1") (pintype "output"))
      (node (ref "B11") (pin "F2") (pinfunction "IN3_F2") (pintype "input"))
    )
    (net (code "221") (name "Net-(B11C-IN1)") (class "Default")
      (node (ref "B11") (pin "E1") (pinfunction "IN1_E1") (pintype "input"))
      (node (ref "B11") (pin "U1") (pinfunction "OUT_U1") (pintype "output"))
    )
    (net (code "222") (name "Net-(B11C-IN3)") (class "Default")
      (node (ref "B11") (pin "H1") (pinfunction "IN3_H1") (pintype "input"))
      (node (ref "B11") (pin "N1") (pinfunction "OUT_N1") (pintype "output"))
    )
    (net (code "223") (name "Net-(B11F-IN1)") (class "Default")
      (node (ref "B11") (pin "D2") (pinfunction "IN1_D2") (pintype "input"))
      (node (ref "B12") (pin "E1") (pinfunction "OUT_E1") (pintype "output"))
    )
    (net (code "224") (name "Net-(B11F-IN2)") (class "Default")
      (node (ref "B11") (pin "E2") (pinfunction "IN2_E2") (pintype "input"))
      (node (ref "B12") (pin "L1") (pinfunction "OUT_L1") (pintype "output"))
    )
    (net (code "225") (name "Net-(B11F-OUT)") (class "Default")
      (node (ref "B11") (pin "H2") (pinfunction "OUT_H2") (pintype "output"))
      (node (ref "C13") (pin "C1") (pinfunction "IN_C1") (pintype "input"))
    )
    (net (code "226") (name "Net-(B11G-IN3)") (class "Default")
      (node (ref "B11") (pin "L2") (pinfunction "IN3_L2") (pintype "input"))
      (node (ref "B15") (pin "S2") (pinfunction "OUT_S2") (pintype "output"))
    )
    (net (code "227") (name "Net-(B11I-OUT)") (class "Default")
      (node (ref "B11") (pin "V1") (pinfunction "OUT_V1") (pintype "output"))
      (node (ref "C17") (pin "J1") (pinfunction "IN_J1") (pintype "input"))
    )
    (net (code "228") (name "Net-(B12D-IN1)") (class "Default")
      (node (ref "B12") (pin "M1") (pinfunction "IN1_M1") (pintype "input"))
      (node (ref "C11") (pin "C1") (pinfunction "OUT_C1") (pintype "output"))
    )
    (net (code "229") (name "Net-(B12D-IN4)") (class "Default")
      (node (ref "B12") (pin "R1") (pinfunction "IN4_R1") (pintype "input"))
      (node (ref "C11") (pin "F1") (pinfunction "OUT_F1") (pintype "output"))
    )
    (net (code "230") (name "Net-(B12D-OUT)") (class "Default")
      (node (ref "B12") (pin "S1") (pinfunction "OUT_S1") (pintype "output"))
      (node (ref "C11") (pin "P1") (pinfunction "IN1_P1") (pintype "input"))
    )
    (net (code "231") (name "Net-(B12E-OUT)") (class "Default")
      (node (ref "B12") (pin "J2") (pinfunction "OUT_J2") (pintype "output"))
      (node (ref "B12") (pin "N2") (pinfunction "IN4_N2") (pintype "input"))
    )
    (net (code "232") (name "Net-(B12F-IN1)") (class "Default")
      (node (ref "B12") (pin "K2") (pinfunction "IN1_K2") (pintype "input"))
      (node (ref "C12") (pin "N1") (pinfunction "OUT_N1") (pintype "output"))
    )
    (net (code "233") (name "Net-(B12F-IN2)") (class "Default")
      (node (ref "B12") (pin "L2") (pinfunction "IN2_L2") (pintype "input"))
      (node (ref "C12") (pin "U1") (pinfunction "OUT_U1") (pintype "output"))
    )
    (net (code "234") (name "Net-(B12F-IN3)") (class "Default")
      (node (ref "B12") (pin "M2") (pinfunction "IN3_M2") (pintype "input"))
      (node (ref "C12") (pin "V1") (pinfunction "OUT_V1") (pintype "output"))
    )
    (net (code "235") (name "Net-(B12G-IN4)") (class "Default")
      (node (ref "B12") (pin "U2") (pinfunction "IN4_U2") (pintype "input"))
      (node (ref "C11") (pin "N1") (pinfunction "OUT_N1") (pintype "output"))
    )
    (net (code "236") (name "Net-(B12G-OUT)") (class "Default")
      (node (ref "B12") (pin "V2") (pinfunction "OUT_V2") (pintype "output"))
      (node (ref "C12") (pin "F1") (pinfunction "IN2_F1") (pintype "input"))
    )
    (net (code "237") (name "Net-(B13F-S)") (class "Default")
      (node (ref "B13") (pin "N2") (pinfunction "S_N2") (pintype "input"))
      (node (ref "B15") (pin "K1") (pinfunction "OUT_K1") (pintype "output"))
    )
    (net (code "238") (name "Net-(B14G-C)") (class "Default")
      (node (ref "B14") (pin "N1") (pinfunction "C_N1") (pintype "input"))
      (node (ref "B14") (pin "S2") (pinfunction "C_S2") (pintype "input"))
      (node (ref "D15") (pin "D2") (pinfunction "D2_D2") (pintype "output"))
    )
    (net (code "239") (name "Net-(B15G-OUT)") (class "Default")
      (node (ref "A14") (pin "H2") (pinfunction "H2_H2") (pintype "input"))
      (node (ref "A14") (pin "J2") (pinfunction "J2_J2") (pintype "input"))
      (node (ref "A14") (pin "K2") (pinfunction "K2_K2") (pintype "input"))
      (node (ref "B15") (pin "F1") (pinfunction "OUT_F1") (pintype "output"))
    )
    (net (code "240") (name "Net-(B15K-OUT)") (class "Default")
      (node (ref "B15") (pin "N1") (pinfunction "OUT_N1") (pintype "output"))
      (node (ref "C17") (pin "F1") (pinfunction "IN_F1") (pintype "input"))
    )
    (net (code "241") (name "Net-(B15M-OUT)") (class "Default")
      (node (ref "B15") (pin "S1") (pinfunction "OUT_S1") (pintype "output"))
      (node (ref "C17") (pin "L1") (pinfunction "IN_L1") (pintype "input"))
    )
    (net (code "242") (name "Net-(B16-PadD2)") (class "Default")
      (node (ref "B16") (pin "D2") (pinfunction "D2_D2") (pintype "passive"))
      (node (ref "B16") (pin "E2") (pinfunction "E2_E2") (pintype "passive"))
    )
    (net (code "243") (name "Net-(B16B-D2)") (class "Default")
      (node (ref "B16") (pin "R2") (pinfunction "E2_R2") (pintype "passive"))
      (node (ref "B16") (pin "S2") (pinfunction "D2_S2") (pintype "passive"))
    )
    (net (code "244") (name "Net-(C08A-OUT)") (class "Default")
      (node (ref "C08") (pin "E1") (pinfunction "OUT_E1") (pintype "output"))
      (node (ref "C09") (pin "D1") (pinfunction "S_D1") (pintype "input"))
    )
    (net (code "245") (name "Net-(C08C-OUT)") (class "Default")
      (node (ref "C08") (pin "L1") (pinfunction "OUT_L1") (pintype "output"))
      (node (ref "C09") (pin "F2") (pinfunction "S_F2") (pintype "input"))
    )
    (net (code "246") (name "Net-(C08D-OUT)") (class "Default")
      (node (ref "C08") (pin "S1") (pinfunction "OUT_S1") (pintype "output"))
      (node (ref "C09") (pin "K1") (pinfunction "S_K1") (pintype "input"))
    )
    (net (code "247") (name "Net-(C08E-OUT)") (class "Default")
      (node (ref "C08") (pin "J2") (pinfunction "OUT_J2") (pintype "output"))
      (node (ref "C09") (pin "N2") (pinfunction "S_N2") (pintype "input"))
    )
    (net (code "248") (name "Net-(C08F-OUT)") (class "Default")
      (node (ref "C08") (pin "P2") (pinfunction "OUT_P2") (pintype "output"))
      (node (ref "C09") (pin "R1") (pinfunction "S_R1") (pintype "input"))
    )
    (net (code "249") (name "Net-(C08G-OUT)") (class "Default")
      (node (ref "C08") (pin "V2") (pinfunction "OUT_V2") (pintype "output"))
      (node (ref "C09") (pin "U2") (pinfunction "S_U2") (pintype "input"))
    )
    (net (code "250") (name "Net-(C10A-OUT)") (class "Default")
      (node (ref "C10") (pin "E1") (pinfunction "OUT_E1") (pintype "output"))
      (node (ref "C14") (pin "C1") (pinfunction "D_C1") (pintype "input"))
    )
    (net (code "251") (name "Net-(C10C-OUT)") (class "Default")
      (node (ref "C10") (pin "L1") (pinfunction "OUT_L1") (pintype "output"))
      (node (ref "C14") (pin "E2") (pinfunction "D_E2") (pintype "input"))
    )
    (net (code "252") (name "Net-(C10D-OUT)") (class "Default")
      (node (ref "C10") (pin "S1") (pinfunction "OUT_S1") (pintype "output"))
      (node (ref "C14") (pin "J1") (pinfunction "D_J1") (pintype "input"))
    )
    (net (code "253") (name "Net-(C10E-OUT)") (class "Default")
      (node (ref "C10") (pin "J2") (pinfunction "OUT_J2") (pintype "output"))
      (node (ref "C17") (pin "M2") (pinfunction "IN_M2") (pintype "input"))
    )
    (net (code "254") (name "Net-(C10G-OUT)") (class "Default")
      (node (ref "C10") (pin "V2") (pinfunction "OUT_V2") (pintype "output"))
      (node (ref "C17") (pin "V1") (pinfunction "IN_V1") (pintype "input"))
    )
    (net (code "255") (name "Net-(C11B-IN1)") (class "Default")
      (node (ref "C11") (pin "S2") (pinfunction "OUT_S2") (pintype "output"))
      (node (ref "C11") (pin "T2") (pinfunction "IN1_T2") (pintype "input"))
    )
    (net (code "256") (name "Net-(C11B-OUT)") (class "Default")
      (node (ref "C11") (pin "V2") (pinfunction "OUT_V2") (pintype "output"))
      (node (ref "C13") (pin "V1") (pinfunction "IN_V1") (pintype "input"))
    )
    (net (code "257") (name "Net-(C11H-OUT)") (class "Default")
      (node (ref "C11") (pin "F2") (pinfunction "OUT_F2") (pintype "output"))
      (node (ref "C12") (pin "H1") (pinfunction "IN3_H1") (pintype "input"))
    )
    (net (code "258") (name "Net-(C11I-OUT)") (class "Default")
      (node (ref "C11") (pin "K1") (pinfunction "OUT_K1") (pintype "output"))
      (node (ref "C11") (pin "L1") (pinfunction "IN1_L1") (pintype "input"))
    )
    (net (code "259") (name "Net-(C11J-OUT)") (class "Default")
      (node (ref "C11") (pin "K2") (pinfunction "OUT_K2") (pintype "output"))
      (node (ref "D12") (pin "K2") (pinfunction "IN1_K2") (pintype "input"))
      (node (ref "D12") (pin "L2") (pinfunction "IN2_L2") (pintype "input"))
    )
    (net (code "260") (name "Net-(C11M-OUT)") (class "Default")
      (node (ref "C11") (pin "S1") (pinfunction "OUT_S1") (pintype "output"))
      (node (ref "C12") (pin "E1") (pinfunction "IN1_E1") (pintype "input"))
    )
    (net (code "261") (name "Net-(C12A-OUT)") (class "Default")
      (node (ref "C12") (pin "D1") (pinfunction "OUT_D1") (pintype "output"))
      (node (ref "C13") (pin "M2") (pinfunction "IN_M2") (pintype "input"))
    )
    (net (code "262") (name "Net-(C12F-OUT)") (class "Default")
      (node (ref "C12") (pin "H2") (pinfunction "OUT_H2") (pintype "output"))
      (node (ref "D12") (pin "M2") (pinfunction "IN3_M2") (pintype "input"))
      (node (ref "D12") (pin "N2") (pinfunction "IN4_N2") (pintype "input"))
    )
    (net (code "263") (name "Net-(C12H-OUT)") (class "Default")
      (node (ref "C12") (pin "S2") (pinfunction "OUT_S2") (pintype "output"))
      (node (ref "C15") (pin "P1") (pinfunction "IN1_P1") (pintype "input"))
    )
    (net (code "264") (name "Net-(C13C-OUT)") (class "Default")
      (node (ref "C13") (pin "N2") (pinfunction "OUT_N2") (pintype "output"))
      (node (ref "C14") (pin "N2") (pinfunction "S_N2") (pintype "input"))
    )
    (net (code "265") (name "Net-(C13E-IN)") (class "Default")
      (node (ref "C13") (pin "P2") (pinfunction "IN_P2") (pintype "input"))
      (node (ref "C15") (pin "F2") (pinfunction "OUT_F2") (pintype "output"))
    )
    (net (code "266") (name "Net-(C13G-IN)") (class "Default")
      (node (ref "C13") (pin "S2") (pinfunction "IN_S2") (pintype "input"))
      (node (ref "C15") (pin "K2") (pinfunction "OUT_K2") (pintype "output"))
    )
    (net (code "267") (name "Net-(C13I-OUT)") (class "Default")
      (node (ref "C13") (pin "D2") (pinfunction "OUT_D2") (pintype "output"))
      (node (ref "C14") (pin "P1") (pinfunction "D_P1") (pintype "input"))
    )
    (net (code "268") (name "Net-(C14F-C)") (class "Default")
      (node (ref "C14") (pin "L2") (pinfunction "C_L2") (pintype "input"))
      (node (ref "C15") (pin "S2") (pinfunction "OUT_S2") (pintype "output"))
    )
    (net (code "269") (name "Net-(C15A-OUT)") (class "Default")
      (node (ref "C15") (pin "C1") (pinfunction "OUT_C1") (pintype "output"))
      (node (ref "C15") (pin "H1") (pinfunction "IN1_H1") (pintype "input"))
    )
    (net (code "270") (name "Net-(C15G-OUT)") (class "Default")
      (node (ref "C15") (pin "F1") (pinfunction "OUT_F1") (pintype "output"))
      (node (ref "C15") (pin "J1") (pinfunction "IN2_J1") (pintype "input"))
    )
    (net (code "271") (name "Net-(C15K-OUT)") (class "Default")
      (node (ref "C15") (pin "N1") (pinfunction "OUT_N1") (pintype "output"))
      (node (ref "C15") (pin "R1") (pinfunction "IN2_R1") (pintype "input"))
    )
    (net (code "272") (name "Net-(C15L-OUT)") (class "Default")
      (node (ref "C15") (pin "N2") (pinfunction "OUT_N2") (pintype "output"))
      (node (ref "C17") (pin "P2") (pinfunction "IN_P2") (pintype "input"))
    )
    (net (code "273") (name "Net-(C16C-OUT)") (class "Default")
      (node (ref "B16") (pin "K2") (pinfunction "K2_K2") (pintype "input"))
      (node (ref "C16") (pin "S1") (pinfunction "OUT_S1") (pintype "output"))
    )
    (net (code "274") (name "Net-(C16E-IN1)") (class "Default")
      (node (ref "C16") (pin "K2") (pinfunction "IN1_K2") (pintype "input"))
      (node (ref "C16") (pin "L2") (pinfunction "IN2_L2") (pintype "input"))
      (node (ref "C16") (pin "M2") (pinfunction "IN3_M2") (pintype "input"))
      (node (ref "C16") (pin "N2") (pinfunction "IN4_N2") (pintype "input"))
      (node (ref "C17") (pin "B1") (pinfunction "OUT_B1") (pintype "output"))
    )
    (net (code "275") (name "Net-(C16F-OUT)") (class "Default")
      (node (ref "A16") (pin "H2") (pinfunction "H2_H2") (pintype "input"))
      (node (ref "C16") (pin "V2") (pinfunction "OUT_V2") (pintype "output"))
    )
    (net (code "276") (name "Net-(C17C-OUT)") (class "Default")
      (node (ref "C17") (pin "N2") (pinfunction "OUT_N2") (pintype "output"))
      (node (ref "D08") (pin "B1") (pinfunction "B1_B1") (pintype "input"))
      (node (ref "D08") (pin "H1") (pinfunction "H1_H1") (pintype "input"))
      (node (ref "D08") (pin "N1") (pinfunction "N1_N1") (pintype "input"))
    )
    (net (code "277") (name "Net-(C17D-IN)") (class "Default")
      (node (ref "C17") (pin "R1") (pinfunction "IN_R1") (pintype "input"))
      (node (ref "D17") (pin "F2") (pinfunction "F2_F2") (pintype "output"))
    )
    (net (code "278") (name "Net-(C17F-OUT)") (class "Default")
      (node (ref "C17") (pin "U1") (pinfunction "OUT_U1") (pintype "output"))
      (node (ref "D08") (pin "D2") (pinfunction "D2_D2") (pintype "input"))
      (node (ref "D08") (pin "L2") (pinfunction "L2_L2") (pintype "input"))
      (node (ref "D08") (pin "S2") (pinfunction "S2_S2") (pintype "input"))
    )
    (net (code "279") (name "Net-(C17G-IN)") (class "Default")
      (node (ref "C17") (pin "S2") (pinfunction "IN_S2") (pintype "input"))
      (node (ref "D16") (pin "T2") (pinfunction "F2_T2") (pintype "output"))
    )
    (net (code "280") (name "Net-(C17I-IN)") (class "Default")
      (node (ref "A16") (pin "F2") (pinfunction "F2_F2") (pintype "output"))
      (node (ref "C17") (pin "C1") (pinfunction "IN_C1") (pintype "input"))
    )
    (net (code "281") (name "Net-(C17L-IN)") (class "Default")
      (node (ref "B16") (pin "F2") (pinfunction "F2_F2") (pintype "output"))
      (node (ref "C17") (pin "E2") (pinfunction "IN_E2") (pintype "input"))
    )
    (net (code "282") (name "Net-(D09A-OUT)") (class "Default")
      (node (ref "D08") (pin "C1") (pinfunction "C1_C1") (pintype "input"))
      (node (ref "D08") (pin "D1") (pinfunction "D1_D1") (pintype "input"))
      (node (ref "D09") (pin "E1") (pinfunction "OUT_E1") (pintype "output"))
    )
    (net (code "283") (name "Net-(D09C-OUT)") (class "Default")
      (node (ref "D08") (pin "J1") (pinfunction "J1_J1") (pintype "input"))
      (node (ref "D08") (pin "K1") (pinfunction "K1_K1") (pintype "input"))
      (node (ref "D09") (pin "L1") (pinfunction "OUT_L1") (pintype "output"))
    )
    (net (code "284") (name "Net-(D09D-OUT)") (class "Default")
      (node (ref "D08") (pin "P1") (pinfunction "P1_P1") (pintype "input"))
      (node (ref "D08") (pin "R1") (pinfunction "R1_R1") (pintype "input"))
      (node (ref "D09") (pin "S1") (pinfunction "OUT_S1") (pintype "output"))
    )
    (net (code "285") (name "Net-(D09E-OUT)") (class "Default")
      (node (ref "D08") (pin "E2") (pinfunction "E2_E2") (pintype "input"))
      (node (ref "D08") (pin "F2") (pinfunction "F2_F2") (pintype "input"))
      (node (ref "D09") (pin "J2") (pinfunction "OUT_J2") (pintype "output"))
    )
    (net (code "286") (name "Net-(D09F-OUT)") (class "Default")
      (node (ref "D08") (pin "M2") (pinfunction "M2_M2") (pintype "input"))
      (node (ref "D08") (pin "N2") (pinfunction "N2_N2") (pintype "input"))
      (node (ref "D09") (pin "P2") (pinfunction "OUT_P2") (pintype "output"))
    )
    (net (code "287") (name "Net-(D09G-OUT)") (class "Default")
      (node (ref "D08") (pin "T2") (pinfunction "T2_T2") (pintype "input"))
      (node (ref "D08") (pin "U2") (pinfunction "U2_U2") (pintype "input"))
      (node (ref "D09") (pin "V2") (pinfunction "OUT_V2") (pintype "output"))
    )
    (net (code "288") (name "Net-(D10B-OUT)") (class "Default")
      (node (ref "D10") (pin "P2") (pinfunction "OUT_P2") (pintype "output"))
      (node (ref "D14") (pin "J2") (pinfunction "N1_J2") (pintype "input"))
    )
    (net (code "289") (name "Net-(D12A-IN1)") (class "Default")
      (node (ref "D12") (pin "A1") (pinfunction "IN1_A1") (pintype "input"))
      (node (ref "D12") (pin "B1") (pinfunction "IN2_B1") (pintype "input"))
      (node (ref "D12") (pin "C1") (pinfunction "IN3_C1") (pintype "input"))
      (node (ref "D12") (pin "D1") (pinfunction "IN4_D1") (pintype "input"))
      (node (ref "D13") (pin "F2") (pinfunction "F2_F2") (pintype "output"))
    )
    (net (code "290") (name "Net-(D13B-D2)") (class "Default")
      (node (ref "D13") (pin "R2") (pinfunction "E2_R2") (pintype "passive"))
      (node (ref "D13") (pin "S2") (pinfunction "D2_S2") (pintype "passive"))
    )
    (net (code "291") (name "Net-(D14-PadM2)") (class "Default")
      (node (ref "D14") (pin "M2") (pinfunction "M2_M2") (pintype "passive"))
      (node (ref "D14") (pin "V2") (pinfunction "V2_V2") (pintype "passive"))
    )
    (net (code "292") (name "Net-(D14-PadP1)") (class "Default")
      (node (ref "D14") (pin "P1") (pinfunction "P1_P1") (pintype "passive"))
      (node (ref "D14") (pin "V1") (pinfunction "V1_V1") (pintype "passive"))
    )
    (net (code "293") (name "Net-(D14B-M2)") (class "Default")
      (node (ref "D14") (pin "D2") (pinfunction "M2_D2") (pintype "passive"))
      (node (ref "D14") (pin "H1") (pinfunction "P2_H1") (pintype "passive"))
    )
    (net (code "294") (name "Net-(D14B-P1)") (class "Default")
      (node (ref "D14") (pin "A1") (pinfunction "V1_A1") (pintype "passive"))
      (node (ref "D14") (pin "C1") (pinfunction "P1_C1") (pintype "passive"))
    )
    (net (code "295") (name "Net-(D15-PadN2)") (class "Default")
      (node (ref "D15") (pin "N2") (pinfunction "N2_N2") (pintype "passive"))
      (node (ref "D15") (pin "S2") (pinfunction "S2_S2") (pintype "passive"))
    )
    (net (code "296") (name "Net-(D16B-D2)") (class "Default")
      (node (ref "D16") (pin "R2") (pinfunction "E2_R2") (pintype "passive"))
      (node (ref "D16") (pin "V2") (pinfunction "D2_V2") (pintype "passive"))
    )
    (net (code "297") (name "Net-(D16B-H1)") (class "Default")
      (node (ref "D16") (pin "S1") (pinfunction "H1_S1") (pintype "passive"))
      (node (ref "D16") (pin "S2") (pinfunction "L2_S2") (pintype "passive"))
    )
    (net (code "298") (name "Net-(D17-PadD2)") (class "Default")
      (node (ref "D17") (pin "D2") (pinfunction "D2_D2") (pintype "passive"))
      (node (ref "D17") (pin "E2") (pinfunction "E2_E2") (pintype "passive"))
    )
    (net (code "299") (name "Net-(D17B-D2)") (class "Default")
      (node (ref "D17") (pin "R2") (pinfunction "E2_R2") (pintype "passive"))
      (node (ref "D17") (pin "S2") (pinfunction "D2_S2") (pintype "passive"))
    )
    (net (code "300") (name "PAR") (class "Default")
      (node (ref "A08") (pin "U1") (pinfunction "0_U1") (pintype "output"))
      (node (ref "A25") (pin "T1") (pinfunction "P$2_T1") (pintype "bidirectional"))
    )
    (net (code "301") (name "PC+ES") (class "Default")
      (node (ref "A11") (pin "H2") (pinfunction "IN_H2") (pintype "input"))
      (node (ref "A12") (pin "C1") (pinfunction "OUT_C1") (pintype "output"))
    )
    (net (code "302") (name "PWR_CLR") (class "Default")
      (node (ref "C06") (pin "R2") (pinfunction "OUT_R2") (pintype "output"))
    )
    (net (code "303") (name "RD+WD") (class "Default")
      (node (ref "A09") (pin "P1") (pinfunction "IN3_P1") (pintype "input"))
      (node (ref "B08") (pin "N2") (pinfunction "OUT_N2") (pintype "output"))
      (node (ref "B12") (pin "D2") (pinfunction "IN1_D2") (pintype "input"))
      (node (ref "C12") (pin "R1") (pinfunction "IN2_R1") (pintype "input"))
    )
    (net (code "304") (name "RDD_00") (class "Default")
      (node (ref "A21") (pin "U2") (pinfunction "U2_U2") (pintype "output"))
      (node (ref "B09") (pin "M2") (pinfunction "D_M2") (pintype "input"))
      (node (ref "D09") (pin "C1") (pinfunction "IN2A_C1") (pintype "input"))
      (node (ref "D09") (pin "F2") (pinfunction "IN2A_F2") (pintype "input"))
    )
    (net (code "305") (name "RDD_01") (class "Default")
      (node (ref "B09") (pin "P1") (pinfunction "D_P1") (pintype "input"))
      (node (ref "B20") (pin "U2") (pinfunction "U2_U2") (pintype "output"))
      (node (ref "D09") (pin "J1") (pinfunction "IN2A_J1") (pintype "input"))
      (node (ref "D09") (pin "M2") (pinfunction "IN2A_M2") (pintype "input"))
    )
    (net (code "306") (name "RDD_02") (class "Default")
      (node (ref "A20") (pin "U2") (pinfunction "U2_U2") (pintype "output"))
      (node (ref "B09") (pin "E2") (pinfunction "D_E2") (pintype "input"))
      (node (ref "D09") (pin "P1") (pinfunction "IN2A_P1") (pintype "input"))
      (node (ref "D09") (pin "T2") (pinfunction "IN2A_T2") (pintype "input"))
    )
    (net (code "307") (name "RDMK") (class "Default")
      (node (ref "B18") (pin "U2") (pinfunction "U2_U2") (pintype "output"))
      (node (ref "CD18") (pin "AS2") (pinfunction "AS2_AS2") (pintype "input"))
    )
    (net (code "308") (name "RD_EN") (class "Default")
      (node (ref "C11") (pin "J1") (pinfunction "IN2_J1") (pintype "input"))
      (node (ref "C11") (pin "N2") (pinfunction "OUT_N2") (pintype "output"))
    )
    (net (code "309") (name "RD_EN_LPB_00-02") (class "Default")
      (node (ref "C10") (pin "D2") (pinfunction "IN1A_D2") (pintype "input"))
      (node (ref "C13") (pin "T2") (pinfunction "OUT_T2") (pintype "output"))
      (node (ref "D09") (pin "D1") (pinfunction "IN2B_D1") (pintype "input"))
      (node (ref "D09") (pin "K1") (pinfunction "IN2B_K1") (pintype "input"))
      (node (ref "D09") (pin "R1") (pinfunction "IN2B_R1") (pintype "input"))
    )
    (net (code "310") (name "RD_EN_LPB_03-05") (class "Default")
      (node (ref "C10") (pin "R2") (pinfunction "IN1A_R2") (pintype "input"))
      (node (ref "C13") (pin "R2") (pinfunction "OUT_R2") (pintype "output"))
      (node (ref "D09") (pin "H2") (pinfunction "IN2B_H2") (pintype "input"))
      (node (ref "D09") (pin "N2") (pinfunction "IN2B_N2") (pintype "input"))
      (node (ref "D09") (pin "U2") (pinfunction "IN2B_U2") (pintype "input"))
    )
    (net (code "311") (name "READ_ALL") (class "Default")
      (node (ref "D07") (pin "N2") (pinfunction "O3_N2") (pintype "output"))
    )
    (net (code "312") (name "READ_DATA") (class "Default")
      (node (ref "A10") (pin "L1") (pinfunction "IN1_L1") (pintype "input"))
      (node (ref "C11") (pin "H1") (pinfunction "IN1_H1") (pintype "input"))
      (node (ref "D07") (pin "J2") (pinfunction "O2_J2") (pintype "output"))
    )
    (net (code "313") (name "RSTA") (class "Default")
      (node (ref "C04") (pin "B1") (pinfunction "B1_B1") (pintype "output"))
    )
    (net (code "314") (name "RSTB") (class "Default")
      (node (ref "C05") (pin "D1") (pinfunction "D1_D1") (pintype "output"))
    )
    (net (code "315") (name "SE") (class "Default")
      (node (ref "D07") (pin "L2") (pinfunction "O7_L2") (pintype "output"))
    )
    (net (code "316") (name "SEARCH") (class "Default")
      (node (ref "C11") (pin "D2") (pinfunction "IN1_D2") (pintype "input"))
      (node (ref "D07") (pin "E2") (pinfunction "O1_E2") (pintype "output"))
    )
    (net (code "317") (name "SEL") (class "Default")
      (node (ref "A08") (pin "H2") (pinfunction "1_H2") (pintype "output"))
      (node (ref "A25") (pin "S1") (pinfunction "P$2_S1") (pintype "bidirectional"))
    )
    (net (code "318") (name "SHIFT_CK") (class "Default")
      (node (ref "C17") (pin "K1") (pinfunction "OUT_K1") (pintype "output"))
      (node (ref "CD18") (pin "BR2") (pinfunction "BR2_BR2") (pintype "input"))
    )
    (net (code "319") (name "SH_DTB") (class "Default")
      (node (ref "A10") (pin "R2") (pinfunction "IN2_R2") (pintype "input"))
      (node (ref "B09") (pin "B1") (pinfunction "C_B1") (pintype "input"))
      (node (ref "B09") (pin "D2") (pinfunction "C_D2") (pintype "input"))
      (node (ref "B09") (pin "H1") (pinfunction "C_H1") (pintype "input"))
      (node (ref "B09") (pin "L2") (pinfunction "C_L2") (pintype "input"))
      (node (ref "B09") (pin "N1") (pinfunction "C_N1") (pintype "input"))
      (node (ref "B09") (pin "S2") (pinfunction "C_S2") (pintype "input"))
      (node (ref "B10") (pin "E1") (pinfunction "OUT_E1") (pintype "output"))
      (node (ref "C09") (pin "B1") (pinfunction "C_B1") (pintype "input"))
      (node (ref "C09") (pin "D2") (pinfunction "C_D2") (pintype "input"))
      (node (ref "C09") (pin "H1") (pinfunction "C_H1") (pintype "input"))
      (node (ref "C09") (pin "L2") (pinfunction "C_L2") (pintype "input"))
      (node (ref "C09") (pin "N1") (pinfunction "C_N1") (pintype "input"))
      (node (ref "C09") (pin "S2") (pinfunction "C_S2") (pintype "input"))
    )
    (net (code "320") (name "SH_EN") (class "Default")
      (node (ref "A11") (pin "N2") (pinfunction "OUT_N2") (pintype "output"))
      (node (ref "A12") (pin "E2") (pinfunction "IN2_E2") (pintype "input"))
      (node (ref "C10") (pin "A1") (pinfunction "IN1A_A1") (pintype "input"))
      (node (ref "C10") (pin "F1") (pinfunction "IN1A_F1") (pintype "input"))
      (node (ref "C10") (pin "M1") (pinfunction "IN1A_M1") (pintype "input"))
    )
    (net (code "321") (name "SH_ST") (class "Default")
      (node (ref "C17") (pin "A1") (pinfunction "IN_A1") (pintype "input"))
      (node (ref "CD18") (pin "AM1") (pinfunction "AM1_AM1") (pintype "output"))
    )
    (net (code "322") (name "SH_ST-B") (class "Default")
      (node (ref "C16") (pin "P2") (pinfunction "OUT_P2") (pintype "output"))
      (node (ref "CD18") (pin "BC1") (pinfunction "BC1_BC1") (pintype "input"))
    )
    (net (code "323") (name "SP_DY") (class "Default")
      (node (ref "D14") (pin "H2") (pinfunction "H2_H2") (pintype "output"))
    )
    (net (code "324") (name "ST_BLK_MK") (class "Default")
      (node (ref "A26") (pin "K1") (pinfunction "P$2_K1") (pintype "bidirectional"))
      (node (ref "C13") (pin "E2") (pinfunction "IN_E2") (pintype "input"))
      (node (ref "CD18") (pin "AR2") (pinfunction "AR2_AR2") (pintype "output"))
    )
    (net (code "325") (name "ST_CK") (class "Default")
      (node (ref "A10") (pin "P1") (pinfunction "IN1_P1") (pintype "input"))
      (node (ref "A26") (pin "P1") (pinfunction "P$2_P1") (pintype "bidirectional"))
      (node (ref "C13") (pin "J1") (pinfunction "IN_J1") (pintype "input"))
      (node (ref "CD18") (pin "BR1") (pinfunction "BR1_BR1") (pintype "output"))
      (node (ref "D17") (pin "M2") (pinfunction "K2_M2") (pintype "input"))
      (node (ref "D17") (pin "N2") (pinfunction "J2_N2") (pintype "input"))
      (node (ref "D17") (pin "P2") (pinfunction "H2_P2") (pintype "input"))
    )
    (net (code "326") (name "ST_CK_0P") (class "Default")
      (node (ref "B12") (pin "H2") (pinfunction "IN4_H2") (pintype "input"))
      (node (ref "C12") (pin "S1") (pinfunction "IN3_S1") (pintype "input"))
      (node (ref "C13") (pin "B1") (pinfunction "OUT_B1") (pintype "output"))
    )
    (net (code "327") (name "ST_DATA") (class "Default")
      (node (ref "B12") (pin "A1") (pinfunction "IN1_A1") (pintype "input"))
      (node (ref "C13") (pin "H2") (pinfunction "IN_H2") (pintype "input"))
      (node (ref "C16") (pin "J2") (pinfunction "OUT_J2") (pintype "output"))
    )
    (net (code "328") (name "ST_FINAL") (class "Default")
      (node (ref "A09") (pin "S2") (pinfunction "IN2_S2") (pintype "input"))
      (node (ref "A26") (pin "N1") (pinfunction "P$2_N1") (pintype "bidirectional"))
      (node (ref "C11") (pin "D1") (pinfunction "IN1_D1") (pintype "input"))
      (node (ref "C13") (pin "L1") (pinfunction "IN_L1") (pintype "input"))
      (node (ref "CD18") (pin "BL2") (pinfunction "BL2_BL2") (pintype "output"))
    )
    (net (code "329") (name "ST_IDLE") (class "Default")
      (node (ref "A26") (pin "R1") (pinfunction "P$2_R1") (pintype "bidirectional"))
      (node (ref "C13") (pin "K2") (pinfunction "IN_K2") (pintype "input"))
      (node (ref "CD18") (pin "BD2") (pinfunction "BD2_BD2") (pintype "input"))
    )
    (net (code "330") (name "ST_REV_CK") (class "Default")
      (node (ref "A26") (pin "L1") (pinfunction "P$2_L1") (pintype "bidirectional"))
      (node (ref "B11") (pin "S1") (pinfunction "IN3_S1") (pintype "input"))
      (node (ref "C11") (pin "A1") (pinfunction "IN1_A1") (pintype "input"))
      (node (ref "C13") (pin "D1") (pinfunction "IN_D1") (pintype "input"))
      (node (ref "CD18") (pin "BS1") (pinfunction "BS1_BS1") (pintype "output"))
      (node (ref "D12") (pin "F2") (pinfunction "IN3_F2") (pintype "input"))
      (node (ref "D12") (pin "H2") (pinfunction "IN4_H2") (pintype "input"))
    )
    (net (code "331") (name "SWTM") (class "Default")
      (node (ref "A26") (pin "V2") (pinfunction "P$2_V2") (pintype "bidirectional"))
      (node (ref "B06") (pin "P2") (pinfunction "IN_P2") (pintype "input"))
      (node (ref "B08") (pin "V1") (pinfunction "P$1_V1") (pintype "output"))
      (node (ref "B11") (pin "B1") (pinfunction "IN2_B1") (pintype "input"))
      (node (ref "C10") (pin "N2") (pinfunction "IN2B_N2") (pintype "input"))
      (node (ref "C12") (pin "P2") (pinfunction "IN2_P2") (pintype "input"))
      (node (ref "C15") (pin "L1") (pinfunction "IN1_L1") (pintype "input"))
    )
    (net (code "332") (name "SYNC") (class "Default")
      (node (ref "B10") (pin "D2") (pinfunction "IN1_D2") (pintype "input"))
      (node (ref "B10") (pin "E2") (pinfunction "IN2_E2") (pintype "input"))
      (node (ref "CD18") (pin "BN2") (pinfunction "BN2_BN2") (pintype "output"))
    )
    (net (code "333") (name "SYNC_EN") (class "Default")
      (node (ref "B11") (pin "M2") (pinfunction "OUT_M2") (pintype "output"))
      (node (ref "CD18") (pin "BH1") (pinfunction "BH1_BH1") (pintype "input"))
    )
    (net (code "334") (name "T3") (class "Default")
      (node (ref "C17") (pin "S1") (pinfunction "OUT_S1") (pintype "output"))
      (node (ref "D12") (pin "N1") (pinfunction "IN2_N1") (pintype "input"))
      (node (ref "D12") (pin "P1") (pinfunction "IN3_P1") (pintype "input"))
    )
    (net (code "335") (name "TIM") (class "Default")
      (node (ref "A08") (pin "L1") (pinfunction "1_L1") (pintype "output"))
      (node (ref "A25") (pin "U1") (pinfunction "P$2_U1") (pintype "bidirectional"))
    )
    (net (code "336") (name "TM_EN") (class "Default")
      (node (ref "A18") (pin "R2") (pinfunction "R2_R2") (pintype "input"))
      (node (ref "B18") (pin "R2") (pinfunction "R2_R2") (pintype "input"))
      (node (ref "C13") (pin "N1") (pinfunction "IN_N1") (pintype "input"))
      (node (ref "C15") (pin "S1") (pinfunction "OUT_S1") (pintype "output"))
      (node (ref "C16") (pin "M1") (pinfunction "IN1_M1") (pintype "input"))
      (node (ref "C16") (pin "R2") (pinfunction "IN1_R2") (pintype "input"))
    )
    (net (code "337") (name "TP00") (class "Default")
      (node (ref "A08") (pin "B1") (pinfunction "C_B1") (pintype "input"))
      (node (ref "A15") (pin "L1") (pinfunction "OUT_L1") (pintype "output"))
      (node (ref "A16") (pin "M2") (pinfunction "K2_M2") (pintype "input"))
      (node (ref "A16") (pin "N2") (pinfunction "J2_N2") (pintype "input"))
      (node (ref "A16") (pin "P2") (pinfunction "H2_P2") (pintype "input"))
      (node (ref "B10") (pin "F2") (pinfunction "IN3_F2") (pintype "input"))
      (node (ref "B10") (pin "H2") (pinfunction "IN4_H2") (pintype "input"))
      (node (ref "B10") (pin "N1") (pinfunction "IN2_N1") (pintype "input"))
      (node (ref "B13") (pin "B1") (pinfunction "C_B1") (pintype "input"))
      (node (ref "B13") (pin "D2") (pinfunction "C_D2") (pintype "input"))
      (node (ref "B13") (pin "H1") (pinfunction "C_H1") (pintype "input"))
      (node (ref "B15") (pin "J1") (pinfunction "IN2_J1") (pintype "input"))
      (node (ref "C15") (pin "E1") (pinfunction "IN2_E1") (pintype "input"))
    )
    (net (code "338") (name "TP00_A") (class "Default")
      (node (ref "A15") (pin "S1") (pinfunction "OUT_S1") (pintype "output"))
      (node (ref "B10") (pin "H1") (pinfunction "IN2_H1") (pintype "input"))
      (node (ref "C12") (pin "E2") (pinfunction "IN2_E2") (pintype "input"))
    )
    (net (code "339") (name "TP01") (class "Default")
      (node (ref "A12") (pin "J2") (pinfunction "IN2_J2") (pintype "input"))
      (node (ref "A15") (pin "P2") (pinfunction "OUT_P2") (pintype "output"))
      (node (ref "B16") (pin "M2") (pinfunction "K2_M2") (pintype "input"))
      (node (ref "B16") (pin "N2") (pinfunction "J2_N2") (pintype "input"))
      (node (ref "B16") (pin "P2") (pinfunction "H2_P2") (pintype "input"))
      (node (ref "C11") (pin "J2") (pinfunction "IN2_J2") (pintype "input"))
      (node (ref "C15") (pin "B1") (pinfunction "IN2_B1") (pintype "input"))
      (node (ref "CD18") (pin "BF1") (pinfunction "BF1_BF1") (pintype "input"))
    )
    (net (code "340") (name "TP01_A") (class "Default")
      (node (ref "A15") (pin "V2") (pinfunction "OUT_V2") (pintype "output"))
      (node (ref "B12") (pin "T2") (pinfunction "IN3_T2") (pintype "input"))
      (node (ref "C15") (pin "M2") (pinfunction "IN2_M2") (pintype "input"))
    )
    (net (code "341") (name "T_TRK") (class "Default")
      (node (ref "A18") (pin "U2") (pinfunction "U2_U2") (pintype "output"))
      (node (ref "B15") (pin "E2") (pinfunction "IN2_E2") (pintype "input"))
      (node (ref "C15") (pin "R2") (pinfunction "IN2_R2") (pintype "input"))
      (node (ref "D14") (pin "S1") (pinfunction "S1_S1") (pintype "input"))
      (node (ref "D14") (pin "U1") (pinfunction "U1_U1") (pintype "input"))
    )
    (net (code "342") (name "U+M_DY") (class "Default")
      (node (ref "D14") (pin "K1") (pinfunction "H2_K1") (pintype "output"))
    )
    (net (code "343") (name "USR_00") (class "Default")
      (node (ref "A07") (pin "V2") (pinfunction "IN2_V2") (pintype "input"))
      (node (ref "A25") (pin "A1") (pinfunction "P$2_A1") (pintype "bidirectional"))
      (node (ref "B07") (pin "E1") (pinfunction "E1_E1") (pintype "output"))
    )
    (net (code "344") (name "USR_01") (class "Default")
      (node (ref "A07") (pin "U2") (pinfunction "IN1_U2") (pintype "input"))
      (node (ref "A25") (pin "B1") (pinfunction "P$2_B1") (pintype "bidirectional"))
      (node (ref "B07") (pin "H2") (pinfunction "H2_H2") (pintype "output"))
    )
    (net (code "345") (name "USR_02") (class "Default")
      (node (ref "A07") (pin "V1") (pinfunction "IN0_V1") (pintype "input"))
      (node (ref "A25") (pin "C1") (pinfunction "P$2_C1") (pintype "bidirectional"))
      (node (ref "B07") (pin "L1") (pinfunction "L1_L1") (pintype "output"))
    )
    (net (code "346") (name "UTS") (class "Default")
      (node (ref "A10") (pin "E1") (pinfunction "IN2_E1") (pintype "input"))
      (node (ref "A26") (pin "J1") (pinfunction "P$2_J1") (pintype "bidirectional"))
      (node (ref "B15") (pin "P1") (pinfunction "IN1_P1") (pintype "input"))
      (node (ref "C14") (pin "R2") (pinfunction "0_R2") (pintype "output"))
    )
    (net (code "347") (name "VCC") (class "Default")
      (node (ref "AB01") (pin "AA2") (pinfunction "VCC_AA2") (pintype "power_in"))
      (node (ref "AB01") (pin "AB1") (pinfunction "VCC_AB1") (pintype "power_in"))
      (node (ref "AB01") (pin "AC1") (pinfunction "VCC_AC1") (pintype "power_in"))
      (node (ref "AB01") (pin "AD1") (pinfunction "VCC_AD1") (pintype "power_in"))
      (node (ref "AB01") (pin "AE1") (pinfunction "VCC_AE1") (pintype "power_in"))
      (node (ref "AB01") (pin "AF1") (pinfunction "VCC_AF1") (pintype "power_in"))
      (node (ref "AB01") (pin "AH1") (pinfunction "VCC_AH1") (pintype "power_in"))
      (node (ref "AB01") (pin "AJ1") (pinfunction "VCC_AJ1") (pintype "power_in"))
      (node (ref "AB01") (pin "AK1") (pinfunction "VCC_AK1") (pintype "power_in"))
      (node (ref "AB01") (pin "AL1") (pinfunction "VCC_AL1") (pintype "power_in"))
      (node (ref "AB01") (pin "BA2") (pinfunction "VCC_BA2") (pintype "power_in"))
      (node (ref "AB01") (pin "BB1") (pinfunction "VCC_BB1") (pintype "power_in"))
      (node (ref "AB01") (pin "BC1") (pinfunction "VCC_BC1") (pintype "power_in"))
      (node (ref "AB01") (pin "BD1") (pinfunction "VCC_BD1") (pintype "power_in"))
      (node (ref "AB01") (pin "BE1") (pinfunction "VCC_BE1") (pintype "power_in"))
    )
    (net (code "348") (name "W+UTS") (class "Default")
      (node (ref "A15") (pin "A1") (pinfunction "IN1_A1") (pintype "input"))
      (node (ref "A15") (pin "H2") (pinfunction "IN4_H2") (pintype "input"))
      (node (ref "C12") (pin "M2") (pinfunction "OUT_M2") (pintype "output"))
    )
    (net (code "349") (name "W-INH") (class "Default")
      (node (ref "A08") (pin "V1") (pinfunction "0_V1") (pintype "output"))
    )
    (net (code "350") (name "W01") (class "Default")
      (node (ref "A26") (pin "J2") (pinfunction "P$2_J2") (pintype "bidirectional"))
      (node (ref "CD18") (pin "BJ2") (pinfunction "BJ2_BJ2") (pintype "output"))
    )
    (net (code "351") (name "W01-W05") (class "Default")
      (node (ref "CD18") (pin "AK1") (pinfunction "AK1_AK1") (pintype "output"))
    )
    (net (code "352") (name "W02") (class "Default")
      (node (ref "A26") (pin "K2") (pinfunction "P$2_K2") (pintype "bidirectional"))
      (node (ref "CD18") (pin "BV2") (pinfunction "BV2_BV2") (pintype "output"))
    )
    (net (code "353") (name "W03") (class "Default")
      (node (ref "A26") (pin "L2") (pinfunction "P$2_L2") (pintype "bidirectional"))
      (node (ref "CD18") (pin "BE2") (pinfunction "BE2_BE2") (pintype "output"))
    )
    (net (code "354") (name "W04") (class "Default")
      (node (ref "A26") (pin "M2") (pinfunction "P$2_M2") (pintype "bidirectional"))
      (node (ref "CD18") (pin "AT2") (pinfunction "AT2_AT2") (pintype "output"))
    )
    (net (code "355") (name "W05") (class "Default")
      (node (ref "A26") (pin "N2") (pinfunction "P$2_N2") (pintype "bidirectional"))
      (node (ref "CD18") (pin "BU2") (pinfunction "BU2_BU2") (pintype "output"))
    )
    (net (code "356") (name "W06") (class "Default")
      (node (ref "A26") (pin "P2") (pinfunction "P$2_P2") (pintype "bidirectional"))
      (node (ref "CD18") (pin "AM2") (pinfunction "AM2_AM2") (pintype "output"))
    )
    (net (code "357") (name "W07") (class "Default")
      (node (ref "A26") (pin "R2") (pinfunction "P$2_R2") (pintype "bidirectional"))
      (node (ref "CD18") (pin "AK2") (pinfunction "AK2_AK2") (pintype "output"))
    )
    (net (code "358") (name "W08") (class "Default")
      (node (ref "A26") (pin "S2") (pinfunction "P$2_S2") (pintype "bidirectional"))
      (node (ref "CD18") (pin "AL1") (pinfunction "AL1_AL1") (pintype "output"))
    )
    (net (code "359") (name "W09") (class "Default")
      (node (ref "A26") (pin "T2") (pinfunction "P$2_T2") (pintype "bidirectional"))
      (node (ref "CD18") (pin "BF2") (pinfunction "BF2_BF2") (pintype "output"))
    )
    (net (code "360") (name "WB00") (class "Default")
      (node (ref "A21") (pin "N2") (pinfunction "N2_N2") (pintype "input"))
      (node (ref "A25") (pin "P2") (pinfunction "P$2_P2") (pintype "bidirectional"))
      (node (ref "B18") (pin "N2") (pinfunction "N2_N2") (pintype "input"))
      (node (ref "C14") (pin "F1") (pinfunction "0_F1") (pintype "output"))
      (node (ref "D09") (pin "A1") (pinfunction "IN1A_A1") (pintype "input"))
    )
    (net (code "361") (name "WB01") (class "Default")
      (node (ref "A25") (pin "R2") (pinfunction "P$2_R2") (pintype "bidirectional"))
      (node (ref "B20") (pin "N2") (pinfunction "N2_N2") (pintype "input"))
      (node (ref "C14") (pin "J2") (pinfunction "0_J2") (pintype "output"))
      (node (ref "D09") (pin "F1") (pinfunction "IN1A_F1") (pintype "input"))
    )
    (net (code "362") (name "WB02") (class "Default")
      (node (ref "A20") (pin "N2") (pinfunction "N2_N2") (pintype "input"))
      (node (ref "A25") (pin "S2") (pinfunction "P$2_S2") (pintype "bidirectional"))
      (node (ref "C14") (pin "M1") (pinfunction "0_M1") (pintype "output"))
      (node (ref "D09") (pin "M1") (pinfunction "IN1A_M1") (pintype "input"))
    )
    (net (code "363") (name "WC") (class "Default")
      (node (ref "A26") (pin "H1") (pinfunction "P$2_H1") (pintype "bidirectional"))
      (node (ref "B10") (pin "M1") (pinfunction "IN1_M1") (pintype "input"))
      (node (ref "B11") (pin "K1") (pinfunction "IN1_K1") (pintype "input"))
      (node (ref "D11") (pin "S1") (pinfunction "1_S1") (pintype "output"))
    )
    (net (code "364") (name "WC0") (class "Default")
      (node (ref "C01") (pin "H1") (pinfunction "OUT_H1") (pintype "output"))
      (node (ref "C06") (pin "M2") (pinfunction "IN_M2") (pintype "input"))
    )
    (net (code "365") (name "WRITE_ALL") (class "Default")
      (node (ref "A08") (pin "S2") (pinfunction "C_S2") (pintype "input"))
      (node (ref "B11") (pin "M1") (pinfunction "IN3_M1") (pintype "input"))
      (node (ref "B12") (pin "F1") (pinfunction "IN1_F1") (pintype "input"))
      (node (ref "D07") (pin "M2") (pinfunction "O5_M2") (pintype "output"))
    )
    (net (code "366") (name "WRITE_DATA") (class "Default")
      (node (ref "A09") (pin "R2") (pinfunction "IN1_R2") (pintype "input"))
      (node (ref "B11") (pin "R1") (pinfunction "IN2_R1") (pintype "input"))
      (node (ref "B12") (pin "B1") (pinfunction "IN2_B1") (pintype "input"))
      (node (ref "B12") (pin "P1") (pinfunction "IN3_P1") (pintype "input"))
      (node (ref "D07") (pin "F2") (pinfunction "O4_F2") (pintype "output"))
    )
    (net (code "367") (name "WRITE_OK") (class "Default")
      (node (ref "A22") (pin "D2") (pinfunction "D2_D2") (pintype "output"))
      (node (ref "B11") (pin "C1") (pinfunction "IN3_C1") (pintype "input"))
      (node (ref "B15") (pin "R1") (pinfunction "IN2_R1") (pintype "input"))
      (node (ref "C17") (pin "H2") (pinfunction "IN_H2") (pintype "input"))
    )
    (net (code "368") (name "WRITE_OK+UTS") (class "Default")
      (node (ref "B12") (pin "D1") (pinfunction "IN4_D1") (pintype "input"))
      (node (ref "B12") (pin "K1") (pinfunction "IN4_K1") (pintype "input"))
      (node (ref "C17") (pin "M1") (pinfunction "OUT_M1") (pintype "output"))
    )
    (net (code "369") (name "WRTM") (class "Default")
      (node (ref "B11") (pin "A1") (pinfunction "IN1_A1") (pintype "input"))
      (node (ref "C10") (pin "K2") (pinfunction "IN1A_K2") (pintype "input"))
      (node (ref "C12") (pin "N2") (pinfunction "IN1_N2") (pintype "input"))
      (node (ref "D07") (pin "H2") (pinfunction "O6_H2") (pintype "output"))
    )
    (net (code "370") (name "WRTM+FR03") (class "Default")
      (node (ref "B08") (pin "K2") (pinfunction "OUT_K2") (pintype "output"))
      (node (ref "C12") (pin "M1") (pinfunction "IN3_M1") (pintype "input"))
      (node (ref "C12") (pin "V2") (pinfunction "IN3_V2") (pintype "input"))
    )
    (net (code "371") (name "WR_EN") (class "Default")
      (node (ref "A20") (pin "R2") (pinfunction "R2_R2") (pintype "input"))
      (node (ref "A21") (pin "R2") (pinfunction "R2_R2") (pintype "input"))
      (node (ref "A26") (pin "F1") (pinfunction "P$2_F1") (pintype "bidirectional"))
      (node (ref "B20") (pin "R2") (pinfunction "R2_R2") (pintype "input"))
      (node (ref "C10") (pin "H2") (pinfunction "IN2B_H2") (pintype "input"))
      (node (ref "C10") (pin "U2") (pinfunction "IN2B_U2") (pintype "input"))
      (node (ref "C12") (pin "D2") (pinfunction "IN1_D2") (pintype "input"))
      (node (ref "C14") (pin "U1") (pinfunction "0_U1") (pintype "output"))
      (node (ref "C15") (pin "A1") (pinfunction "IN1_A1") (pintype "input"))
      (node (ref "C15") (pin "M1") (pinfunction "IN2_M1") (pintype "input"))
      (node (ref "D09") (pin "B1") (pinfunction "IN1B_B1") (pintype "input"))
      (node (ref "D09") (pin "E2") (pinfunction "IN1B_E2") (pintype "input"))
      (node (ref "D09") (pin "H1") (pinfunction "IN1B_H1") (pintype "input"))
      (node (ref "D09") (pin "L2") (pinfunction "IN1B_L2") (pintype "input"))
      (node (ref "D09") (pin "N1") (pinfunction "IN1B_N1") (pintype "input"))
      (node (ref "D09") (pin "S2") (pinfunction "IN1B_S2") (pintype "input"))
    )
    (net (code "372") (name "XOR_TO_LPB") (class "Default")
      (node (ref "C10") (pin "E2") (pinfunction "IN1B_E2") (pintype "input"))
      (node (ref "C10") (pin "F2") (pinfunction "IN2A_F2") (pintype "input"))
      (node (ref "C10") (pin "S2") (pinfunction "IN1B_S2") (pintype "input"))
      (node (ref "C10") (pin "T2") (pinfunction "IN2A_T2") (pintype "input"))
      (node (ref "D12") (pin "P2") (pinfunction "OUT_P2") (pintype "output"))
    )
    (net (code "373") (name "XSAD") (class "Default")
      (node (ref "A09") (pin "R1") (pinfunction "IN4_R1") (pintype "input"))
      (node (ref "A11") (pin "L2") (pinfunction "OUT_L2") (pintype "output"))
    )
    (net (code "374") (name "XSA_DY") (class "Default")
      (node (ref "A08") (pin "D2") (pinfunction "C_D2") (pintype "input"))
      (node (ref "B14") (pin "B1") (pinfunction "C_B1") (pintype "input"))
      (node (ref "B14") (pin "L2") (pinfunction "C_L2") (pintype "input"))
      (node (ref "C17") (pin "T2") (pinfunction "OUT_T2") (pintype "output"))
    )
    (net (code "375") (name "XSTA") (class "Default")
      (node (ref "B07") (pin "B1") (pinfunction "B1_B1") (pintype "input"))
      (node (ref "B07") (pin "D2") (pinfunction "D2_D2") (pintype "input"))
      (node (ref "B07") (pin "H1") (pinfunction "H1_H1") (pintype "input"))
      (node (ref "B07") (pin "L2") (pinfunction "L2_L2") (pintype "input"))
      (node (ref "B07") (pin "N1") (pinfunction "N1_N1") (pintype "input"))
      (node (ref "B07") (pin "S2") (pinfunction "S2_S2") (pintype "input"))
      (node (ref "C04") (pin "F1") (pinfunction "F1_F1") (pintype "output"))
      (node (ref "C07") (pin "B1") (pinfunction "B1_B1") (pintype "input"))
      (node (ref "C07") (pin "D2") (pinfunction "D2_D2") (pintype "input"))
      (node (ref "C07") (pin "H1") (pinfunction "H1_H1") (pintype "input"))
      (node (ref "C07") (pin "L2") (pinfunction "L2_L2") (pintype "input"))
      (node (ref "D11") (pin "N1") (pinfunction "C_N1") (pintype "input"))
      (node (ref "D13") (pin "M2") (pinfunction "K2_M2") (pintype "input"))
      (node (ref "D13") (pin "N2") (pinfunction "J2_N2") (pintype "input"))
      (node (ref "D13") (pin "P2") (pinfunction "H2_P2") (pintype "input"))
    )
    (net (code "376") (name "unconnected-(A07A-O8-PadP2)") (class "Default")
      (node (ref "A07") (pin "P2") (pinfunction "O8_P2") (pintype "output"))
    )
    (net (code "377") (name "unconnected-(A07A-O9-PadR2)") (class "Default")
      (node (ref "A07") (pin "R2") (pinfunction "O9_R2") (pintype "output"))
    )
    (net (code "378") (name "unconnected-(A07A-~{O8}-PadP1)") (class "Default")
      (node (ref "A07") (pin "P1") (pinfunction "~{O8}_P1") (pintype "output"))
    )
    (net (code "379") (name "unconnected-(A07A-~{O9}-PadR1)") (class "Default")
      (node (ref "A07") (pin "R1") (pinfunction "~{O9}_R1") (pintype "output"))
    )
    (net (code "380") (name "unconnected-(A14-PadD1)") (class "Default")
      (node (ref "A14") (pin "D1") (pinfunction "D1_D1") (pintype "passive"))
    )
    (net (code "381") (name "unconnected-(A14-PadE1)") (class "Default")
      (node (ref "A14") (pin "E1") (pinfunction "E1_E1") (pintype "passive"))
    )
    (net (code "382") (name "unconnected-(A14-PadF1)") (class "Default")
      (node (ref "A14") (pin "F1") (pinfunction "F1_F1") (pintype "passive"))
    )
    (net (code "383") (name "unconnected-(A14-PadJ1)") (class "Default")
      (node (ref "A14") (pin "J1") (pinfunction "J1_J1") (pintype "passive"))
    )
    (net (code "384") (name "unconnected-(A14B-D1-PadN1)") (class "Default")
      (node (ref "A14") (pin "N1") (pinfunction "D1_N1") (pintype "passive"))
    )
    (net (code "385") (name "unconnected-(A14B-E1-PadP1)") (class "Default")
      (node (ref "A14") (pin "P1") (pinfunction "E1_P1") (pintype "passive"))
    )
    (net (code "386") (name "unconnected-(A14B-F1-PadR1)") (class "Default")
      (node (ref "A14") (pin "R1") (pinfunction "F1_R1") (pintype "passive"))
    )
    (net (code "387") (name "unconnected-(A14B-J1-PadU1)") (class "Default")
      (node (ref "A14") (pin "U1") (pinfunction "J1_U1") (pintype "passive"))
    )
    (net (code "388") (name "unconnected-(A22-PadE2)") (class "Default")
      (node (ref "A22") (pin "E2") (pinfunction "E2_E2") (pintype "passive"))
    )
    (net (code "389") (name "unconnected-(AB01-PadBM1)") (class "Default")
      (node (ref "AB01") (pin "BM1") (pinfunction "BM1_BM1") (pintype "output"))
    )
    (net (code "390") (name "unconnected-(AB01-PadBR1)") (class "Default")
      (node (ref "AB01") (pin "BR1") (pinfunction "BR1_BR1") (pintype "output"))
    )
    (net (code "391") (name "unconnected-(B05F-E-PadP2)") (class "Default")
      (node (ref "B05") (pin "P2") (pinfunction "E_P2") (pintype "open_collector"))
    )
    (net (code "392") (name "unconnected-(B22H-D-PadU2)") (class "Default")
      (node (ref "B22") (pin "U2") (pinfunction "D_U2") (pintype "output"))
    )
    (net (code "393") (name "unconnected-(C02A-O13-PadR2)") (class "Default")
      (node (ref "C02") (pin "R2") (pinfunction "O13_R2") (pintype "output"))
    )
    (net (code "394") (name "unconnected-(C02A-O14-PadT2)") (class "Default")
      (node (ref "C02") (pin "T2") (pinfunction "O14_T2") (pintype "output"))
    )
    (net (code "395") (name "unconnected-(C03A-O13-PadR2)") (class "Default")
      (node (ref "C03") (pin "R2") (pinfunction "O13_R2") (pintype "output"))
    )
    (net (code "396") (name "unconnected-(C03A-O14-PadT2)") (class "Default")
      (node (ref "C03") (pin "T2") (pinfunction "O14_T2") (pintype "output"))
    )
    (net (code "397") (name "unconnected-(C03A-O15-PadV2)") (class "Default")
      (node (ref "C03") (pin "V2") (pinfunction "O15_V2") (pintype "output"))
    )
    (net (code "398") (name "unconnected-(C07-PadS1)") (class "Default")
      (node (ref "C07") (pin "S1") (pinfunction "S1_S1") (pintype "output"))
    )
    (net (code "399") (name "unconnected-(C07-PadU1)") (class "Default")
      (node (ref "C07") (pin "U1") (pinfunction "U1_U1") (pintype "output"))
    )
    (net (code "400") (name "unconnected-(C07-PadV1)") (class "Default")
      (node (ref "C07") (pin "V1") (pinfunction "V1_V1") (pintype "output"))
    )
    (net (code "401") (name "unconnected-(C07-PadV2)") (class "Default")
      (node (ref "C07") (pin "V2") (pinfunction "V2_V2") (pintype "output"))
    )
    (net (code "402") (name "unconnected-(CD18-PadAN2)") (class "Default")
      (node (ref "CD18") (pin "AN2") (pinfunction "AN2_AN2") (pintype "output"))
    )
    (net (code "403") (name "unconnected-(CD18-PadAU1)") (class "Default")
      (node (ref "CD18") (pin "AU1") (pinfunction "AU1_AU1") (pintype "output"))
    )
    (net (code "404") (name "unconnected-(D07A-O8-PadP2)") (class "Default")
      (node (ref "D07") (pin "P2") (pinfunction "O8_P2") (pintype "output"))
    )
    (net (code "405") (name "unconnected-(D07A-O9-PadR2)") (class "Default")
      (node (ref "D07") (pin "R2") (pinfunction "O9_R2") (pintype "output"))
    )
    (net (code "406") (name "unconnected-(D07A-~{O8}-PadP1)") (class "Default")
      (node (ref "D07") (pin "P1") (pinfunction "~{O8}_P1") (pintype "output"))
    )
    (net (code "407") (name "unconnected-(D07A-~{O9}-PadR1)") (class "Default")
      (node (ref "D07") (pin "R1") (pinfunction "~{O9}_R1") (pintype "output"))
    )
    (net (code "408") (name "unconnected-(D13-PadD2)") (class "Default")
      (node (ref "D13") (pin "D2") (pinfunction "D2_D2") (pintype "passive"))
    )
    (net (code "409") (name "unconnected-(D13-PadE2)") (class "Default")
      (node (ref "D13") (pin "E2") (pinfunction "E2_E2") (pintype "passive"))
    )
    (net (code "410") (name "unconnected-(D15-PadE2)") (class "Default")
      (node (ref "D15") (pin "E2") (pinfunction "E2_E2") (pintype "output"))
    )
    (net (code "411") (name "unconnected-(D16B-D1-PadN1)") (class "Default")
      (node (ref "D16") (pin "N1") (pinfunction "D1_N1") (pintype "passive"))
    )
    (net (code "412") (name "unconnected-(D16B-E1-PadP1)") (class "Default")
      (node (ref "D16") (pin "P1") (pinfunction "E1_P1") (pintype "passive"))
    )
    (net (code "413") (name "unconnected-(D16B-F1-PadR1)") (class "Default")
      (node (ref "D16") (pin "R1") (pinfunction "F1_R1") (pintype "passive"))
    )
    (net (code "414") (name "unconnected-(D16B-J1-PadU1)") (class "Default")
      (node (ref "D16") (pin "U1") (pinfunction "J1_U1") (pintype "passive"))
    )
    (net (code "415") (name "~{0_TO_AC}") (class "Default")
      (node (ref "B05") (pin "H1") (pinfunction "B_H1") (pintype "input"))
      (node (ref "B06") (pin "T2") (pinfunction "OUT_T2") (pintype "output"))
    )
    (net (code "416") (name "~{0_TO_DTB}") (class "Default")
      (node (ref "A11") (pin "L1") (pinfunction "IN_L1") (pintype "input"))
      (node (ref "B09") (pin "A1") (pinfunction "R_A1") (pintype "input"))
      (node (ref "B09") (pin "K2") (pinfunction "R_K2") (pintype "input"))
      (node (ref "B10") (pin "L1") (pinfunction "OUT_L1") (pintype "output"))
      (node (ref "C09") (pin "A1") (pinfunction "R_A1") (pintype "input"))
      (node (ref "C09") (pin "K2") (pinfunction "R_K2") (pintype "input"))
    )
    (net (code "417") (name "~{0_TO_EF}") (class "Default")
      (node (ref "A08") (pin "A1") (pinfunction "R_A1") (pintype "input"))
      (node (ref "A08") (pin "N2") (pinfunction "S_N2") (pintype "input"))
      (node (ref "A08") (pin "R1") (pinfunction "S_R1") (pintype "input"))
      (node (ref "A11") (pin "F2") (pinfunction "OUT_F2") (pintype "output"))
    )
    (net (code "418") (name "~{0_TO_LPB}") (class "Default")
      (node (ref "D08") (pin "A1") (pinfunction "A1_A1") (pintype "input"))
      (node (ref "D08") (pin "K2") (pinfunction "K2_K2") (pintype "input"))
      (node (ref "D12") (pin "J2") (pinfunction "OUT_J2") (pintype "output"))
    )
    (net (code "419") (name "~{0_TO_STATE}") (class "Default")
      (node (ref "C16") (pin "L1") (pinfunction "OUT_L1") (pintype "output"))
      (node (ref "CD18") (pin "AV2") (pinfunction "AV2_AV2") (pintype "input"))
    )
    (net (code "420") (name "~{0_TO_STA}") (class "Default")
      (node (ref "A11") (pin "P1") (pinfunction "OUT_P1") (pintype "output"))
      (node (ref "B07") (pin "A1") (pinfunction "A1_A1") (pintype "input"))
      (node (ref "B07") (pin "K2") (pinfunction "K2_K2") (pintype "input"))
      (node (ref "B11") (pin "P2") (pinfunction "IN2_P2") (pintype "input"))
      (node (ref "C07") (pin "A1") (pinfunction "A1_A1") (pintype "input"))
    )
    (net (code "421") (name "~{0_TO_W}") (class "Default")
      (node (ref "C16") (pin "E1") (pinfunction "OUT_E1") (pintype "output"))
      (node (ref "CD18") (pin "BH2") (pinfunction "BH2_BH2") (pintype "input"))
    )
    (net (code "422") (name "~{00}") (class "Default")
      (node (ref "A07") (pin "D1") (pinfunction "~{O0}_D1") (pintype "output"))
      (node (ref "B22") (pin "S2") (pinfunction "B_S2") (pintype "input"))
    )
    (net (code "423") (name "~{01}") (class "Default")
      (node (ref "A07") (pin "E1") (pinfunction "~{O1}_E1") (pintype "output"))
      (node (ref "A23") (pin "N1") (pinfunction "B_N1") (pintype "input"))
    )
    (net (code "424") (name "~{02}") (class "Default")
      (node (ref "A07") (pin "J1") (pinfunction "~{O2}_J1") (pintype "output"))
      (node (ref "A23") (pin "D2") (pinfunction "A_D2") (pintype "input"))
    )
    (net (code "425") (name "~{03}") (class "Default")
      (node (ref "A07") (pin "N1") (pinfunction "~{O3}_N1") (pintype "output"))
      (node (ref "A23") (pin "E2") (pinfunction "B_E2") (pintype "input"))
    )
    (net (code "426") (name "~{04}") (class "Default")
      (node (ref "A07") (pin "F1") (pinfunction "~{O4}_F1") (pintype "output"))
      (node (ref "A23") (pin "K2") (pinfunction "A_K2") (pintype "input"))
    )
    (net (code "427") (name "~{05}") (class "Default")
      (node (ref "A07") (pin "M1") (pinfunction "~{O5}_M1") (pintype "output"))
      (node (ref "A23") (pin "L2") (pinfunction "B_L2") (pintype "input"))
    )
    (net (code "428") (name "~{06}") (class "Default")
      (node (ref "A07") (pin "H1") (pinfunction "~{O6}_H1") (pintype "output"))
      (node (ref "A23") (pin "R2") (pinfunction "A_R2") (pintype "input"))
    )
    (net (code "429") (name "~{07}") (class "Default")
      (node (ref "A07") (pin "L1") (pinfunction "~{O7}_L1") (pintype "output"))
      (node (ref "A23") (pin "S2") (pinfunction "B_S2") (pintype "input"))
    )
    (net (code "430") (name "~{76}") (class "Default")
      (node (ref "C06") (pin "T2") (pinfunction "OUT_T2") (pintype "output"))
      (node (ref "D12") (pin "R2") (pinfunction "IN1_R2") (pintype "input"))
      (node (ref "D12") (pin "S2") (pinfunction "IN2_S2") (pintype "input"))
    )
    (net (code "431") (name "~{77}") (class "Default")
      (node (ref "C06") (pin "V2") (pinfunction "OUT_V2") (pintype "output"))
      (node (ref "D12") (pin "T2") (pinfunction "IN3_T2") (pintype "input"))
      (node (ref "D12") (pin "U2") (pinfunction "IN4_U2") (pintype "input"))
    )
    (net (code "432") (name "~{ADDR_ACC}") (class "Default")
      (node (ref "B08") (pin "T2") (pinfunction "IN1_T2") (pintype "input"))
      (node (ref "C17") (pin "P1") (pinfunction "OUT_P1") (pintype "output"))
    )
    (net (code "433") (name "~{B-BRK}") (class "Default")
      (node (ref "B02") (pin "C1") (pinfunction "C_C1") (pintype "input"))
      (node (ref "B02") (pin "F2") (pinfunction "C_F2") (pintype "input"))
      (node (ref "B02") (pin "J1") (pinfunction "C_J1") (pintype "input"))
      (node (ref "B02") (pin "M2") (pinfunction "C_M2") (pintype "input"))
      (node (ref "B02") (pin "P1") (pinfunction "C_P1") (pintype "input"))
      (node (ref "B02") (pin "T2") (pinfunction "C_T2") (pintype "input"))
      (node (ref "B10") (pin "V2") (pinfunction "OUT_V2") (pintype "output"))
    )
    (net (code "434") (name "~{BAC_00}") (class "Default")
      (node (ref "B06") (pin "A1") (pinfunction "IN_A1") (pintype "input"))
      (node (ref "C03") (pin "B1") (pinfunction "O1_B1") (pintype "output"))
      (node (ref "D10") (pin "F1") (pinfunction "IN1_F1") (pintype "input"))
    )
    (net (code "435") (name "~{BAC_01}") (class "Default")
      (node (ref "B06") (pin "D1") (pinfunction "IN_D1") (pintype "input"))
      (node (ref "C03") (pin "E1") (pinfunction "O2_E1") (pintype "output"))
      (node (ref "D10") (pin "H1") (pinfunction "IN2_H1") (pintype "input"))
    )
    (net (code "436") (name "~{BAC_02}") (class "Default")
      (node (ref "B06") (pin "F1") (pinfunction "IN_F1") (pintype "input"))
      (node (ref "C03") (pin "H1") (pinfunction "O3_H1") (pintype "output"))
      (node (ref "D10") (pin "J1") (pinfunction "IN3_J1") (pintype "input"))
    )
    (net (code "437") (name "~{BAC_03}") (class "Default")
      (node (ref "B06") (pin "J1") (pinfunction "IN_J1") (pintype "input"))
      (node (ref "C03") (pin "K1") (pinfunction "O4_K1") (pintype "output"))
      (node (ref "D10") (pin "K1") (pinfunction "IN4_K1") (pintype "input"))
    )
    (net (code "438") (name "~{BAC_04}") (class "Default")
      (node (ref "B06") (pin "L1") (pinfunction "IN_L1") (pintype "input"))
      (node (ref "C03") (pin "M1") (pinfunction "O5_M1") (pintype "output"))
      (node (ref "D10") (pin "K2") (pinfunction "IN5_K2") (pintype "input"))
    )
    (net (code "439") (name "~{BAC_05}") (class "Default")
      (node (ref "B06") (pin "N1") (pinfunction "IN_N1") (pintype "input"))
      (node (ref "C03") (pin "P1") (pinfunction "O6_P1") (pintype "output"))
    )
    (net (code "440") (name "~{BAC_06}") (class "Default")
      (node (ref "B06") (pin "R1") (pinfunction "IN_R1") (pintype "input"))
      (node (ref "C03") (pin "S1") (pinfunction "O7_S1") (pintype "output"))
    )
    (net (code "441") (name "~{BAC_07}") (class "Default")
      (node (ref "B06") (pin "V1") (pinfunction "IN_V1") (pintype "input"))
      (node (ref "C03") (pin "U1") (pinfunction "O8_U1") (pintype "output"))
    )
    (net (code "442") (name "~{BAC_08}") (class "Default")
      (node (ref "B06") (pin "C1") (pinfunction "IN_C1") (pintype "input"))
      (node (ref "C03") (pin "F2") (pinfunction "O9_F2") (pintype "output"))
    )
    (net (code "443") (name "~{BAC_09}") (class "Default")
      (node (ref "B06") (pin "E2") (pinfunction "IN_E2") (pintype "input"))
      (node (ref "C03") (pin "J2") (pinfunction "O10_J2") (pintype "output"))
    )
    (net (code "444") (name "~{BAC_10}") (class "Default")
      (node (ref "A10") (pin "D2") (pinfunction "IN1_D2") (pintype "input"))
      (node (ref "B06") (pin "H2") (pinfunction "IN_H2") (pintype "input"))
      (node (ref "C03") (pin "L2") (pinfunction "O11_L2") (pintype "output"))
    )
    (net (code "445") (name "~{BAC_11}") (class "Default")
      (node (ref "B06") (pin "K2") (pinfunction "IN_K2") (pintype "input"))
      (node (ref "C03") (pin "N2") (pinfunction "O12_N2") (pintype "output"))
      (node (ref "C11") (pin "R2") (pinfunction "IN2_R2") (pintype "input"))
    )
    (net (code "446") (name "~{BLK_IN_SYNC}") (class "Default")
      (node (ref "A10") (pin "A1") (pinfunction "IN1_A1") (pintype "input"))
      (node (ref "C13") (pin "R1") (pinfunction "IN_R1") (pintype "input"))
      (node (ref "D10") (pin "J2") (pinfunction "OUT_J2") (pintype "output"))
    )
    (net (code "447") (name "~{BMB_00}") (class "Default")
      (node (ref "C02") (pin "B1") (pinfunction "O1_B1") (pintype "output"))
      (node (ref "C06") (pin "A1") (pinfunction "IN_A1") (pintype "input"))
    )
    (net (code "448") (name "~{BMB_01}") (class "Default")
      (node (ref "C02") (pin "E1") (pinfunction "O2_E1") (pintype "output"))
      (node (ref "C06") (pin "D1") (pinfunction "IN_D1") (pintype "input"))
    )
    (net (code "449") (name "~{BMB_02}") (class "Default")
      (node (ref "C02") (pin "H1") (pinfunction "O3_H1") (pintype "output"))
      (node (ref "C06") (pin "F1") (pinfunction "IN_F1") (pintype "input"))
    )
    (net (code "450") (name "~{BMB_03}") (class "Default")
      (node (ref "C02") (pin "K1") (pinfunction "O4_K1") (pintype "output"))
      (node (ref "C06") (pin "J1") (pinfunction "IN_J1") (pintype "input"))
    )
    (net (code "451") (name "~{BMB_04}") (class "Default")
      (node (ref "C02") (pin "M1") (pinfunction "O5_M1") (pintype "output"))
      (node (ref "C06") (pin "L1") (pinfunction "IN_L1") (pintype "input"))
    )
    (net (code "452") (name "~{BMB_05}") (class "Default")
      (node (ref "C02") (pin "P1") (pinfunction "O6_P1") (pintype "output"))
      (node (ref "C06") (pin "N1") (pinfunction "IN_N1") (pintype "input"))
    )
    (net (code "453") (name "~{BMB_06}") (class "Default")
      (node (ref "C02") (pin "S1") (pinfunction "O7_S1") (pintype "output"))
      (node (ref "C06") (pin "R1") (pinfunction "IN_R1") (pintype "input"))
    )
    (net (code "454") (name "~{BMB_07}") (class "Default")
      (node (ref "C02") (pin "U1") (pinfunction "O8_U1") (pintype "output"))
      (node (ref "C06") (pin "V1") (pinfunction "IN_V1") (pintype "input"))
    )
    (net (code "455") (name "~{BMB_08}") (class "Default")
      (node (ref "C02") (pin "F2") (pinfunction "O9_F2") (pintype "output"))
      (node (ref "C06") (pin "C1") (pinfunction "IN_C1") (pintype "input"))
    )
    (net (code "456") (name "~{BMB_09}") (class "Default")
      (node (ref "C02") (pin "J2") (pinfunction "O10_J2") (pintype "output"))
      (node (ref "C06") (pin "E2") (pinfunction "IN_E2") (pintype "input"))
    )
    (net (code "457") (name "~{BMB_10}") (class "Default")
      (node (ref "C02") (pin "L2") (pinfunction "O11_L2") (pintype "output"))
      (node (ref "C06") (pin "H2") (pinfunction "IN_H2") (pintype "input"))
    )
    (net (code "458") (name "~{BMB_11}") (class "Default")
      (node (ref "C02") (pin "N2") (pinfunction "O12_N2") (pintype "output"))
      (node (ref "C06") (pin "K2") (pinfunction "IN_K2") (pintype "input"))
    )
    (net (code "459") (name "~{BMR00}") (class "Default")
      (node (ref "A23") (pin "H1") (pinfunction "B_H1") (pintype "input"))
      (node (ref "B14") (pin "R2") (pinfunction "0_R2") (pintype "output"))
    )
    (net (code "460") (name "~{BMR01}") (class "Default")
      (node (ref "A23") (pin "A1") (pinfunction "A_A1") (pintype "input"))
      (node (ref "B14") (pin "E1") (pinfunction "1_E1") (pintype "output"))
    )
    (net (code "461") (name "~{C00}") (class "Default")
      (node (ref "A12") (pin "P2") (pinfunction "IN1_P2") (pintype "input"))
      (node (ref "B13") (pin "P1") (pinfunction "D_P1") (pintype "input"))
      (node (ref "B13") (pin "S2") (pinfunction "C_S2") (pintype "input"))
      (node (ref "B13") (pin "U1") (pinfunction "0_U1") (pintype "output"))
      (node (ref "B15") (pin "H1") (pinfunction "IN1_H1") (pintype "input"))
      (node (ref "C15") (pin "J2") (pinfunction "IN2_J2") (pintype "input"))
    )
    (net (code "462") (name "~{C01}") (class "Default")
      (node (ref "A12") (pin "R2") (pinfunction "IN2_R2") (pintype "input"))
      (node (ref "B10") (pin "P1") (pinfunction "IN3_P1") (pintype "input"))
      (node (ref "B13") (pin "M2") (pinfunction "D_M2") (pintype "input"))
      (node (ref "B13") (pin "R2") (pinfunction "0_R2") (pintype "output"))
      (node (ref "C12") (pin "F2") (pinfunction "IN3_F2") (pintype "input"))
      (node (ref "D10") (pin "D1") (pinfunction "IN4_D1") (pintype "input"))
    )
    (net (code "463") (name "~{CK00}") (class "Default")
      (node (ref "A18") (pin "N2") (pinfunction "N2_N2") (pintype "input"))
      (node (ref "B14") (pin "T2") (pinfunction "D_T2") (pintype "input"))
      (node (ref "B14") (pin "U1") (pinfunction "0_U1") (pintype "output"))
    )
    (net (code "464") (name "~{CK01}") (class "Default")
      (node (ref "B14") (pin "V1") (pinfunction "0_V1") (pintype "output"))
      (node (ref "C16") (pin "S2") (pinfunction "IN2_S2") (pintype "input"))
      (node (ref "C16") (pin "T2") (pinfunction "IN3_T2") (pintype "input"))
      (node (ref "C16") (pin "U2") (pinfunction "IN4_U2") (pintype "input"))
    )
    (net (code "465") (name "~{CLR_DF}") (class "Default")
      (node (ref "A11") (pin "U1") (pinfunction "OUT_U1") (pintype "output"))
      (node (ref "D11") (pin "N2") (pinfunction "S_N2") (pintype "input"))
    )
    (net (code "466") (name "~{CLR_DTF}") (class "Default")
      (node (ref "C13") (pin "U1") (pinfunction "OUT_U1") (pintype "output"))
      (node (ref "D11") (pin "U2") (pinfunction "S_U2") (pintype "input"))
    )
    (net (code "467") (name "~{CSTA}") (class "Default")
      (node (ref "A10") (pin "L2") (pinfunction "IN1_L2") (pintype "input"))
      (node (ref "C04") (pin "C1") (pinfunction "C1_C1") (pintype "output"))
    )
    (net (code "468") (name "~{DATA}") (class "Default")
      (node (ref "B12") (pin "N1") (pinfunction "IN2_N1") (pintype "input"))
      (node (ref "C11") (pin "L2") (pinfunction "IN1_L2") (pintype "input"))
      (node (ref "C13") (pin "H1") (pinfunction "OUT_H1") (pintype "output"))
      (node (ref "C16") (pin "D2") (pinfunction "IN1_D2") (pintype "input"))
    )
    (net (code "469") (name "~{DB_00}") (class "Default")
      (node (ref "A06") (pin "B1") (pinfunction "P$2_B1") (pintype "bidirectional"))
      (node (ref "B02") (pin "D1") (pinfunction "D_D1") (pintype "open_collector"))
      (node (ref "D06") (pin "B1") (pinfunction "P$2_B1") (pintype "bidirectional"))
    )
    (net (code "470") (name "~{DB_01}") (class "Default")
      (node (ref "A06") (pin "D1") (pinfunction "P$2_D1") (pintype "bidirectional"))
      (node (ref "B02") (pin "E1") (pinfunction "E_E1") (pintype "open_collector"))
      (node (ref "D06") (pin "D1") (pinfunction "P$2_D1") (pintype "bidirectional"))
    )
    (net (code "471") (name "~{DB_02}") (class "Default")
      (node (ref "A06") (pin "E1") (pinfunction "P$2_E1") (pintype "bidirectional"))
      (node (ref "B02") (pin "K1") (pinfunction "D_K1") (pintype "open_collector"))
      (node (ref "D06") (pin "E1") (pinfunction "P$2_E1") (pintype "bidirectional"))
    )
    (net (code "472") (name "~{DB_03}") (class "Default")
      (node (ref "A06") (pin "H1") (pinfunction "P$2_H1") (pintype "bidirectional"))
      (node (ref "B02") (pin "L1") (pinfunction "E_L1") (pintype "open_collector"))
      (node (ref "D06") (pin "H1") (pinfunction "P$2_H1") (pintype "bidirectional"))
    )
    (net (code "473") (name "~{DB_04}") (class "Default")
      (node (ref "A06") (pin "J1") (pinfunction "P$2_J1") (pintype "bidirectional"))
      (node (ref "B02") (pin "R1") (pinfunction "D_R1") (pintype "open_collector"))
      (node (ref "D06") (pin "J1") (pinfunction "P$2_J1") (pintype "bidirectional"))
    )
    (net (code "474") (name "~{DB_05}") (class "Default")
      (node (ref "A06") (pin "L1") (pinfunction "P$2_L1") (pintype "bidirectional"))
      (node (ref "B02") (pin "S1") (pinfunction "E_S1") (pintype "open_collector"))
      (node (ref "D06") (pin "L1") (pinfunction "P$2_L1") (pintype "bidirectional"))
    )
    (net (code "475") (name "~{DB_06}") (class "Default")
      (node (ref "A06") (pin "M1") (pinfunction "P$2_M1") (pintype "bidirectional"))
      (node (ref "B02") (pin "H2") (pinfunction "D_H2") (pintype "open_collector"))
      (node (ref "D06") (pin "M1") (pinfunction "P$2_M1") (pintype "bidirectional"))
    )
    (net (code "476") (name "~{DB_07}") (class "Default")
      (node (ref "A06") (pin "P1") (pinfunction "P$2_P1") (pintype "bidirectional"))
      (node (ref "B02") (pin "J2") (pinfunction "E_J2") (pintype "open_collector"))
      (node (ref "D06") (pin "P1") (pinfunction "P$2_P1") (pintype "bidirectional"))
    )
    (net (code "477") (name "~{DB_08}") (class "Default")
      (node (ref "A06") (pin "S1") (pinfunction "P$2_S1") (pintype "bidirectional"))
      (node (ref "B02") (pin "N2") (pinfunction "D_N2") (pintype "open_collector"))
      (node (ref "D06") (pin "S1") (pinfunction "P$2_S1") (pintype "bidirectional"))
    )
    (net (code "478") (name "~{DB_09}") (class "Default")
      (node (ref "A06") (pin "D2") (pinfunction "P$2_D2") (pintype "bidirectional"))
      (node (ref "B02") (pin "P2") (pinfunction "E_P2") (pintype "open_collector"))
      (node (ref "D06") (pin "D2") (pinfunction "P$2_D2") (pintype "bidirectional"))
    )
    (net (code "479") (name "~{DB_10}") (class "Default")
      (node (ref "A06") (pin "E2") (pinfunction "P$2_E2") (pintype "bidirectional"))
      (node (ref "B02") (pin "U2") (pinfunction "D_U2") (pintype "open_collector"))
      (node (ref "D06") (pin "E2") (pinfunction "P$2_E2") (pintype "bidirectional"))
    )
    (net (code "480") (name "~{DB_11}") (class "Default")
      (node (ref "A06") (pin "H2") (pinfunction "P$2_H2") (pintype "bidirectional"))
      (node (ref "B02") (pin "V2") (pinfunction "E_V2") (pintype "open_collector"))
      (node (ref "D06") (pin "H2") (pinfunction "P$2_H2") (pintype "bidirectional"))
    )
    (net (code "481") (name "~{DF}") (class "Default")
      (node (ref "B05") (pin "A1") (pinfunction "A_A1") (pintype "input"))
      (node (ref "B12") (pin "J1") (pinfunction "IN3_J1") (pintype "input"))
      (node (ref "D11") (pin "P2") (pinfunction "1_P2") (pintype "output"))
    )
    (net (code "482") (name "~{DTB_00}") (class "Default")
      (node (ref "B02") (pin "A1") (pinfunction "A_A1") (pintype "input"))
      (node (ref "C09") (pin "F1") (pinfunction "0_F1") (pintype "output"))
    )
    (net (code "483") (name "~{DTB_01}") (class "Default")
      (node (ref "B02") (pin "B1") (pinfunction "B_B1") (pintype "input"))
      (node (ref "C09") (pin "J2") (pinfunction "0_J2") (pintype "output"))
    )
    (net (code "484") (name "~{DTB_02}") (class "Default")
      (node (ref "B02") (pin "F1") (pinfunction "A_F1") (pintype "input"))
      (node (ref "C09") (pin "M1") (pinfunction "0_M1") (pintype "output"))
    )
    (net (code "485") (name "~{DTB_03}") (class "Default")
      (node (ref "B02") (pin "H1") (pinfunction "B_H1") (pintype "input"))
      (node (ref "C09") (pin "R2") (pinfunction "0_R2") (pintype "output"))
    )
    (net (code "486") (name "~{DTB_04}") (class "Default")
      (node (ref "B02") (pin "M1") (pinfunction "A_M1") (pintype "input"))
      (node (ref "C09") (pin "U1") (pinfunction "0_U1") (pintype "output"))
    )
    (net (code "487") (name "~{DTB_05}") (class "Default")
      (node (ref "B02") (pin "N1") (pinfunction "B_N1") (pintype "input"))
      (node (ref "C09") (pin "V1") (pinfunction "0_V1") (pintype "output"))
    )
    (net (code "488") (name "~{DTB_06}") (class "Default")
      (node (ref "B02") (pin "D2") (pinfunction "A_D2") (pintype "input"))
      (node (ref "B09") (pin "F1") (pinfunction "0_F1") (pintype "output"))
    )
    (net (code "489") (name "~{DTB_07}") (class "Default")
      (node (ref "B02") (pin "E2") (pinfunction "B_E2") (pintype "input"))
      (node (ref "B09") (pin "V1") (pinfunction "0_V1") (pintype "output"))
    )
    (net (code "490") (name "~{DTB_08}") (class "Default")
      (node (ref "B02") (pin "K2") (pinfunction "A_K2") (pintype "input"))
      (node (ref "B09") (pin "M1") (pinfunction "0_M1") (pintype "output"))
    )
    (net (code "491") (name "~{DTB_09}") (class "Default")
      (node (ref "B02") (pin "L2") (pinfunction "B_L2") (pintype "input"))
      (node (ref "B09") (pin "R2") (pinfunction "0_R2") (pintype "output"))
    )
    (net (code "492") (name "~{DTB_10}") (class "Default")
      (node (ref "B02") (pin "R2") (pinfunction "A_R2") (pintype "input"))
      (node (ref "B09") (pin "U1") (pinfunction "0_U1") (pintype "output"))
    )
    (net (code "493") (name "~{DTB_11}") (class "Default")
      (node (ref "B02") (pin "S2") (pinfunction "B_S2") (pintype "input"))
      (node (ref "B09") (pin "J2") (pinfunction "0_J2") (pintype "output"))
    )
    (net (code "494") (name "~{DTF}") (class "Default")
      (node (ref "B04") (pin "L2") (pinfunction "B_L2") (pintype "input"))
      (node (ref "B12") (pin "C1") (pinfunction "IN3_C1") (pintype "input"))
      (node (ref "D11") (pin "V2") (pinfunction "1_V2") (pintype "output"))
    )
    (net (code "495") (name "~{DTSF}") (class "Default")
      (node (ref "C05") (pin "A1") (pinfunction "A1_A1") (pintype "output"))
    )
    (net (code "496") (name "~{EA_00}") (class "Default")
      (node (ref "A06") (pin "V2") (pinfunction "P$2_V2") (pintype "bidirectional"))
      (node (ref "B05") (pin "R1") (pinfunction "D_R1") (pintype "open_collector"))
      (node (ref "D06") (pin "V2") (pinfunction "P$2_V2") (pintype "bidirectional"))
    )
    (net (code "497") (name "~{EA_01}") (class "Default")
      (node (ref "A06") (pin "T2") (pinfunction "P$2_T2") (pintype "bidirectional"))
      (node (ref "B05") (pin "S1") (pinfunction "E_S1") (pintype "open_collector"))
      (node (ref "D06") (pin "T2") (pinfunction "P$2_T2") (pintype "bidirectional"))
    )
    (net (code "498") (name "~{EA_02}") (class "Default")
      (node (ref "A06") (pin "S2") (pinfunction "P$2_S2") (pintype "bidirectional"))
      (node (ref "B05") (pin "H2") (pinfunction "D_H2") (pintype "open_collector"))
      (node (ref "D06") (pin "S2") (pinfunction "P$2_S2") (pintype "bidirectional"))
    )
    (net (code "499") (name "~{EF}") (class "Default")
      (node (ref "A11") (pin "K1") (pinfunction "OUT_K1") (pintype "output"))
      (node (ref "B04") (pin "A1") (pinfunction "A_A1") (pintype "input"))
    )
    (net (code "500") (name "~{END}") (class "Default")
      (node (ref "A08") (pin "F1") (pinfunction "0_F1") (pintype "output"))
      (node (ref "A09") (pin "M2") (pinfunction "IN3_M2") (pintype "input"))
      (node (ref "B04") (pin "F1") (pinfunction "A_F1") (pintype "input"))
    )
    (net (code "501") (name "~{ENI}") (class "Default")
      (node (ref "B03") (pin "L2") (pinfunction "B_L2") (pintype "input"))
      (node (ref "C07") (pin "M1") (pinfunction "M1_M1") (pintype "output"))
    )
    (net (code "502") (name "~{FR_00}") (class "Default")
      (node (ref "B03") (pin "N1") (pinfunction "B_N1") (pintype "input"))
      (node (ref "B07") (pin "U1") (pinfunction "U1_U1") (pintype "output"))
      (node (ref "C12") (pin "K1") (pinfunction "IN1_K1") (pintype "input"))
      (node (ref "C12") (pin "P1") (pinfunction "IN1_P1") (pintype "input"))
    )
    (net (code "503") (name "~{FR_01}") (class "Default")
      (node (ref "A12") (pin "H2") (pinfunction "IN1_H2") (pintype "input"))
      (node (ref "B03") (pin "D2") (pinfunction "A_D2") (pintype "input"))
      (node (ref "B05") (pin "E2") (pinfunction "B_E2") (pintype "input"))
      (node (ref "B07") (pin "V1") (pinfunction "V1_V1") (pintype "output"))
    )
    (net (code "504") (name "~{FR_02}") (class "Default")
      (node (ref "B03") (pin "E2") (pinfunction "B_E2") (pintype "input"))
      (node (ref "C07") (pin "F1") (pinfunction "F1_F1") (pintype "output"))
    )
    (net (code "505") (name "~{FR_03}") (class "Default")
      (node (ref "B03") (pin "K2") (pinfunction "A_K2") (pintype "input"))
      (node (ref "B08") (pin "J2") (pinfunction "IN2_J2") (pintype "input"))
      (node (ref "C07") (pin "J2") (pinfunction "J2_J2") (pintype "output"))
    )
    (net (code "506") (name "~{IM_00}") (class "Default")
      (node (ref "A04") (pin "B1") (pinfunction "P$2_B1") (pintype "bidirectional"))
      (node (ref "B03") (pin "D1") (pinfunction "D_D1") (pintype "open_collector"))
      (node (ref "B04") (pin "D1") (pinfunction "D_D1") (pintype "open_collector"))
      (node (ref "D04") (pin "B1") (pinfunction "P$2_B1") (pintype "bidirectional"))
    )
    (net (code "507") (name "~{IM_01}") (class "Default")
      (node (ref "A04") (pin "D1") (pinfunction "P$2_D1") (pintype "bidirectional"))
      (node (ref "B03") (pin "E1") (pinfunction "E_E1") (pintype "open_collector"))
      (node (ref "B04") (pin "E1") (pinfunction "E_E1") (pintype "open_collector"))
      (node (ref "D04") (pin "D1") (pinfunction "P$2_D1") (pintype "bidirectional"))
    )
    (net (code "508") (name "~{IM_02}") (class "Default")
      (node (ref "A04") (pin "E1") (pinfunction "P$2_E1") (pintype "bidirectional"))
      (node (ref "B03") (pin "K1") (pinfunction "D_K1") (pintype "open_collector"))
      (node (ref "B04") (pin "K1") (pinfunction "D_K1") (pintype "open_collector"))
      (node (ref "D04") (pin "E1") (pinfunction "P$2_E1") (pintype "bidirectional"))
    )
    (net (code "509") (name "~{IM_03}") (class "Default")
      (node (ref "A04") (pin "H1") (pinfunction "P$2_H1") (pintype "bidirectional"))
      (node (ref "B03") (pin "L1") (pinfunction "E_L1") (pintype "open_collector"))
      (node (ref "B04") (pin "L1") (pinfunction "E_L1") (pintype "open_collector"))
      (node (ref "D04") (pin "H1") (pinfunction "P$2_H1") (pintype "bidirectional"))
    )
    (net (code "510") (name "~{IM_04}") (class "Default")
      (node (ref "A04") (pin "J1") (pinfunction "P$2_J1") (pintype "bidirectional"))
      (node (ref "B03") (pin "R1") (pinfunction "D_R1") (pintype "open_collector"))
      (node (ref "B04") (pin "R1") (pinfunction "D_R1") (pintype "open_collector"))
      (node (ref "D04") (pin "J1") (pinfunction "P$2_J1") (pintype "bidirectional"))
    )
    (net (code "511") (name "~{IM_05}") (class "Default")
      (node (ref "A04") (pin "L1") (pinfunction "P$2_L1") (pintype "bidirectional"))
      (node (ref "B03") (pin "S1") (pinfunction "E_S1") (pintype "open_collector"))
      (node (ref "B04") (pin "S1") (pinfunction "E_S1") (pintype "open_collector"))
      (node (ref "D04") (pin "L1") (pinfunction "P$2_L1") (pintype "bidirectional"))
    )
    (net (code "512") (name "~{IM_06}") (class "Default")
      (node (ref "A04") (pin "M1") (pinfunction "P$2_M1") (pintype "bidirectional"))
      (node (ref "B03") (pin "H2") (pinfunction "D_H2") (pintype "open_collector"))
      (node (ref "B04") (pin "H2") (pinfunction "D_H2") (pintype "open_collector"))
      (node (ref "D04") (pin "M1") (pinfunction "P$2_M1") (pintype "bidirectional"))
    )
    (net (code "513") (name "~{IM_07}") (class "Default")
      (node (ref "A04") (pin "P1") (pinfunction "P$2_P1") (pintype "bidirectional"))
      (node (ref "B03") (pin "J2") (pinfunction "E_J2") (pintype "open_collector"))
      (node (ref "B04") (pin "J2") (pinfunction "E_J2") (pintype "open_collector"))
      (node (ref "D04") (pin "P1") (pinfunction "P$2_P1") (pintype "bidirectional"))
    )
    (net (code "514") (name "~{IM_08}") (class "Default")
      (node (ref "A04") (pin "S1") (pinfunction "P$2_S1") (pintype "bidirectional"))
      (node (ref "B03") (pin "N2") (pinfunction "D_N2") (pintype "open_collector"))
      (node (ref "B04") (pin "N2") (pinfunction "D_N2") (pintype "open_collector"))
      (node (ref "D04") (pin "S1") (pinfunction "P$2_S1") (pintype "bidirectional"))
    )
    (net (code "515") (name "~{IM_09}") (class "Default")
      (node (ref "A04") (pin "D2") (pinfunction "P$2_D2") (pintype "bidirectional"))
      (node (ref "B03") (pin "P2") (pinfunction "E_P2") (pintype "open_collector"))
      (node (ref "D04") (pin "D2") (pinfunction "P$2_D2") (pintype "bidirectional"))
    )
    (net (code "516") (name "~{IM_10}") (class "Default")
      (node (ref "A04") (pin "E2") (pinfunction "P$2_E2") (pintype "bidirectional"))
      (node (ref "D04") (pin "E2") (pinfunction "P$2_E2") (pintype "bidirectional"))
    )
    (net (code "517") (name "~{IM_11}") (class "Default")
      (node (ref "A04") (pin "H2") (pinfunction "P$2_H2") (pintype "bidirectional"))
      (node (ref "B04") (pin "P2") (pinfunction "E_P2") (pintype "open_collector"))
      (node (ref "D04") (pin "H2") (pinfunction "P$2_H2") (pintype "bidirectional"))
    )
    (net (code "518") (name "~{INT_RQ}") (class "Default")
      (node (ref "A12") (pin "K1") (pinfunction "OUT_K1") (pintype "output"))
      (node (ref "B05") (pin "B1") (pinfunction "B_B1") (pintype "input"))
    )
    (net (code "519") (name "~{LDMF}") (class "Default")
      (node (ref "B08") (pin "P2") (pinfunction "IN1_P2") (pintype "input"))
      (node (ref "C05") (pin "E1") (pinfunction "E1_E1") (pintype "output"))
    )
    (net (code "520") (name "~{LPB_00}") (class "Default")
      (node (ref "D08") (pin "F1") (pinfunction "F1_F1") (pintype "output"))
      (node (ref "D10") (pin "M1") (pinfunction "IN1_M1") (pintype "input"))
    )
    (net (code "521") (name "~{LPB_01}") (class "Default")
      (node (ref "D08") (pin "M1") (pinfunction "M1_M1") (pintype "output"))
      (node (ref "D10") (pin "N1") (pinfunction "IN2_N1") (pintype "input"))
    )
    (net (code "522") (name "~{LPB_02}") (class "Default")
      (node (ref "D08") (pin "U1") (pinfunction "U1_U1") (pintype "output"))
      (node (ref "D10") (pin "P1") (pinfunction "IN3_P1") (pintype "input"))
    )
    (net (code "523") (name "~{LPB_03}") (class "Default")
      (node (ref "D08") (pin "J2") (pinfunction "J2_J2") (pintype "output"))
      (node (ref "D10") (pin "R1") (pinfunction "IN4_R1") (pintype "input"))
    )
    (net (code "524") (name "~{LPB_04}") (class "Default")
      (node (ref "D08") (pin "R2") (pinfunction "R2_R2") (pintype "output"))
      (node (ref "D10") (pin "R2") (pinfunction "IN5_R2") (pintype "input"))
    )
    (net (code "525") (name "~{LPB_05}") (class "Default")
      (node (ref "D08") (pin "V1") (pinfunction "V1_V1") (pintype "output"))
      (node (ref "D10") (pin "S2") (pinfunction "IN6_S2") (pintype "input"))
      (node (ref "D10") (pin "T2") (pinfunction "IN7_T2") (pintype "input"))
      (node (ref "D10") (pin "U2") (pinfunction "IN8_U2") (pintype "input"))
    )
    (net (code "526") (name "~{M-STOP}") (class "Default")
      (node (ref "A11") (pin "S1") (pinfunction "OUT_S1") (pintype "output"))
      (node (ref "B14") (pin "D1") (pinfunction "S_D1") (pintype "input"))
      (node (ref "C07") (pin "K2") (pinfunction "K2_K2") (pintype "input"))
      (node (ref "D14") (pin "L1") (pinfunction "M1_L1") (pintype "input"))
    )
    (net (code "527") (name "~{MB_TO_DTB}") (class "Default")
      (node (ref "D12") (pin "F1") (pinfunction "IN1_F1") (pintype "input"))
      (node (ref "D12") (pin "H1") (pinfunction "IN2_H1") (pintype "input"))
      (node (ref "D12") (pin "J1") (pinfunction "IN3_J1") (pintype "input"))
      (node (ref "D12") (pin "K1") (pinfunction "IN4_K1") (pintype "input"))
      (node (ref "D12") (pin "S1") (pinfunction "OUT_S1") (pintype "output"))
    )
    (net (code "528") (name "~{MC00}") (class "Default")
      (node (ref "A10") (pin "R1") (pinfunction "IN2_R1") (pintype "input"))
      (node (ref "B11") (pin "T2") (pinfunction "IN1_T2") (pintype "input"))
      (node (ref "B13") (pin "F1") (pinfunction "0_F1") (pintype "output"))
    )
    (net (code "529") (name "~{MC01}") (class "Default")
      (node (ref "B11") (pin "P1") (pinfunction "IN1_P1") (pintype "input"))
      (node (ref "B13") (pin "J2") (pinfunction "0_J2") (pintype "output"))
      (node (ref "C11") (pin "B1") (pinfunction "IN2_B1") (pintype "input"))
      (node (ref "D10") (pin "E2") (pinfunction "IN6_E2") (pintype "input"))
    )
    (net (code "530") (name "~{MC02}") (class "Default")
      (node (ref "B13") (pin "C1") (pinfunction "D_C1") (pintype "input"))
      (node (ref "B13") (pin "M1") (pinfunction "0_M1") (pintype "output"))
      (node (ref "D10") (pin "F2") (pinfunction "IN7_F2") (pintype "input"))
    )
    (net (code "531") (name "~{MF00}") (class "Default")
      (node (ref "B04") (pin "D2") (pinfunction "A_D2") (pintype "input"))
      (node (ref "B05") (pin "M1") (pinfunction "A_M1") (pintype "input"))
      (node (ref "D11") (pin "F1") (pinfunction "0_F1") (pintype "output"))
    )
    (net (code "532") (name "~{MF01}") (class "Default")
      (node (ref "B04") (pin "E2") (pinfunction "B_E2") (pintype "input"))
      (node (ref "B05") (pin "N1") (pinfunction "B_N1") (pintype "input"))
      (node (ref "D11") (pin "J2") (pinfunction "0_J2") (pintype "output"))
    )
    (net (code "533") (name "~{MF02}") (class "Default")
      (node (ref "B04") (pin "K2") (pinfunction "A_K2") (pintype "input"))
      (node (ref "B05") (pin "D2") (pinfunction "A_D2") (pintype "input"))
      (node (ref "D11") (pin "M1") (pinfunction "0_M1") (pintype "output"))
    )
    (net (code "534") (name "~{MKTK}") (class "Default")
      (node (ref "A08") (pin "P2") (pinfunction "1_P2") (pintype "output"))
      (node (ref "A09") (pin "K2") (pinfunction "IN1_K2") (pintype "input"))
      (node (ref "B04") (pin "B1") (pinfunction "B_B1") (pintype "input"))
    )
    (net (code "535") (name "~{MKT}") (class "Default")
      (node (ref "B10") (pin "R1") (pinfunction "IN4_R1") (pintype "input"))
      (node (ref "B13") (pin "T2") (pinfunction "D_T2") (pintype "input"))
      (node (ref "B13") (pin "V1") (pinfunction "0_V1") (pintype "output"))
      (node (ref "C14") (pin "N1") (pinfunction "C_N1") (pintype "input"))
      (node (ref "D10") (pin "H2") (pinfunction "IN8_H2") (pintype "input"))
    )
    (net (code "536") (name "~{MK_BLK_END}") (class "Default")
      (node (ref "A09") (pin "C1") (pinfunction "IN3_C1") (pintype "input"))
      (node (ref "CD18") (pin "BV1") (pinfunction "BV1_BV1") (pintype "output"))
    )
    (net (code "537") (name "~{MK_BLK_MK}") (class "Default")
      (node (ref "CD18") (pin "AD2") (pinfunction "AD2_AD2") (pintype "output"))
    )
    (net (code "538") (name "~{MK_BLK_START}") (class "Default")
      (node (ref "A09") (pin "A1") (pinfunction "IN1_A1") (pintype "input"))
      (node (ref "CD18") (pin "AF1") (pinfunction "AF1_AF1") (pintype "output"))
    )
    (net (code "539") (name "~{MK_BLK_SYNC}") (class "Default")
      (node (ref "CD18") (pin "BT2") (pinfunction "BT2_BT2") (pintype "output"))
    )
    (net (code "540") (name "~{MK_DATA_SYNC}") (class "Default")
      (node (ref "CD18") (pin "AJ1") (pinfunction "AJ1_AJ1") (pintype "output"))
    )
    (net (code "541") (name "~{MK_DATA}") (class "Default")
      (node (ref "A09") (pin "B1") (pinfunction "IN2_B1") (pintype "input"))
      (node (ref "CD18") (pin "AU2") (pinfunction "AU2_AU2") (pintype "output"))
    )
    (net (code "542") (name "~{MK_END}") (class "Default")
      (node (ref "A09") (pin "D1") (pinfunction "IN4_D1") (pintype "input"))
      (node (ref "CD18") (pin "AH2") (pinfunction "AH2_AH2") (pintype "output"))
    )
    (net (code "543") (name "~{MOVE}") (class "Default")
      (node (ref "A09") (pin "F2") (pinfunction "IN3_F2") (pintype "input"))
      (node (ref "D07") (pin "D1") (pinfunction "~{O0}_D1") (pintype "output"))
    )
    (net (code "544") (name "~{MR00}") (class "Default")
      (node (ref "B03") (pin "H1") (pinfunction "B_H1") (pintype "input"))
      (node (ref "B07") (pin "R2") (pinfunction "R2_R2") (pintype "output"))
    )
    (net (code "545") (name "~{MR01}") (class "Default")
      (node (ref "B03") (pin "M1") (pinfunction "A_M1") (pintype "input"))
      (node (ref "B14") (pin "C1") (pinfunction "D_C1") (pintype "input"))
      (node (ref "C07") (pin "R2") (pinfunction "R2_R2") (pintype "output"))
    )
    (net (code "546") (name "~{PAR}") (class "Default")
      (node (ref "A08") (pin "S1") (pinfunction "1_S1") (pintype "output"))
      (node (ref "A12") (pin "E1") (pinfunction "IN2_E1") (pintype "input"))
      (node (ref "B04") (pin "M1") (pinfunction "A_M1") (pintype "input"))
    )
    (net (code "547") (name "~{PC+ES}") (class "Default")
      (node (ref "A11") (pin "J2") (pinfunction "OUT_J2") (pintype "output"))
      (node (ref "B11") (pin "R2") (pinfunction "IN3_R2") (pintype "input"))
    )
    (net (code "548") (name "~{PWR_CLR}") (class "Default")
      (node (ref "A10") (pin "H2") (pinfunction "IN1_H2") (pintype "input"))
      (node (ref "A10") (pin "M2") (pinfunction "IN2_M2") (pintype "input"))
      (node (ref "A12") (pin "A1") (pinfunction "IN1_A1") (pintype "input"))
      (node (ref "A23") (pin "M1") (pinfunction "A_M1") (pintype "input"))
      (node (ref "B08") (pin "U2") (pinfunction "IN2_U2") (pintype "input"))
      (node (ref "C05") (pin "K1") (pinfunction "OUT_K1") (pintype "output"))
      (node (ref "C06") (pin "P2") (pinfunction "IN_P2") (pintype "input"))
      (node (ref "C11") (pin "U2") (pinfunction "IN2_U2") (pintype "input"))
      (node (ref "C14") (pin "R1") (pinfunction "S_R1") (pintype "input"))
      (node (ref "D11") (pin "A1") (pinfunction "R_A1") (pintype "input"))
    )
    (net (code "549") (name "~{RDD_00}") (class "Default")
      (node (ref "A21") (pin "V2") (pinfunction "V2_V2") (pintype "output"))
    )
    (net (code "550") (name "~{RDD_01}") (class "Default")
      (node (ref "B20") (pin "V2") (pinfunction "V2_V2") (pintype "output"))
    )
    (net (code "551") (name "~{RDD_02}") (class "Default")
      (node (ref "A20") (pin "V2") (pinfunction "V2_V2") (pintype "output"))
    )
    (net (code "552") (name "~{RDMK}") (class "Default")
      (node (ref "B18") (pin "V2") (pinfunction "V2_V2") (pintype "output"))
    )
    (net (code "553") (name "~{READ_ALL}") (class "Default")
      (node (ref "C11") (pin "M1") (pinfunction "IN2_M1") (pintype "input"))
      (node (ref "D07") (pin "N1") (pinfunction "~{O3}_N1") (pintype "output"))
    )
    (net (code "554") (name "~{READ_DATA}") (class "Default")
      (node (ref "B08") (pin "L2") (pinfunction "IN1_L2") (pintype "input"))
      (node (ref "B11") (pin "J2") (pinfunction "IN1_J2") (pintype "input"))
      (node (ref "D07") (pin "J1") (pinfunction "~{O2}_J1") (pintype "output"))
    )
    (net (code "555") (name "~{RSTA}") (class "Default")
      (node (ref "B03") (pin "C1") (pinfunction "C_C1") (pintype "input"))
      (node (ref "B03") (pin "F2") (pinfunction "C_F2") (pintype "input"))
      (node (ref "B03") (pin "J1") (pinfunction "C_J1") (pintype "input"))
      (node (ref "B03") (pin "M2") (pinfunction "C_M2") (pintype "input"))
      (node (ref "B03") (pin "P1") (pinfunction "C_P1") (pintype "input"))
      (node (ref "C04") (pin "A1") (pinfunction "A1_A1") (pintype "output"))
    )
    (net (code "556") (name "~{RSTB}") (class "Default")
      (node (ref "B04") (pin "C1") (pinfunction "C_C1") (pintype "input"))
      (node (ref "B04") (pin "F2") (pinfunction "C_F2") (pintype "input"))
      (node (ref "B04") (pin "J1") (pinfunction "C_J1") (pintype "input"))
      (node (ref "B04") (pin "M2") (pinfunction "C_M2") (pintype "input"))
      (node (ref "B04") (pin "P1") (pinfunction "C_P1") (pintype "input"))
      (node (ref "C05") (pin "C1") (pinfunction "C1_C1") (pintype "output"))
    )
    (net (code "557") (name "~{SEARCH}") (class "Default")
      (node (ref "B05") (pin "K2") (pinfunction "A_K2") (pintype "input"))
      (node (ref "B11") (pin "K2") (pinfunction "IN2_K2") (pintype "input"))
      (node (ref "D07") (pin "E1") (pinfunction "~{O1}_E1") (pintype "output"))
    )
    (net (code "558") (name "~{SEL}") (class "Default")
      (node (ref "A08") (pin "J2") (pinfunction "0_J2") (pintype "output"))
      (node (ref "A09") (pin "N2") (pinfunction "IN4_N2") (pintype "input"))
      (node (ref "B04") (pin "H1") (pinfunction "B_H1") (pintype "input"))
    )
    (net (code "559") (name "~{SE}") (class "Default")
      (node (ref "A09") (pin "H1") (pinfunction "IN2_H1") (pintype "input"))
      (node (ref "D07") (pin "L1") (pinfunction "~{O7}_L1") (pintype "output"))
    )
    (net (code "560") (name "~{SH_EN}") (class "Default")
      (node (ref "A11") (pin "M2") (pinfunction "IN_M2") (pintype "input"))
      (node (ref "A12") (pin "V2") (pinfunction "OUT_V2") (pintype "output"))
      (node (ref "C10") (pin "C1") (pinfunction "IN2A_C1") (pintype "input"))
      (node (ref "C10") (pin "J1") (pinfunction "IN2A_J1") (pintype "input"))
      (node (ref "C10") (pin "P1") (pinfunction "IN2A_P1") (pintype "input"))
    )
    (net (code "561") (name "~{SKP_RQ}") (class "Default")
      (node (ref "A12") (pin "S1") (pinfunction "OUT_S1") (pintype "output"))
      (node (ref "B05") (pin "F1") (pinfunction "A_F1") (pintype "input"))
    )
    (net (code "562") (name "~{SP_DY}") (class "Default")
      (node (ref "C14") (pin "M2") (pinfunction "D_M2") (pintype "input"))
      (node (ref "D14") (pin "F2") (pinfunction "F2_F2") (pintype "output"))
    )
    (net (code "563") (name "~{ST_BLK_MK}") (class "Default")
      (node (ref "A09") (pin "D2") (pinfunction "IN1_D2") (pintype "input"))
      (node (ref "A09") (pin "M1") (pinfunction "IN1_M1") (pintype "input"))
      (node (ref "C13") (pin "F2") (pinfunction "OUT_F2") (pintype "output"))
    )
    (net (code "564") (name "~{ST_CK_0P}") (class "Default")
      (node (ref "C13") (pin "A1") (pinfunction "IN_A1") (pintype "input"))
      (node (ref "D17") (pin "L2") (pinfunction "F2_L2") (pintype "output"))
    )
    (net (code "565") (name "~{ST_CK}") (class "Default")
      (node (ref "C13") (pin "K1") (pinfunction "OUT_K1") (pintype "output"))
      (node (ref "C16") (pin "E2") (pinfunction "IN2_E2") (pintype "input"))
    )
    (net (code "566") (name "~{ST_DATA}") (class "Default")
      (node (ref "C13") (pin "J2") (pinfunction "OUT_J2") (pintype "output"))
    )
    (net (code "567") (name "~{ST_FINAL}") (class "Default")
      (node (ref "C11") (pin "M2") (pinfunction "IN2_M2") (pintype "input"))
      (node (ref "C13") (pin "M1") (pinfunction "OUT_M1") (pintype "output"))
      (node (ref "C16") (pin "F2") (pinfunction "IN3_F2") (pintype "input"))
    )
    (net (code "568") (name "~{ST_IDLE}") (class "Default")
      (node (ref "A09") (pin "E2") (pinfunction "IN2_E2") (pintype "input"))
      (node (ref "A09") (pin "N1") (pinfunction "IN2_N1") (pintype "input"))
      (node (ref "C13") (pin "L2") (pinfunction "OUT_L2") (pintype "output"))
    )
    (net (code "569") (name "~{ST_REV_CK}") (class "Default")
      (node (ref "C13") (pin "E1") (pinfunction "OUT_E1") (pintype "output"))
    )
    (net (code "570") (name "~{SWTM}") (class "Default")
      (node (ref "B06") (pin "R2") (pinfunction "OUT_R2") (pintype "output"))
      (node (ref "C10") (pin "L2") (pinfunction "IN1B_L2") (pintype "input"))
    )
    (net (code "571") (name "~{SYNC-P}") (class "Default")
      (node (ref "B10") (pin "J2") (pinfunction "OUT_J2") (pintype "output"))
      (node (ref "B13") (pin "A1") (pinfunction "R_A1") (pintype "input"))
      (node (ref "B13") (pin "K2") (pinfunction "R_K2") (pintype "input"))
    )
    (net (code "572") (name "~{SYNC}") (class "Default")
      (node (ref "CD18") (pin "BM2") (pinfunction "BM2_BM2") (pintype "output"))
    )
    (net (code "573") (name "~{TIM}") (class "Default")
      (node (ref "A08") (pin "M1") (pinfunction "0_M1") (pintype "output"))
      (node (ref "A09") (pin "L2") (pinfunction "IN2_L2") (pintype "input"))
      (node (ref "B04") (pin "N1") (pinfunction "B_N1") (pintype "input"))
    )
    (net (code "574") (name "~{TM_EN}") (class "Default")
      (node (ref "B15") (pin "D1") (pinfunction "IN1_D1") (pintype "input"))
      (node (ref "B15") (pin "D2") (pinfunction "IN1_D2") (pintype "input"))
      (node (ref "C12") (pin "C1") (pinfunction "IN3_C1") (pintype "input"))
      (node (ref "C12") (pin "K2") (pinfunction "IN2_K2") (pintype "input"))
      (node (ref "C13") (pin "P1") (pinfunction "OUT_P1") (pintype "output"))
      (node (ref "D15") (pin "J2") (pinfunction "J2_J2") (pintype "input"))
      (node (ref "D15") (pin "K2") (pinfunction "K2_K2") (pintype "input"))
    )
    (net (code "575") (name "~{TP00_A}") (class "Default")
      (node (ref "A15") (pin "M1") (pinfunction "IN1_M1") (pintype "input"))
      (node (ref "A15") (pin "N1") (pinfunction "IN2_N1") (pintype "input"))
      (node (ref "A15") (pin "P1") (pinfunction "IN3_P1") (pintype "input"))
      (node (ref "A15") (pin "R1") (pinfunction "IN4_R1") (pintype "input"))
      (node (ref "A16") (pin "L2") (pinfunction "F2_L2") (pintype "output"))
    )
    (net (code "576") (name "~{TP0_XTLK_DY}") (class "Default")
      (node (ref "A11") (pin "R2") (pinfunction "OUT_R2") (pintype "output"))
      (node (ref "A15") (pin "F2") (pinfunction "IN3_F2") (pintype "input"))
      (node (ref "A16") (pin "J2") (pinfunction "J2_J2") (pintype "input"))
      (node (ref "A16") (pin "K2") (pinfunction "K2_K2") (pintype "input"))
    )
    (net (code "577") (name "~{TP00}") (class "Default")
      (node (ref "A15") (pin "E1") (pinfunction "OUT_E1") (pintype "output"))
      (node (ref "A15") (pin "F1") (pinfunction "IN1_F1") (pintype "input"))
      (node (ref "A15") (pin "H1") (pinfunction "IN2_H1") (pintype "input"))
      (node (ref "A15") (pin "J1") (pinfunction "IN3_J1") (pintype "input"))
      (node (ref "A15") (pin "K1") (pinfunction "IN4_K1") (pintype "input"))
      (node (ref "B13") (pin "N1") (pinfunction "C_N1") (pintype "input"))
      (node (ref "CD18") (pin "AN1") (pinfunction "AN1_AN1") (pintype "input"))
    )
    (net (code "578") (name "~{TP01_A}") (class "Default")
      (node (ref "A15") (pin "R2") (pinfunction "IN1_R2") (pintype "input"))
      (node (ref "A15") (pin "S2") (pinfunction "IN2_S2") (pintype "input"))
      (node (ref "A15") (pin "T2") (pinfunction "IN3_T2") (pintype "input"))
      (node (ref "A15") (pin "U2") (pinfunction "IN4_U2") (pintype "input"))
      (node (ref "B16") (pin "L2") (pinfunction "F2_L2") (pintype "output"))
    )
    (net (code "579") (name "~{TP1_XTLK_DY}") (class "Default")
      (node (ref "A11") (pin "V2") (pinfunction "OUT_V2") (pintype "output"))
      (node (ref "A15") (pin "B1") (pinfunction "IN2_B1") (pintype "input"))
      (node (ref "B16") (pin "H2") (pinfunction "H2_H2") (pintype "input"))
      (node (ref "B16") (pin "J2") (pinfunction "J2_J2") (pintype "input"))
    )
    (net (code "580") (name "~{TP01}") (class "Default")
      (node (ref "A15") (pin "J2") (pinfunction "OUT_J2") (pintype "output"))
      (node (ref "A15") (pin "K2") (pinfunction "IN1_K2") (pintype "input"))
      (node (ref "A15") (pin "L2") (pinfunction "IN2_L2") (pintype "input"))
      (node (ref "A15") (pin "M2") (pinfunction "IN3_M2") (pintype "input"))
      (node (ref "A15") (pin "N2") (pinfunction "IN4_N2") (pintype "input"))
      (node (ref "B13") (pin "L2") (pinfunction "C_L2") (pintype "input"))
    )
    (net (code "581") (name "~{TS03}") (class "Default")
      (node (ref "C04") (pin "K1") (pinfunction "OUT_K1") (pintype "output"))
      (node (ref "D17") (pin "H2") (pinfunction "H2_H2") (pintype "input"))
      (node (ref "D17") (pin "J2") (pinfunction "J2_J2") (pintype "input"))
      (node (ref "D17") (pin "K2") (pinfunction "K2_K2") (pintype "input"))
    )
    (net (code "582") (name "~{T_00}") (class "Default")
      (node (ref "A24") (pin "V2") (pinfunction "P$2_V2") (pintype "bidirectional"))
      (node (ref "B22") (pin "V2") (pinfunction "E_V2") (pintype "output"))
      (node (ref "B23") (pin "V2") (pinfunction "P$1_V2") (pintype "passive"))
    )
    (net (code "583") (name "~{T_01}") (class "Default")
      (node (ref "A23") (pin "S1") (pinfunction "E_S1") (pintype "output"))
      (node (ref "A24") (pin "M2") (pinfunction "P$2_M2") (pintype "bidirectional"))
      (node (ref "B23") (pin "M2") (pinfunction "P$1_M2") (pintype "passive"))
    )
    (net (code "584") (name "~{T_02}") (class "Default")
      (node (ref "A23") (pin "H2") (pinfunction "D_H2") (pintype "output"))
      (node (ref "A24") (pin "N2") (pinfunction "P$2_N2") (pintype "bidirectional"))
      (node (ref "B23") (pin "N2") (pinfunction "P$1_N2") (pintype "passive"))
    )
    (net (code "585") (name "~{T_03}") (class "Default")
      (node (ref "A23") (pin "J2") (pinfunction "E_J2") (pintype "output"))
      (node (ref "A24") (pin "P2") (pinfunction "P$2_P2") (pintype "bidirectional"))
      (node (ref "B23") (pin "P2") (pinfunction "P$1_P2") (pintype "passive"))
    )
    (net (code "586") (name "~{T_04}") (class "Default")
      (node (ref "A23") (pin "N2") (pinfunction "D_N2") (pintype "output"))
      (node (ref "A24") (pin "R2") (pinfunction "P$2_R2") (pintype "bidirectional"))
      (node (ref "B23") (pin "R2") (pinfunction "P$1_R2") (pintype "passive"))
    )
    (net (code "587") (name "~{T_05}") (class "Default")
      (node (ref "A23") (pin "P2") (pinfunction "E_P2") (pintype "output"))
      (node (ref "A24") (pin "S2") (pinfunction "P$2_S2") (pintype "bidirectional"))
      (node (ref "B23") (pin "S2") (pinfunction "P$1_S2") (pintype "passive"))
    )
    (net (code "588") (name "~{T_06}") (class "Default")
      (node (ref "A23") (pin "U2") (pinfunction "D_U2") (pintype "output"))
      (node (ref "A24") (pin "T2") (pinfunction "P$2_T2") (pintype "bidirectional"))
      (node (ref "B23") (pin "T2") (pinfunction "P$1_T2") (pintype "passive"))
    )
    (net (code "589") (name "~{T_07}") (class "Default")
      (node (ref "A23") (pin "V2") (pinfunction "E_V2") (pintype "output"))
      (node (ref "A24") (pin "U2") (pinfunction "P$2_U2") (pintype "bidirectional"))
      (node (ref "B23") (pin "U2") (pinfunction "P$1_U2") (pintype "passive"))
    )
    (net (code "590") (name "~{T_FWD}") (class "Default")
      (node (ref "A23") (pin "K1") (pinfunction "D_K1") (pintype "output"))
      (node (ref "A24") (pin "E2") (pinfunction "P$2_E2") (pintype "bidirectional"))
      (node (ref "B23") (pin "H2") (pinfunction "P$1_H2") (pintype "passive"))
    )
    (net (code "591") (name "~{T_GO}") (class "Default")
      (node (ref "A23") (pin "D1") (pinfunction "D_D1") (pintype "output"))
      (node (ref "A24") (pin "C2") (pinfunction "P$2_C2") (pintype "bidirectional"))
      (node (ref "B23") (pin "D2") (pinfunction "P$1_D2") (pintype "passive"))
    )
    (net (code "592") (name "~{T_PWR_CLR}") (class "Default")
      (node (ref "A23") (pin "R1") (pinfunction "D_R1") (pintype "output"))
      (node (ref "A24") (pin "H2") (pinfunction "P$2_H2") (pintype "bidirectional"))
      (node (ref "B23") (pin "K2") (pinfunction "P$1_K2") (pintype "passive"))
    )
    (net (code "593") (name "~{T_REV}") (class "Default")
      (node (ref "A23") (pin "L1") (pinfunction "E_L1") (pintype "output"))
      (node (ref "A24") (pin "F2") (pinfunction "P$2_F2") (pintype "bidirectional"))
      (node (ref "B23") (pin "J2") (pinfunction "P$1_J2") (pintype "passive"))
    )
    (net (code "594") (name "~{T_SINGLE_UNIT}") (class "Default")
      (node (ref "A24") (pin "K2") (pinfunction "P$2_K2") (pintype "bidirectional"))
      (node (ref "B21") (pin "T2") (pinfunction "IN_T2") (pintype "input"))
    )
    (net (code "595") (name "~{T_STOP}") (class "Default")
      (node (ref "A23") (pin "E1") (pinfunction "E_E1") (pintype "output"))
      (node (ref "A24") (pin "D2") (pinfunction "P$2_D2") (pintype "bidirectional"))
      (node (ref "B23") (pin "E2") (pinfunction "P$1_E2") (pintype "passive"))
    )
    (net (code "596") (name "~{T_TRK}") (class "Default")
      (node (ref "A18") (pin "V2") (pinfunction "V2_V2") (pintype "output"))
      (node (ref "B15") (pin "E1") (pinfunction "IN2_E1") (pintype "input"))
    )
    (net (code "597") (name "~{T_WRITE_OK}") (class "Default")
      (node (ref "A22") (pin "H2") (pinfunction "H2_H2") (pintype "input"))
      (node (ref "A24") (pin "L2") (pinfunction "P$2_L2") (pintype "bidirectional"))
      (node (ref "B23") (pin "L2") (pinfunction "P$1_L2") (pintype "passive"))
    )
    (net (code "598") (name "~{U+M_DY}") (class "Default")
      (node (ref "C12") (pin "A1") (pinfunction "IN1_A1") (pintype "input"))
      (node (ref "C12") (pin "R2") (pinfunction "IN3_R2") (pintype "input"))
      (node (ref "D14") (pin "E2") (pinfunction "F2_E2") (pintype "output"))
      (node (ref "D14") (pin "N1") (pinfunction "N1_N1") (pintype "input"))
    )
    (net (code "599") (name "~{USR_00}") (class "Default")
      (node (ref "B03") (pin "A1") (pinfunction "A_A1") (pintype "input"))
      (node (ref "B07") (pin "F1") (pinfunction "F1_F1") (pintype "output"))
    )
    (net (code "600") (name "~{USR_01}") (class "Default")
      (node (ref "B03") (pin "B1") (pinfunction "B_B1") (pintype "input"))
      (node (ref "B07") (pin "J2") (pinfunction "J2_J2") (pintype "output"))
    )
    (net (code "601") (name "~{USR_02}") (class "Default")
      (node (ref "B03") (pin "F1") (pinfunction "A_F1") (pintype "input"))
      (node (ref "B07") (pin "M1") (pinfunction "M1_M1") (pintype "output"))
    )
    (net (code "602") (name "~{UTS}") (class "Default")
      (node (ref "C12") (pin "L2") (pinfunction "IN3_L2") (pintype "input"))
      (node (ref "C14") (pin "P2") (pinfunction "1_P2") (pintype "output"))
      (node (ref "C15") (pin "P2") (pinfunction "IN1_P2") (pintype "input"))
      (node (ref "C16") (pin "A1") (pinfunction "IN1_A1") (pintype "input"))
      (node (ref "C16") (pin "B1") (pinfunction "IN2_B1") (pintype "input"))
      (node (ref "C16") (pin "C1") (pinfunction "IN3_C1") (pintype "input"))
      (node (ref "C16") (pin "D1") (pinfunction "IN4_D1") (pintype "input"))
      (node (ref "C16") (pin "F1") (pinfunction "IN1_F1") (pintype "input"))
      (node (ref "C16") (pin "H1") (pinfunction "IN2_H1") (pintype "input"))
      (node (ref "C16") (pin "J1") (pinfunction "IN3_J1") (pintype "input"))
      (node (ref "C16") (pin "K1") (pinfunction "IN4_K1") (pintype "input"))
    )
    (net (code "603") (name "~{W-INH}") (class "Default")
      (node (ref "A08") (pin "V2") (pinfunction "1_V2") (pintype "output"))
      (node (ref "B11") (pin "L1") (pinfunction "IN2_L1") (pintype "input"))
      (node (ref "B12") (pin "H1") (pinfunction "IN2_H1") (pintype "input"))
    )
    (net (code "604") (name "~{WB00}") (class "Default")
      (node (ref "A21") (pin "P2") (pinfunction "P2_P2") (pintype "input"))
      (node (ref "B18") (pin "P2") (pinfunction "P2_P2") (pintype "input"))
      (node (ref "C10") (pin "D1") (pinfunction "IN2B_D1") (pintype "input"))
      (node (ref "C14") (pin "E1") (pinfunction "1_E1") (pintype "output"))
    )
    (net (code "605") (name "~{WB01}") (class "Default")
      (node (ref "B20") (pin "P2") (pinfunction "P2_P2") (pintype "input"))
      (node (ref "C10") (pin "K1") (pinfunction "IN2B_K1") (pintype "input"))
      (node (ref "C14") (pin "H2") (pinfunction "1_H2") (pintype "output"))
    )
    (net (code "606") (name "~{WB02}") (class "Default")
      (node (ref "A20") (pin "P2") (pinfunction "P2_P2") (pintype "input"))
      (node (ref "C10") (pin "R1") (pinfunction "IN2B_R1") (pintype "input"))
      (node (ref "C14") (pin "L1") (pinfunction "1_L1") (pintype "output"))
    )
    (net (code "607") (name "~{WC0}") (class "Default")
      (node (ref "C06") (pin "N2") (pinfunction "OUT_N2") (pintype "output"))
      (node (ref "D11") (pin "R1") (pinfunction "S_R1") (pintype "input"))
    )
    (net (code "608") (name "~{WC}") (class "Default")
      (node (ref "B12") (pin "F2") (pinfunction "IN3_F2") (pintype "input"))
      (node (ref "C12") (pin "T2") (pinfunction "IN1_T2") (pintype "input"))
      (node (ref "D11") (pin "M2") (pinfunction "D_M2") (pintype "input"))
      (node (ref "D11") (pin "U1") (pinfunction "0_U1") (pintype "output"))
    )
    (net (code "609") (name "~{WRITE_ALL}") (class "Default")
      (node (ref "D07") (pin "M1") (pinfunction "~{O5}_M1") (pintype "output"))
    )
    (net (code "610") (name "~{WRITE_DATA}") (class "Default")
      (node (ref "B08") (pin "M2") (pinfunction "IN2_M2") (pintype "input"))
      (node (ref "D07") (pin "F1") (pinfunction "~{O4}_F1") (pintype "output"))
    )
    (net (code "611") (name "~{WRITE_OK}") (class "Default")
      (node (ref "A10") (pin "J1") (pinfunction "IN2_J1") (pintype "input"))
      (node (ref "C17") (pin "J2") (pinfunction "OUT_J2") (pintype "output"))
    )
    (net (code "612") (name "~{WRTM}") (class "Default")
      (node (ref "B08") (pin "H2") (pinfunction "IN1_H2") (pintype "input"))
      (node (ref "C10") (pin "M2") (pinfunction "IN2A_M2") (pintype "input"))
      (node (ref "D07") (pin "H1") (pinfunction "~{O6}_H1") (pintype "output"))
    )
    (net (code "613") (name "~{WR_EN}") (class "Default")
      (node (ref "B11") (pin "F1") (pinfunction "IN2_F1") (pintype "input"))
      (node (ref "C11") (pin "H2") (pinfunction "IN1_H2") (pintype "input"))
      (node (ref "C12") (pin "J2") (pinfunction "IN1_J2") (pintype "input"))
      (node (ref "C14") (pin "S1") (pinfunction "1_S1") (pintype "output"))
      (node (ref "C15") (pin "D2") (pinfunction "IN1_D2") (pintype "input"))
      (node (ref "C15") (pin "H2") (pinfunction "IN1_H2") (pintype "input"))
    )
    (net (code "614") (name "~{XSAD}") (class "Default")
      (node (ref "A11") (pin "K2") (pinfunction "IN_K2") (pintype "input"))
      (node (ref "D13") (pin "L2") (pinfunction "F2_L2") (pintype "output"))
    )
    (net (code "615") (name "~{XSTA}") (class "Default")
      (node (ref "B08") (pin "R2") (pinfunction "IN2_R2") (pintype "input"))
      (node (ref "C04") (pin "E1") (pinfunction "E1_E1") (pintype "output"))
      (node (ref "D13") (pin "H2") (pinfunction "H2_H2") (pintype "input"))
      (node (ref "D13") (pin "J2") (pinfunction "J2_J2") (pintype "input"))
      (node (ref "D13") (pin "K2") (pinfunction "K2_K2") (pintype "input"))
      (node (ref "D14") (pin "K2") (pinfunction "U1_K2") (pintype "input"))
      (node (ref "D14") (pin "L2") (pinfunction "S1_L2") (pintype "input"))
      (node (ref "D16") (pin "M2") (pinfunction "H2_M2") (pintype "input"))
      (node (ref "D16") (pin "N2") (pinfunction "J2_N2") (pintype "input"))
    )
  )
)
